# ENERGIS_Main-Board-1_1_0.net
KiCad netlist of a schematic drawn in EAGLE
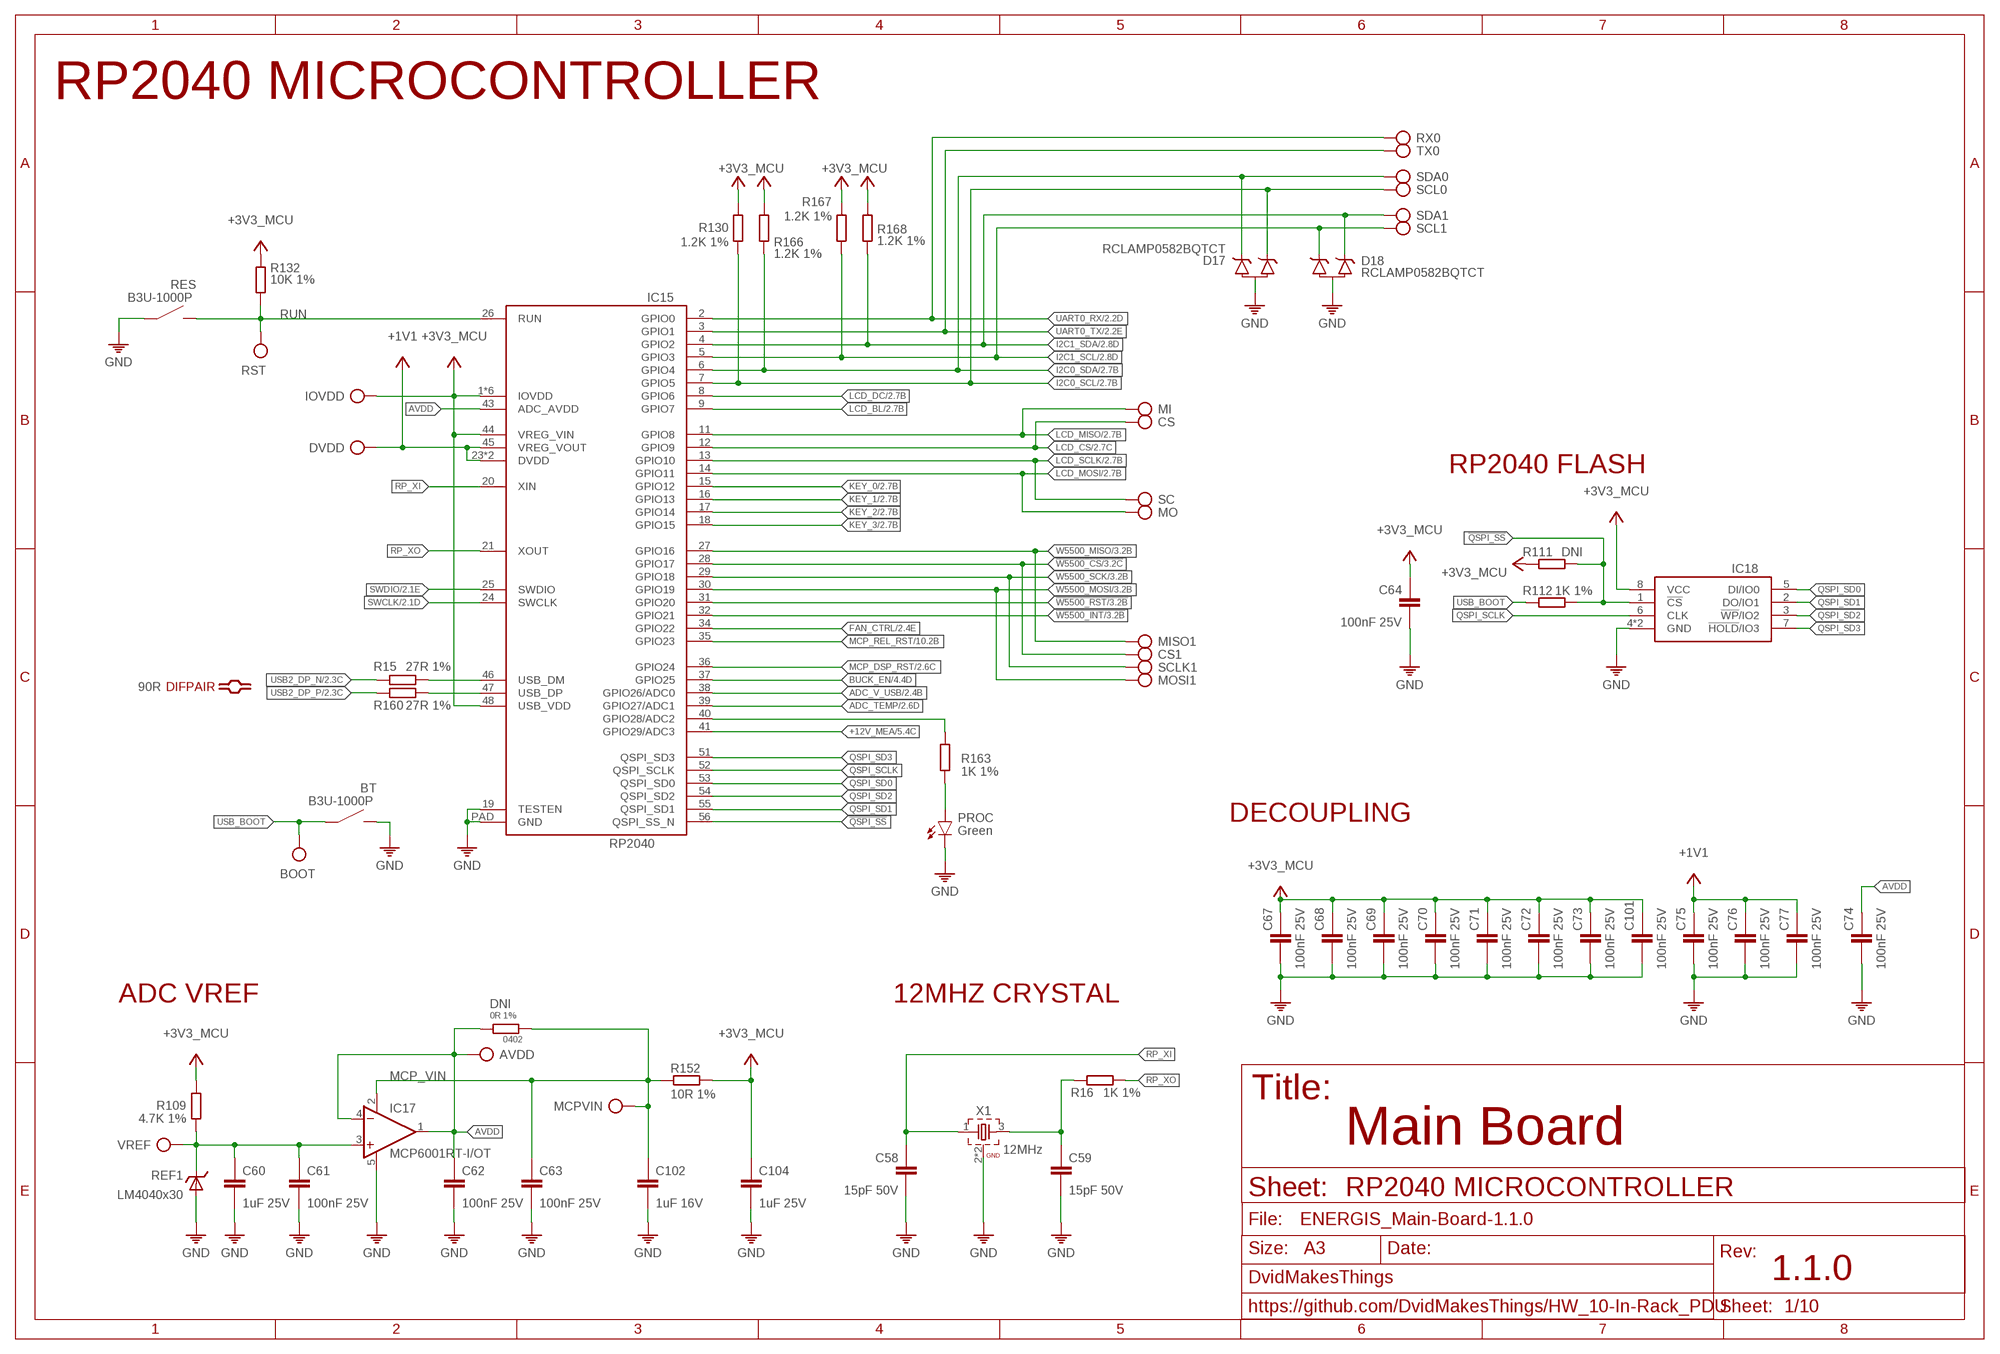
[diagram p0: schematic, sheet 1]
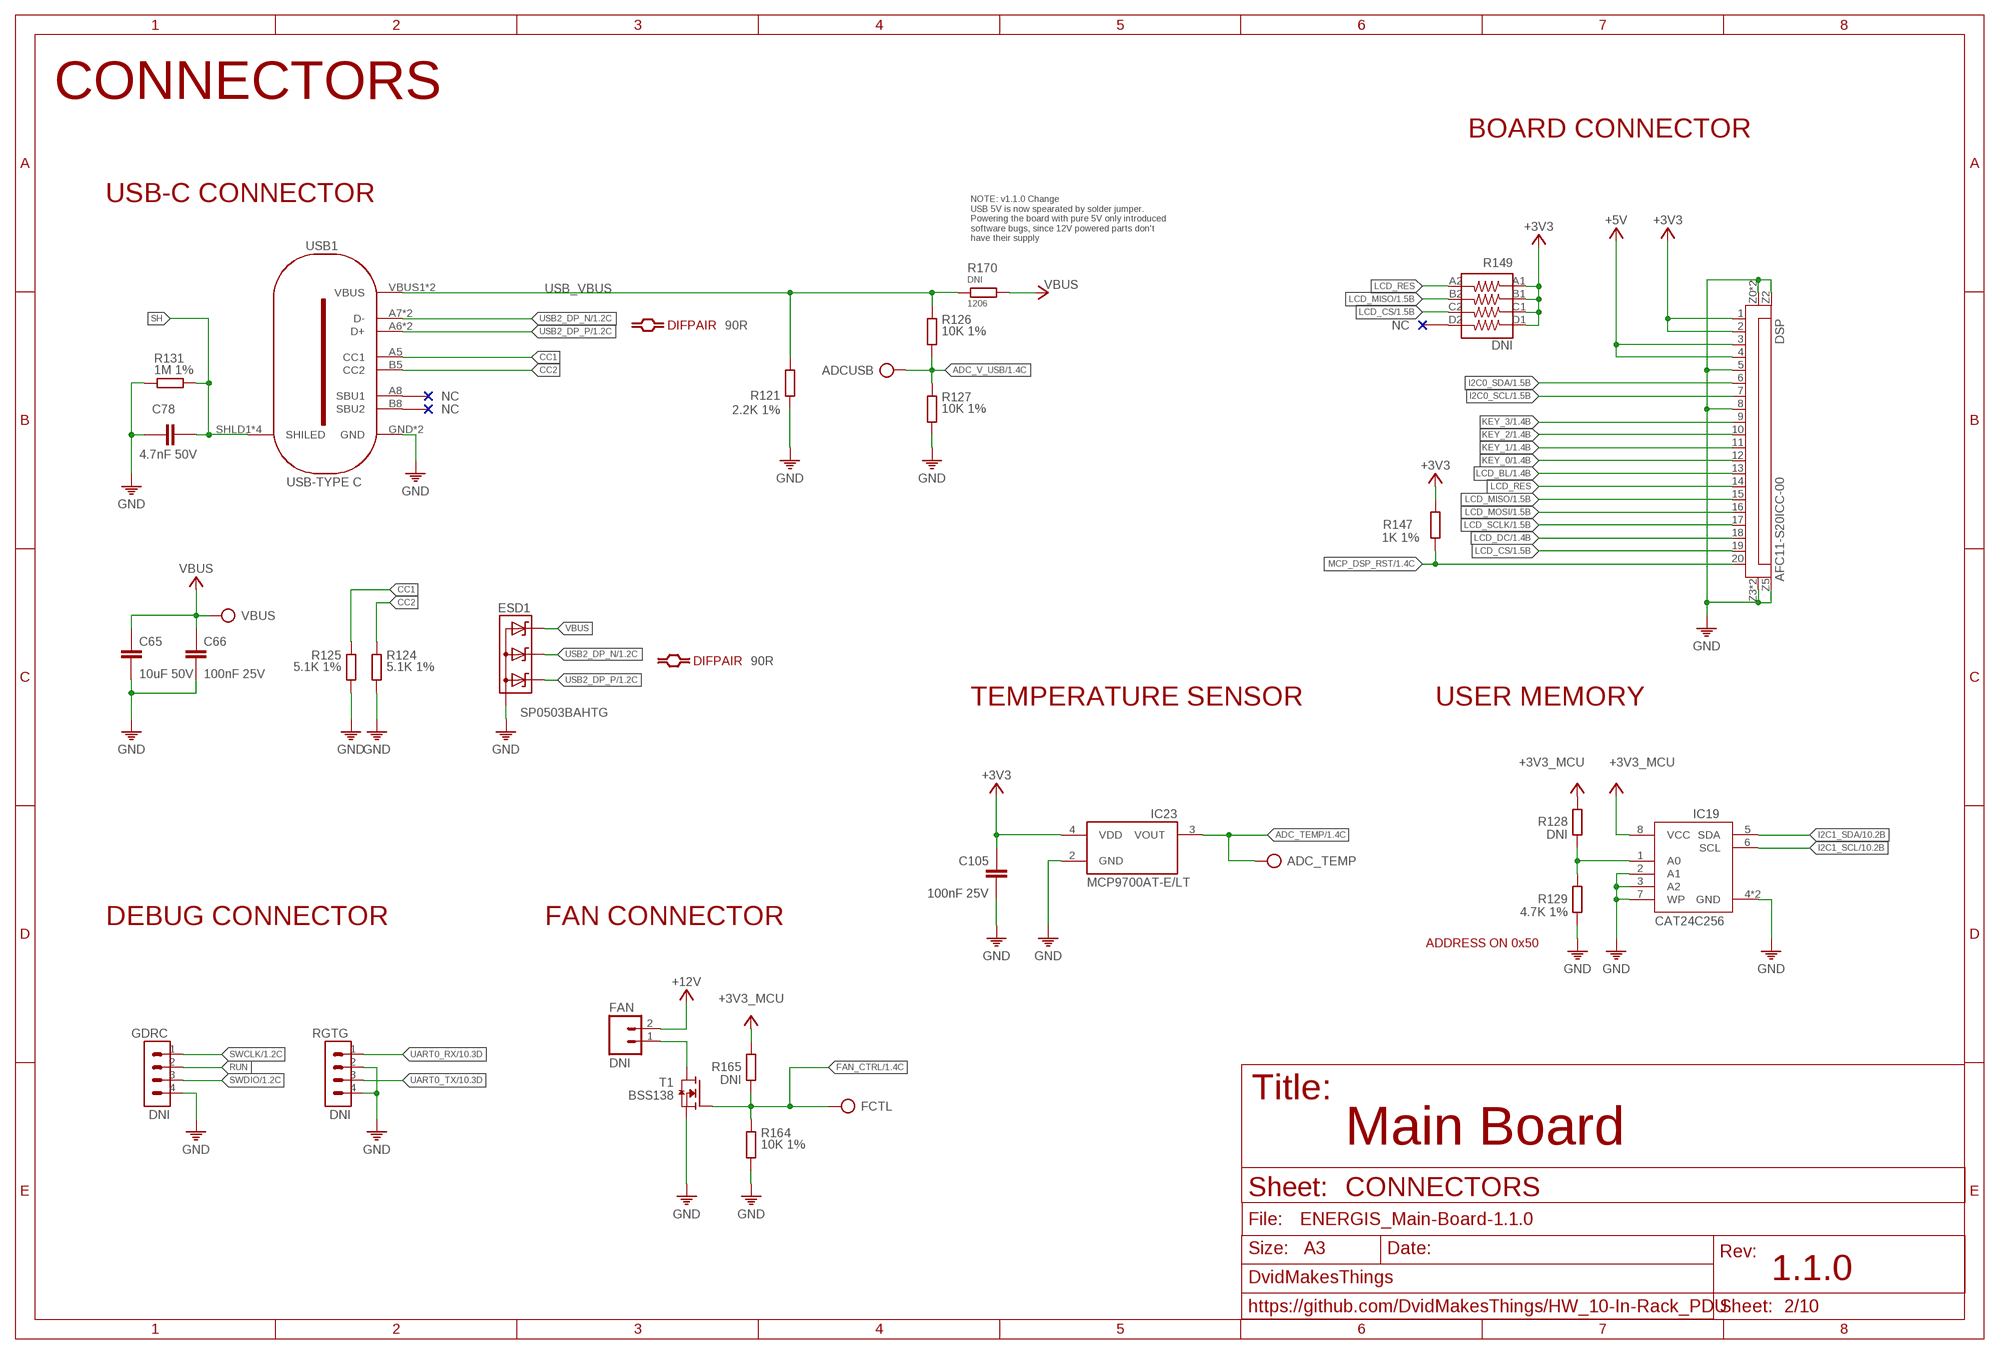
[diagram p1: schematic, sheet 2]
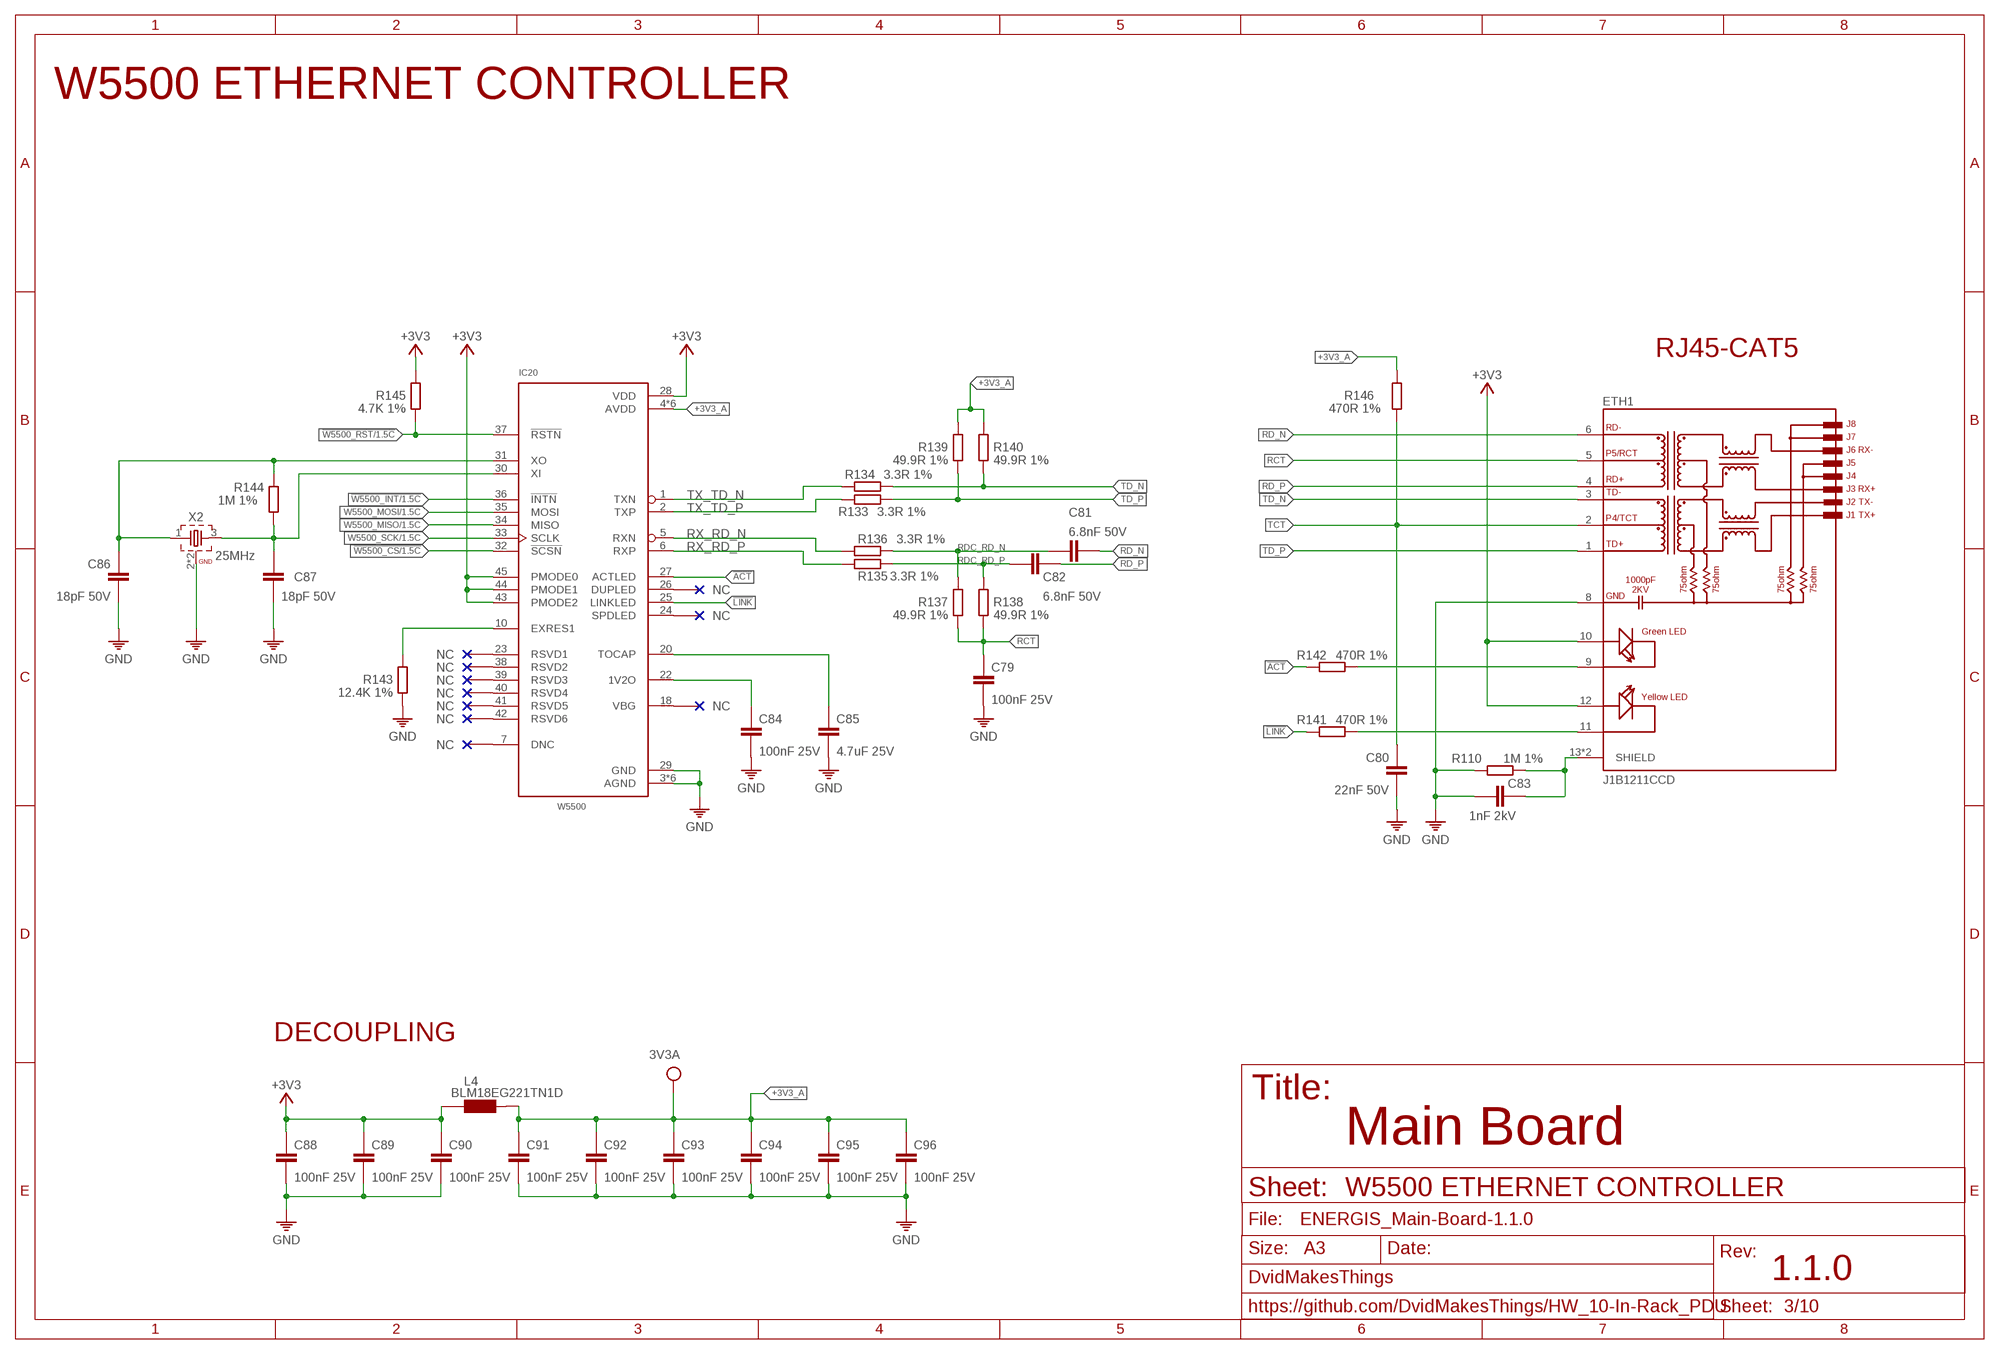
[diagram p2: schematic, sheet 3]
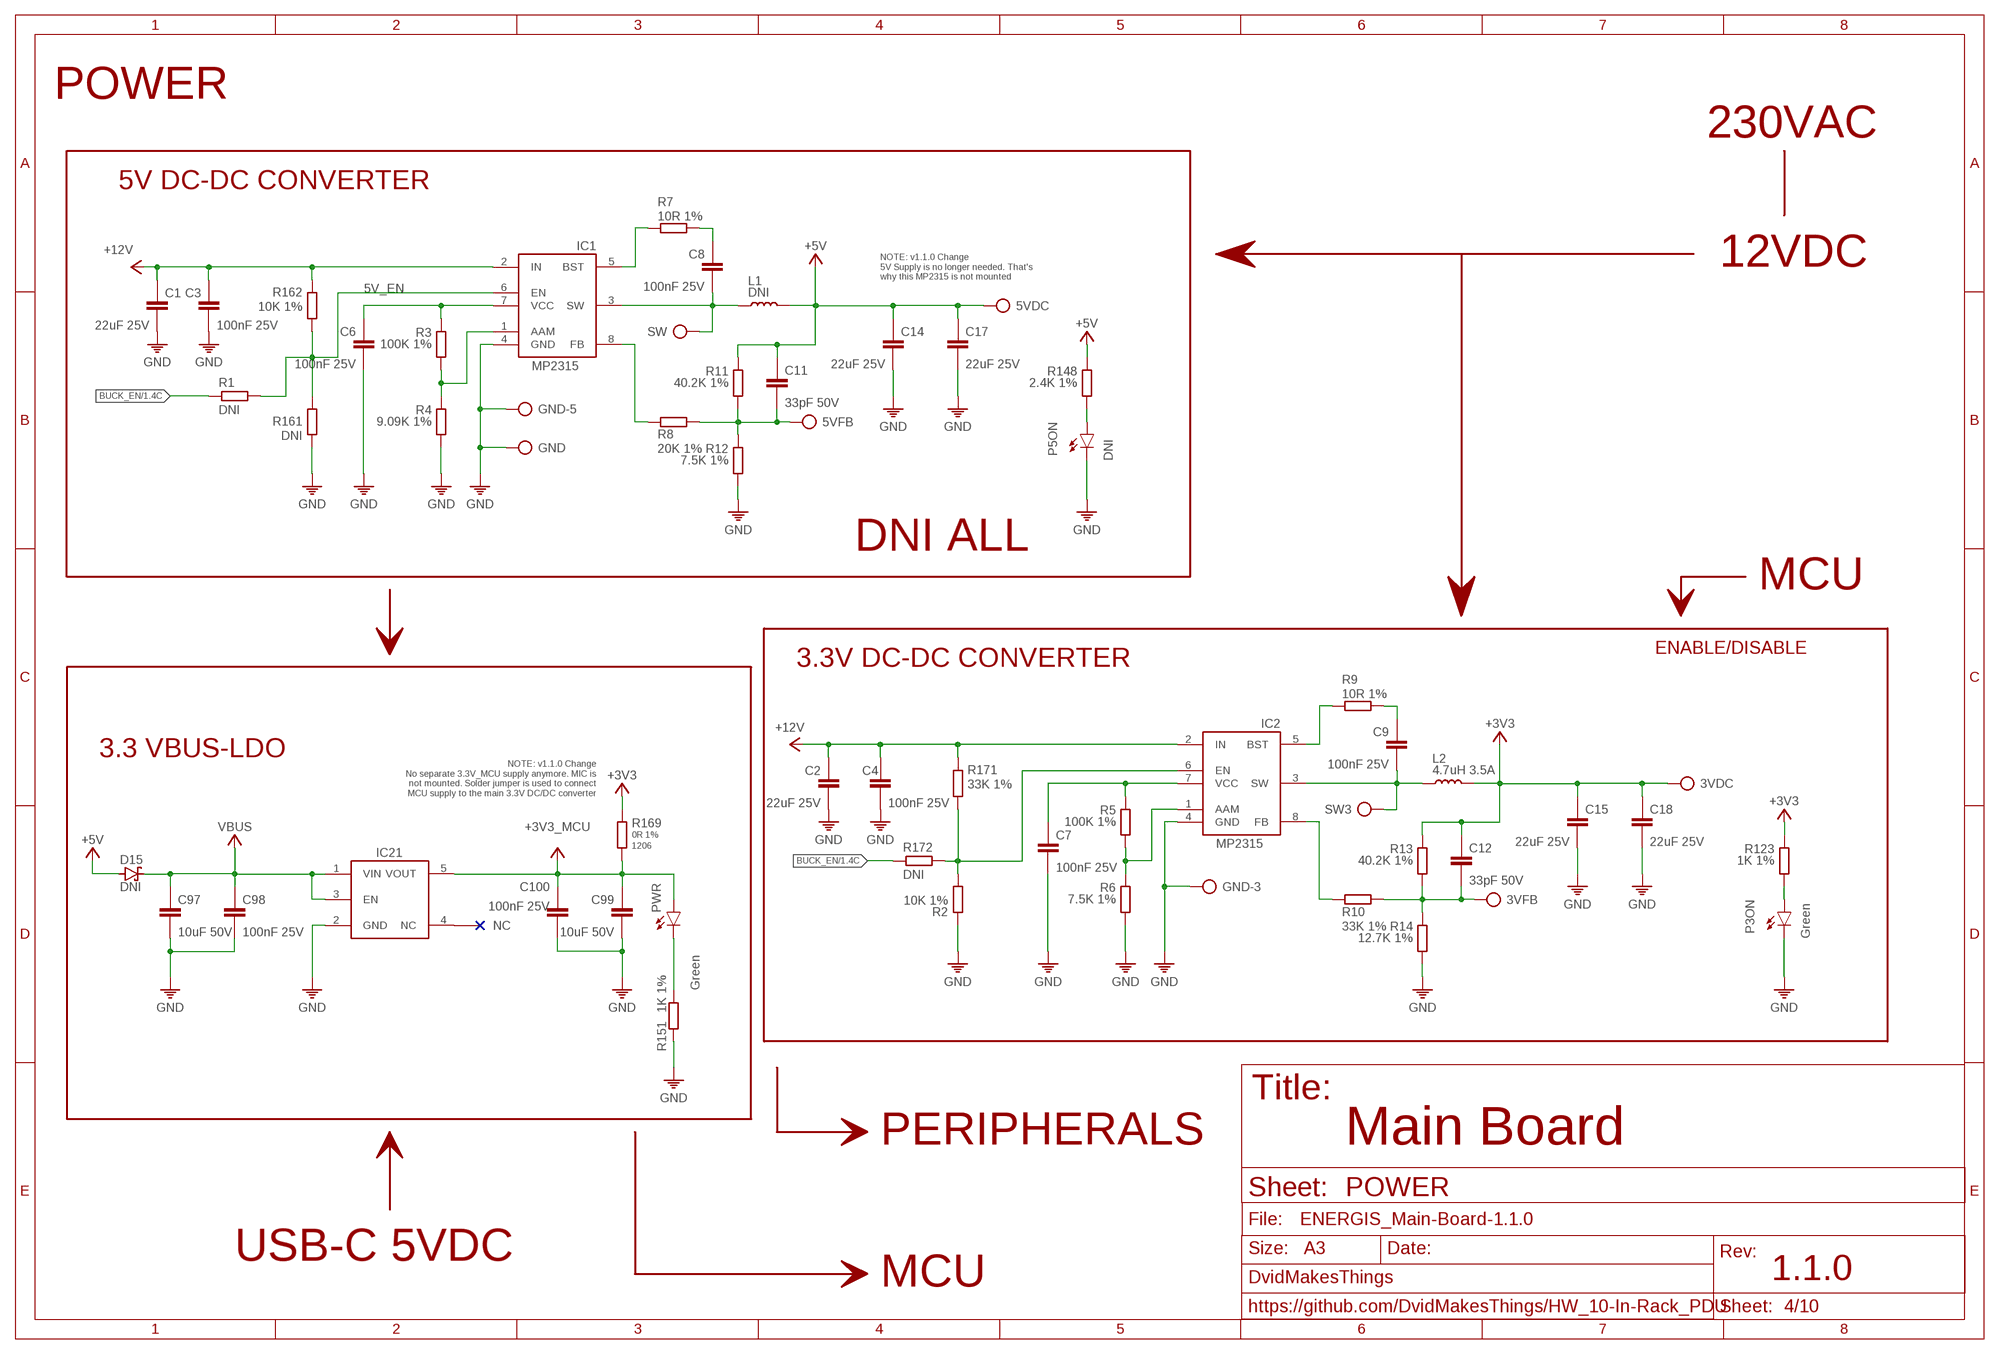
[diagram p3: schematic, sheet 4]
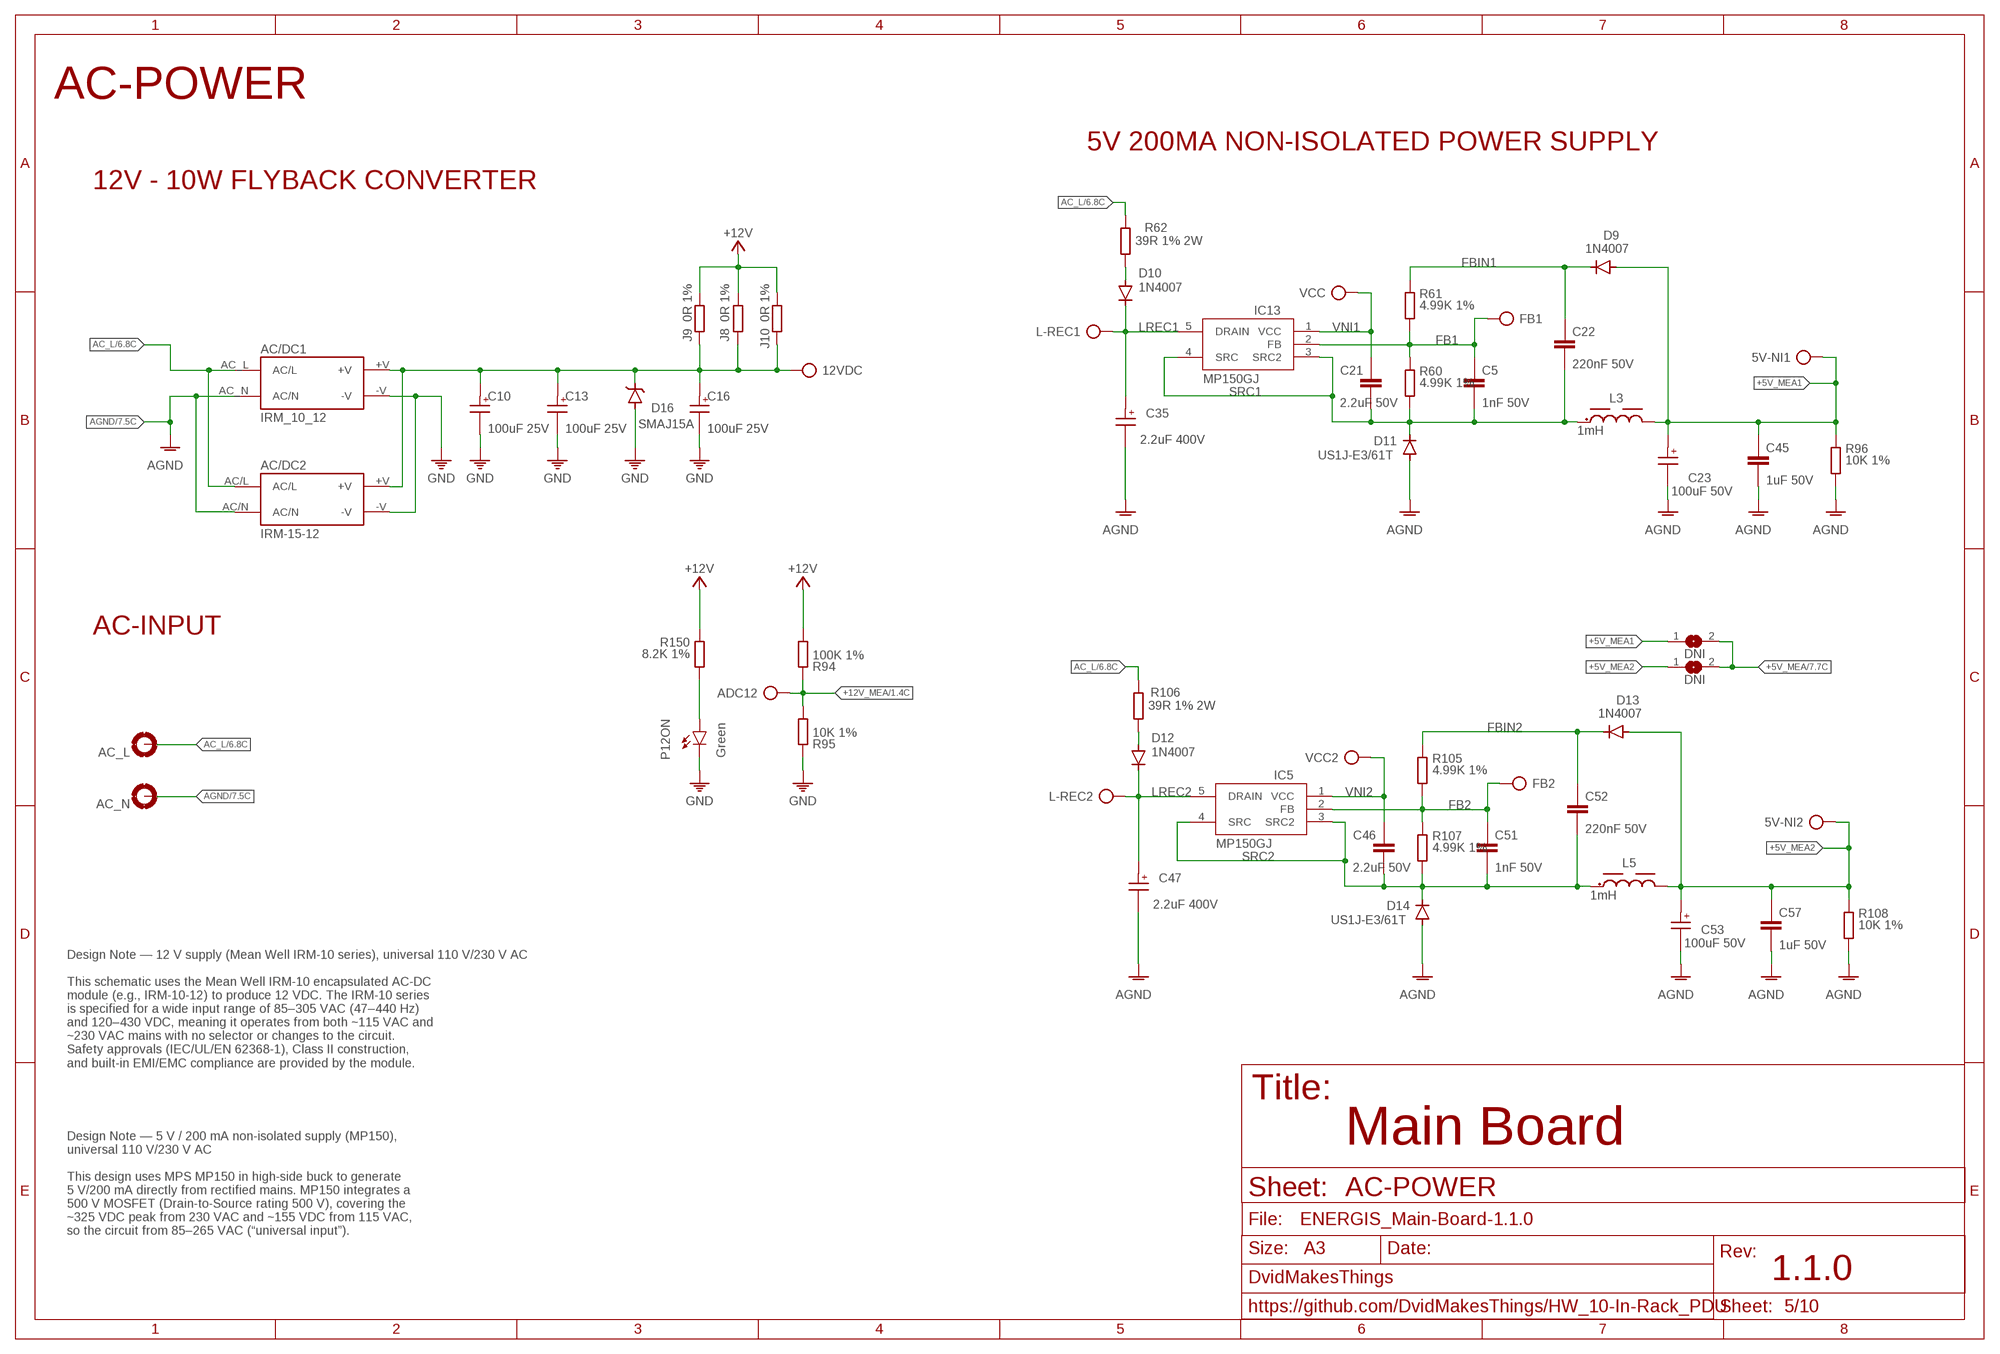
[diagram p4: schematic, sheet 5]
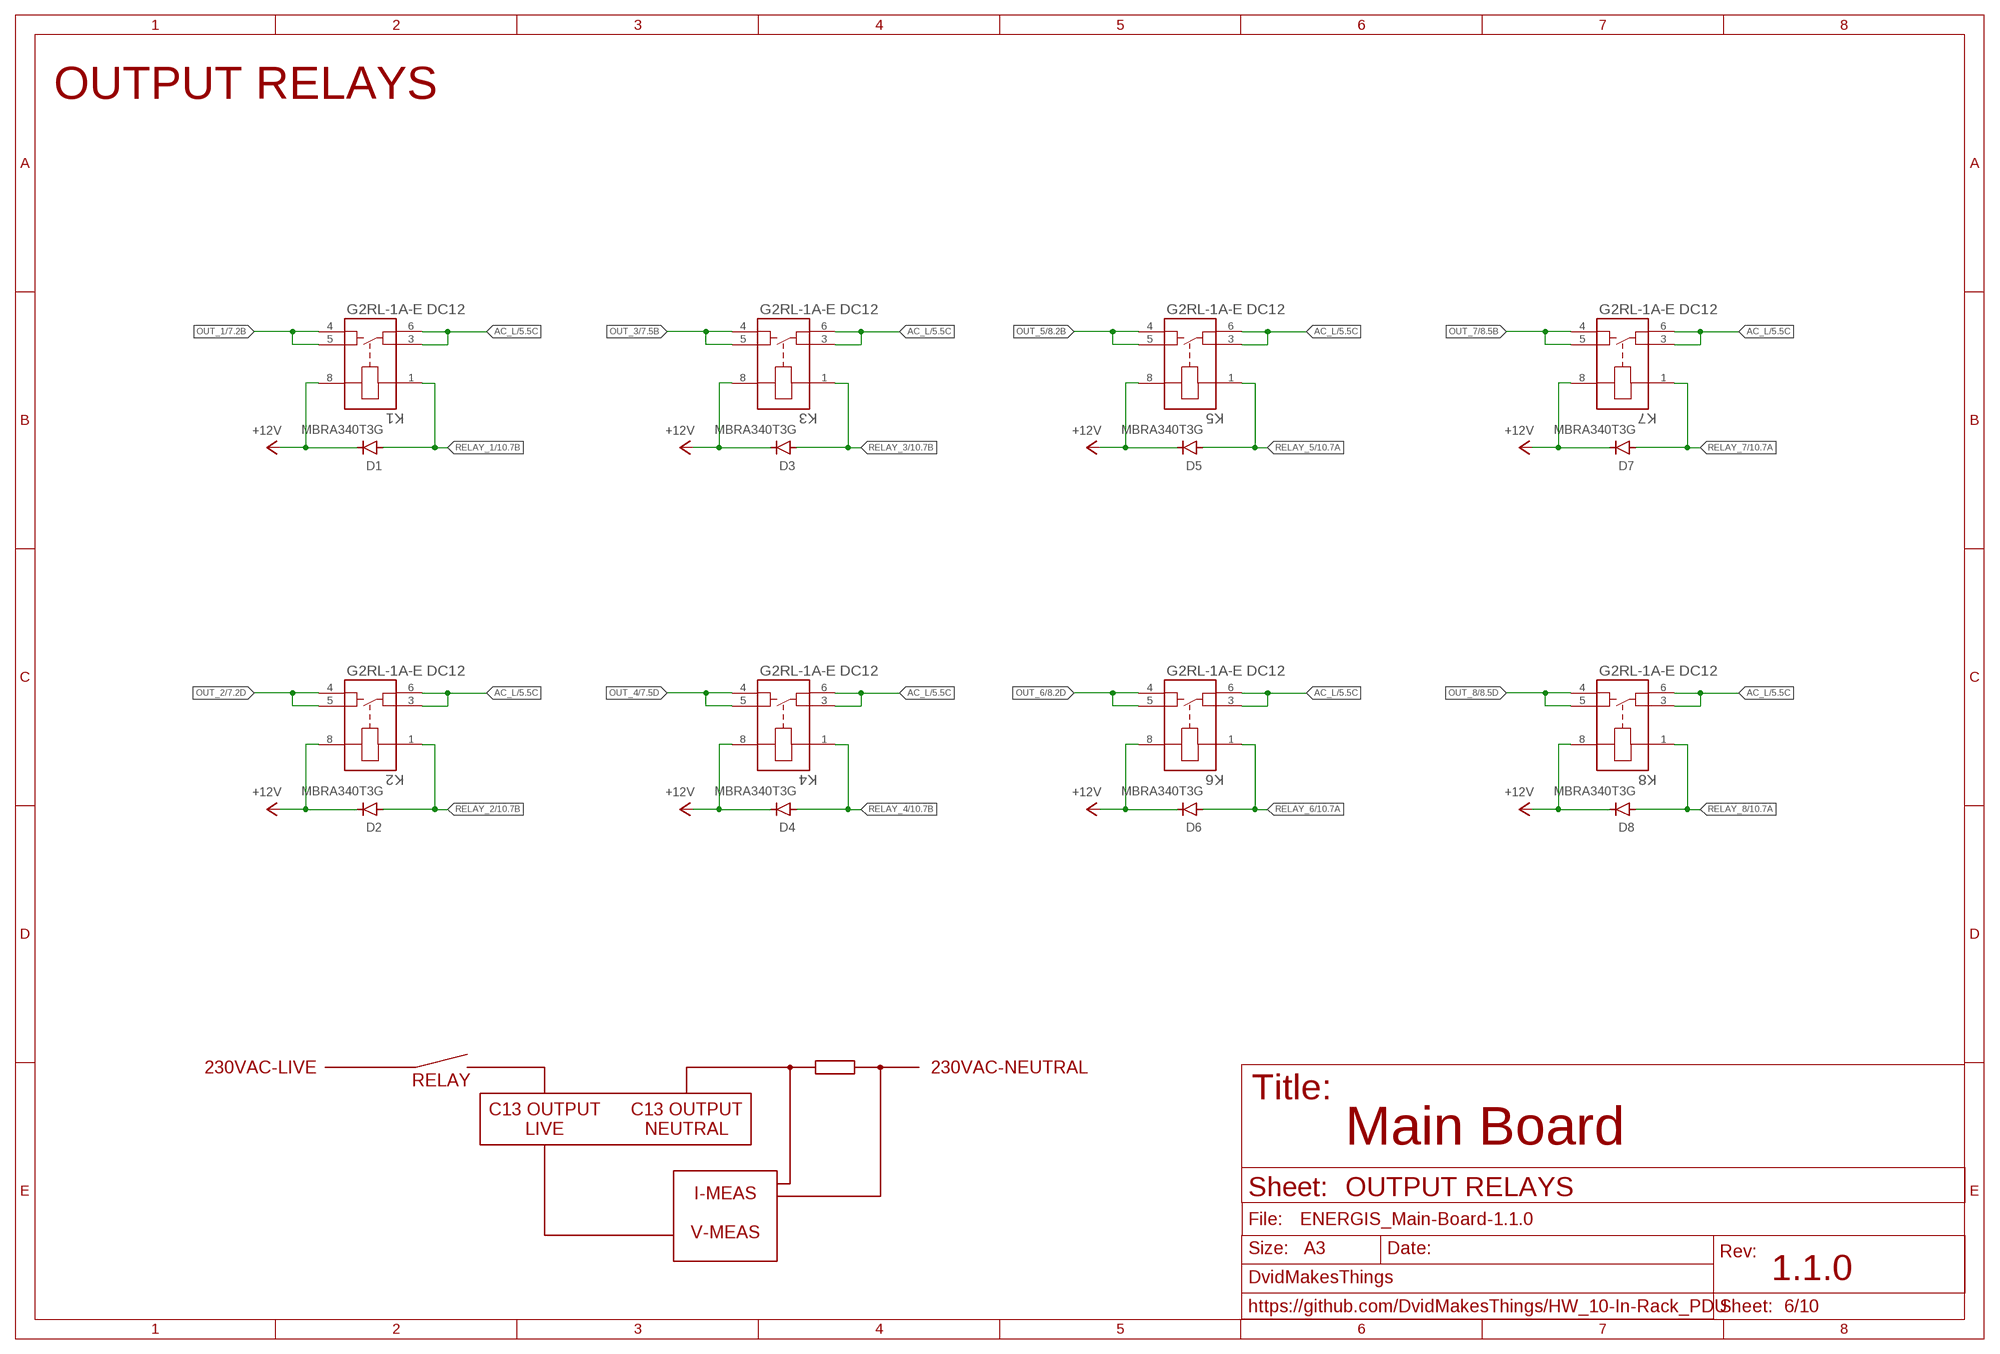
[diagram p5: schematic, sheet 6]
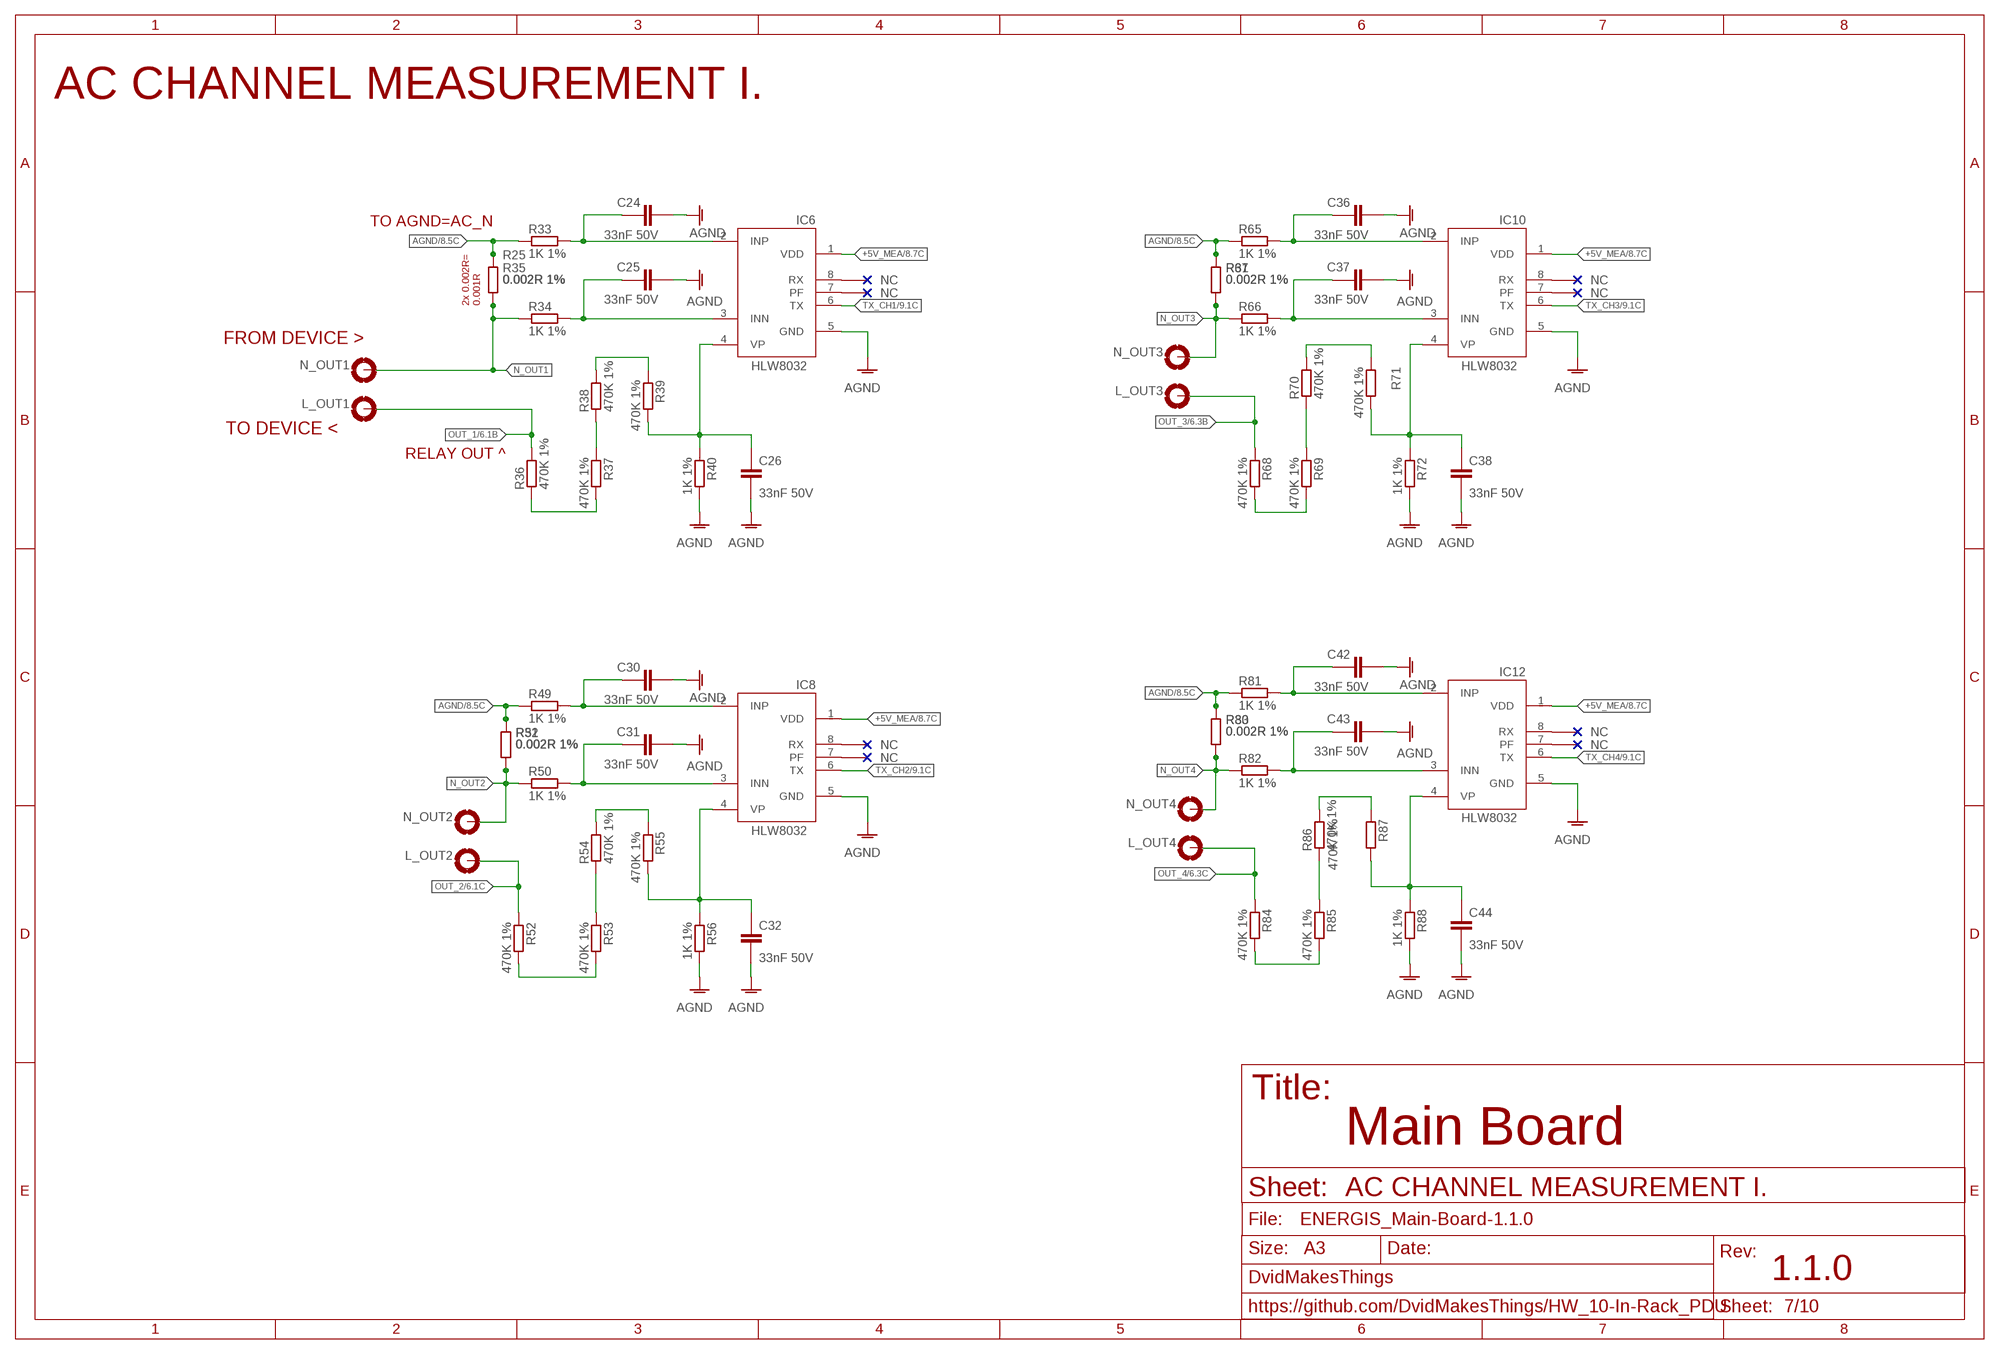
[diagram p6: schematic, sheet 7]
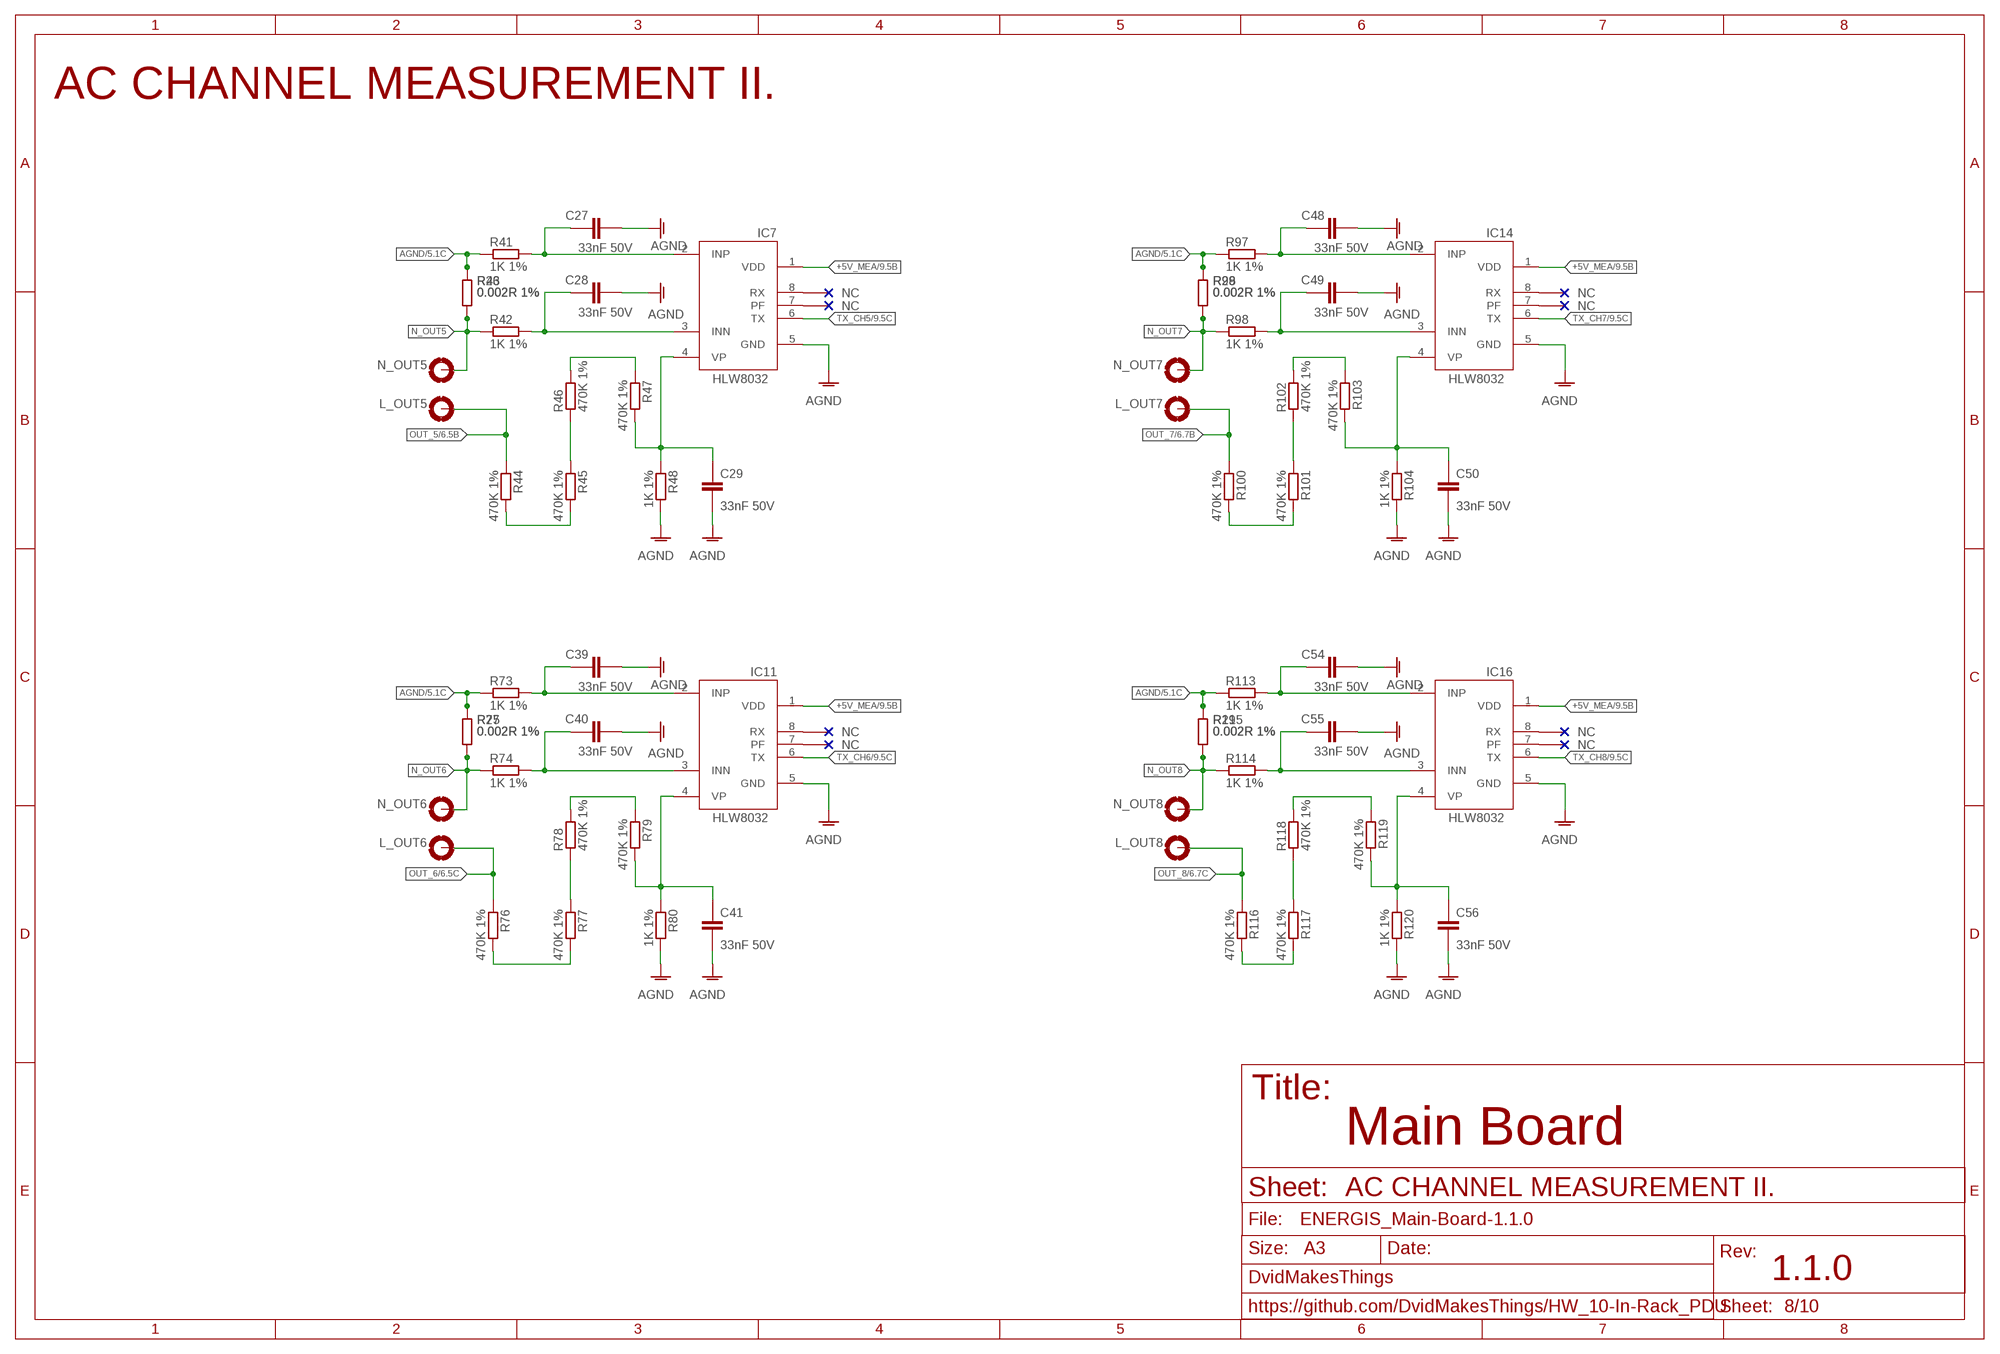
[diagram p7: schematic, sheet 8]
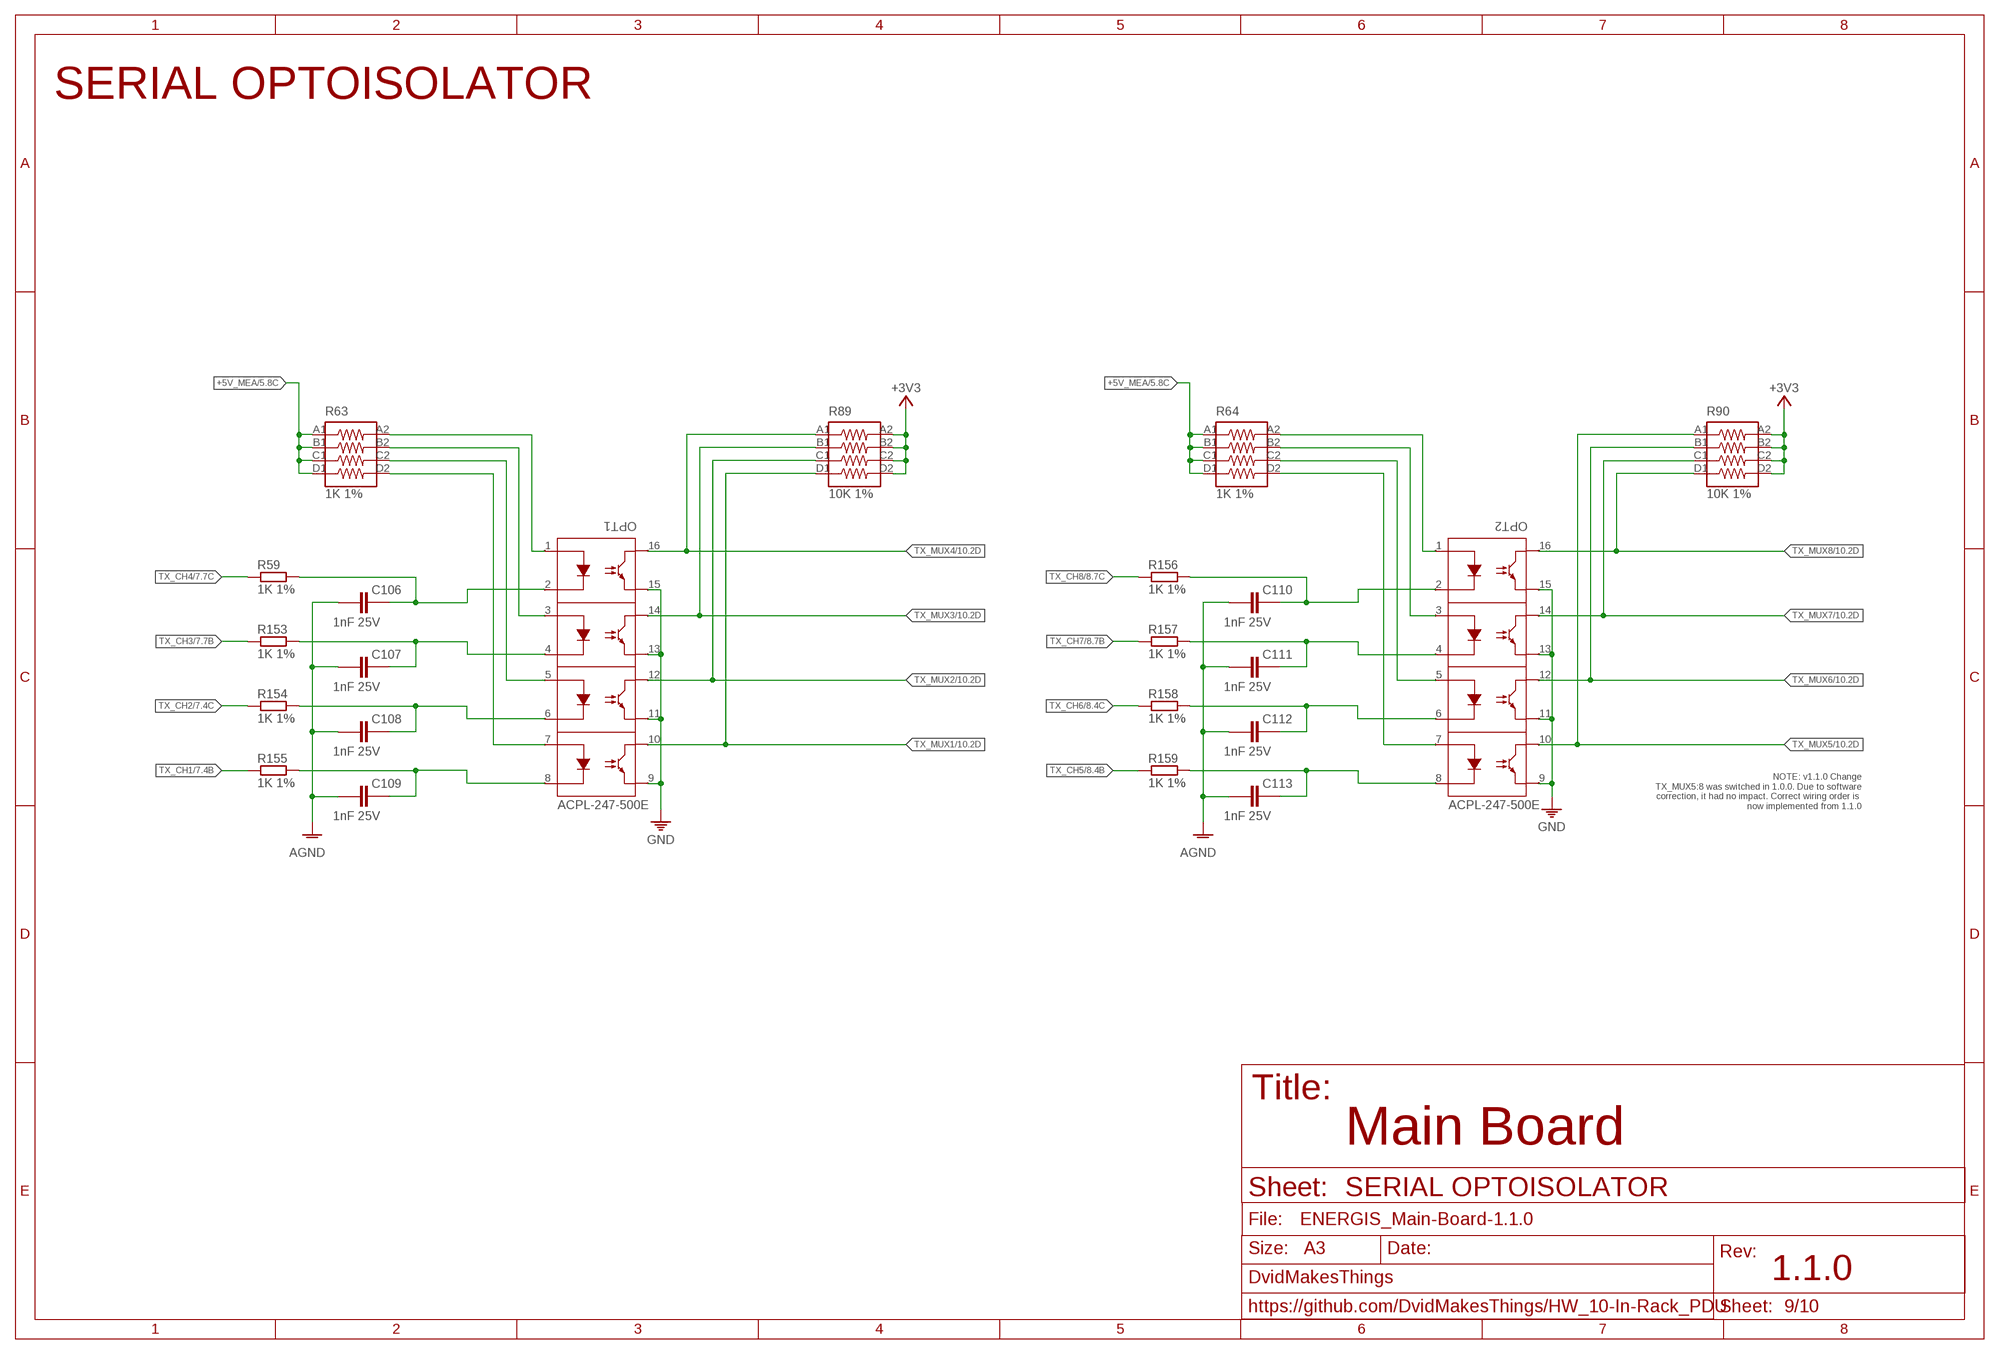
[diagram p8: schematic, sheet 9]
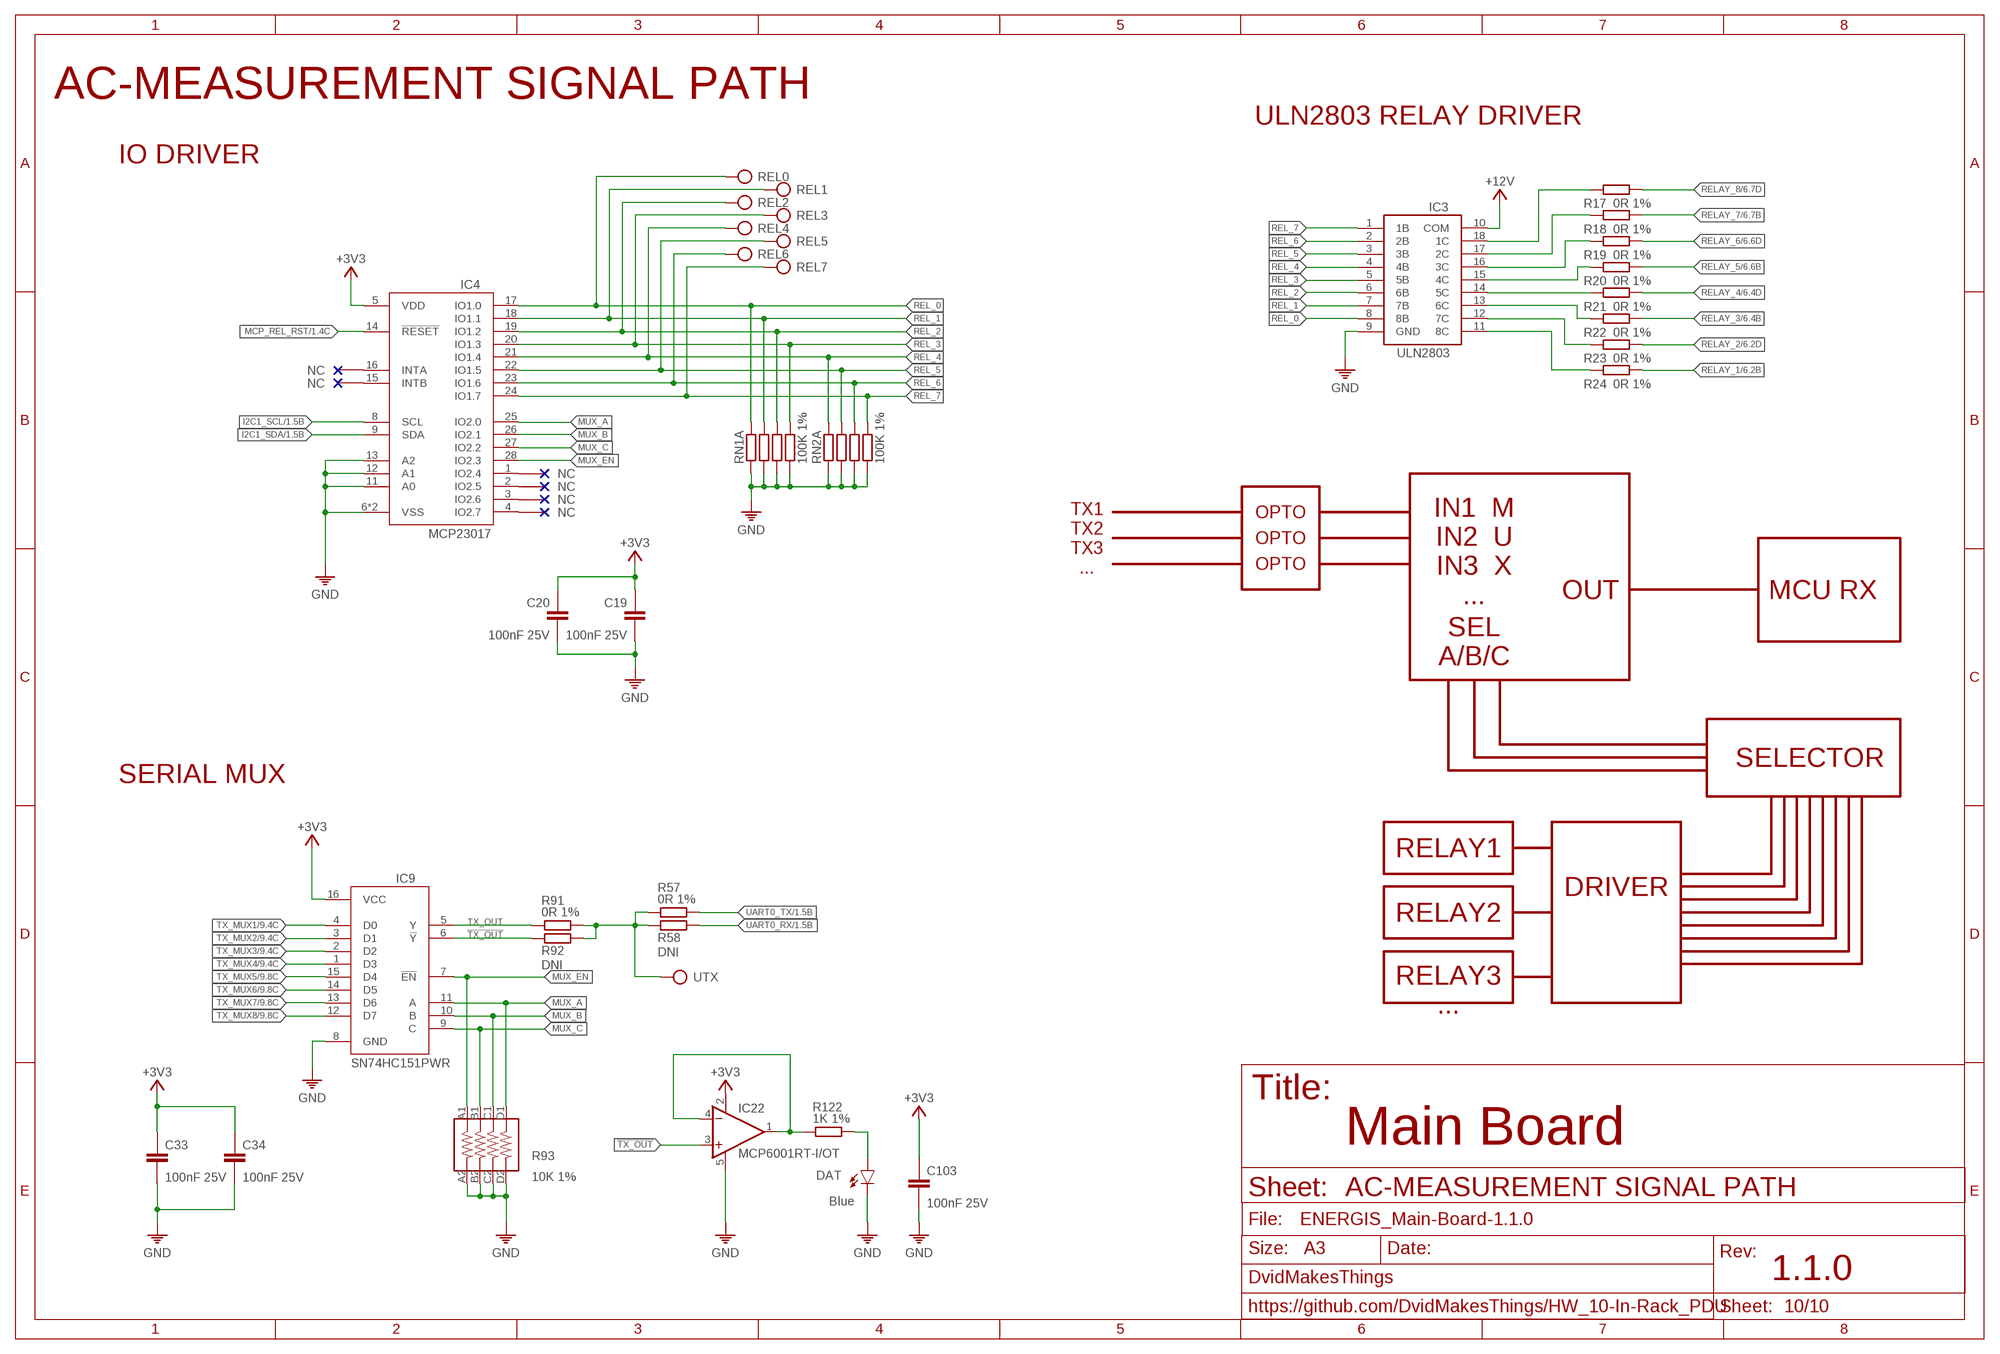
[diagram p9: schematic, sheet 10]

(export (version "E")
  (design (tool "Eeschema 10.0.6"))
  (components
    (comp (ref "C27")
      (value "33nF 50V")
      (footprint "eagle-import:0805")
      (fields
        (field (name "HQ_PART") "UN0000063")
        (field (name "LCSC_PART") "C107150")
        (field (name "MANUFACTURER") "FH")
      )
      (libsource (lib "eagle-import") (part "33NF-50V0805"))
    )
    (comp (ref "C28")
      (value "33nF 50V")
      (footprint "eagle-import:0805")
      (fields
        (field (name "HQ_PART") "UN0000063")
        (field (name "LCSC_PART") "C107150")
        (field (name "MANUFACTURER") "FH")
      )
      (libsource (lib "eagle-import") (part "33NF-50V0805"))
    )
    (comp (ref "C29")
      (value "33nF 50V")
      (footprint "eagle-import:0805")
      (fields
        (field (name "HQ_PART") "UN0000063")
        (field (name "LCSC_PART") "C107150")
        (field (name "MANUFACTURER") "FH")
      )
      (libsource (lib "eagle-import") (part "33NF-50V0805"))
    )
    (comp (ref "C39")
      (value "33nF 50V")
      (footprint "eagle-import:0805")
      (fields
        (field (name "HQ_PART") "UN0000063")
        (field (name "LCSC_PART") "C107150")
        (field (name "MANUFACTURER") "FH")
      )
      (libsource (lib "eagle-import") (part "33NF-50V0805"))
    )
    (comp (ref "C40")
      (value "33nF 50V")
      (footprint "eagle-import:0805")
      (fields
        (field (name "HQ_PART") "UN0000063")
        (field (name "LCSC_PART") "C107150")
        (field (name "MANUFACTURER") "FH")
      )
      (libsource (lib "eagle-import") (part "33NF-50V0805"))
    )
    (comp (ref "C41")
      (value "33nF 50V")
      (footprint "eagle-import:0805")
      (fields
        (field (name "HQ_PART") "UN0000063")
        (field (name "LCSC_PART") "C107150")
        (field (name "MANUFACTURER") "FH")
      )
      (libsource (lib "eagle-import") (part "33NF-50V0805"))
    )
    (comp (ref "C48")
      (value "33nF 50V")
      (footprint "eagle-import:0805")
      (fields
        (field (name "HQ_PART") "UN0000063")
        (field (name "LCSC_PART") "C107150")
        (field (name "MANUFACTURER") "FH")
      )
      (libsource (lib "eagle-import") (part "33NF-50V0805"))
    )
    (comp (ref "C49")
      (value "33nF 50V")
      (footprint "eagle-import:0805")
      (fields
        (field (name "HQ_PART") "UN0000063")
        (field (name "LCSC_PART") "C107150")
        (field (name "MANUFACTURER") "FH")
      )
      (libsource (lib "eagle-import") (part "33NF-50V0805"))
    )
    (comp (ref "C50")
      (value "33nF 50V")
      (footprint "eagle-import:0805")
      (fields
        (field (name "HQ_PART") "UN0000063")
        (field (name "LCSC_PART") "C107150")
        (field (name "MANUFACTURER") "FH")
      )
      (libsource (lib "eagle-import") (part "33NF-50V0805"))
    )
    (comp (ref "C54")
      (value "33nF 50V")
      (footprint "eagle-import:0805")
      (fields
        (field (name "HQ_PART") "UN0000063")
        (field (name "LCSC_PART") "C107150")
        (field (name "MANUFACTURER") "FH")
      )
      (libsource (lib "eagle-import") (part "33NF-50V0805"))
    )
    (comp (ref "C55")
      (value "33nF 50V")
      (footprint "eagle-import:0805")
      (fields
        (field (name "HQ_PART") "UN0000063")
        (field (name "LCSC_PART") "C107150")
        (field (name "MANUFACTURER") "FH")
      )
      (libsource (lib "eagle-import") (part "33NF-50V0805"))
    )
    (comp (ref "C56")
      (value "33nF 50V")
      (footprint "eagle-import:0805")
      (fields
        (field (name "HQ_PART") "UN0000063")
        (field (name "LCSC_PART") "C107150")
        (field (name "MANUFACTURER") "FH")
      )
      (libsource (lib "eagle-import") (part "33NF-50V0805"))
    )
    (comp (ref "IC7")
      (value "HLW8032")
      (footprint "eagle-import:SO8")
      (fields
        (field (name "HQ_PART") "MD0751024")
        (field (name "LCSC_PART") "C128023")
        (field (name "MANUFACTURER") "Hiliwei Tech")
      )
      (libsource (lib "eagle-import") (part "HLW8032"))
    )
    (comp (ref "IC11")
      (value "HLW8032")
      (footprint "eagle-import:SO8")
      (fields
        (field (name "HQ_PART") "MD0751024")
        (field (name "LCSC_PART") "C128023")
        (field (name "MANUFACTURER") "Hiliwei Tech")
      )
      (libsource (lib "eagle-import") (part "HLW8032"))
    )
    (comp (ref "IC14")
      (value "HLW8032")
      (footprint "eagle-import:SO8")
      (fields
        (field (name "HQ_PART") "MD0751024")
        (field (name "LCSC_PART") "C128023")
        (field (name "MANUFACTURER") "Hiliwei Tech")
      )
      (libsource (lib "eagle-import") (part "HLW8032"))
    )
    (comp (ref "IC16")
      (value "HLW8032")
      (footprint "eagle-import:SO8")
      (fields
        (field (name "HQ_PART") "MD0751024")
        (field (name "LCSC_PART") "C128023")
        (field (name "MANUFACTURER") "Hiliwei Tech")
      )
      (libsource (lib "eagle-import") (part "HLW8032"))
    )
    (comp (ref "L_OUT5")
      (value "FASTON-1217861-1")
      (footprint "eagle-import:1217861-1")
      (fields
        (field (name "LCSC_PART") "C428480")
        (field (name "MANUFACTURER") "TE CONNECTIVITY")
        (field (name "MPN") "1217861-1")
      )
      (libsource (lib "eagle-import") (part "FASTON-1217861-1"))
    )
    (comp (ref "L_OUT6")
      (value "FASTON-1217861-1")
      (footprint "eagle-import:1217861-1")
      (fields
        (field (name "LCSC_PART") "C428480")
        (field (name "MANUFACTURER") "TE CONNECTIVITY")
        (field (name "MPN") "1217861-1")
      )
      (libsource (lib "eagle-import") (part "FASTON-1217861-1"))
    )
    (comp (ref "L_OUT7")
      (value "FASTON-1217861-1")
      (footprint "eagle-import:1217861-1")
      (fields
        (field (name "LCSC_PART") "C428480")
        (field (name "MANUFACTURER") "TE CONNECTIVITY")
        (field (name "MPN") "1217861-1")
      )
      (libsource (lib "eagle-import") (part "FASTON-1217861-1"))
    )
    (comp (ref "L_OUT8")
      (value "FASTON-1217861-1")
      (footprint "eagle-import:1217861-1")
      (fields
        (field (name "LCSC_PART") "C428480")
        (field (name "MANUFACTURER") "TE CONNECTIVITY")
        (field (name "MPN") "1217861-1")
      )
      (libsource (lib "eagle-import") (part "FASTON-1217861-1"))
    )
    (comp (ref "N_OUT5")
      (value "FASTON-1217861-1")
      (footprint "eagle-import:1217861-1")
      (fields
        (field (name "LCSC_PART") "C428480")
        (field (name "MANUFACTURER") "TE CONNECTIVITY")
        (field (name "MPN") "1217861-1")
      )
      (libsource (lib "eagle-import") (part "FASTON-1217861-1"))
    )
    (comp (ref "N_OUT6")
      (value "FASTON-1217861-1")
      (footprint "eagle-import:1217861-1")
      (fields
        (field (name "LCSC_PART") "C428480")
        (field (name "MANUFACTURER") "TE CONNECTIVITY")
        (field (name "MPN") "1217861-1")
      )
      (libsource (lib "eagle-import") (part "FASTON-1217861-1"))
    )
    (comp (ref "N_OUT7")
      (value "FASTON-1217861-1")
      (footprint "eagle-import:1217861-1")
      (fields
        (field (name "LCSC_PART") "C428480")
        (field (name "MANUFACTURER") "TE CONNECTIVITY")
        (field (name "MPN") "1217861-1")
      )
      (libsource (lib "eagle-import") (part "FASTON-1217861-1"))
    )
    (comp (ref "N_OUT8")
      (value "FASTON-1217861-1")
      (footprint "eagle-import:1217861-1")
      (fields
        (field (name "LCSC_PART") "C428480")
        (field (name "MANUFACTURER") "TE CONNECTIVITY")
        (field (name "MPN") "1217861-1")
      )
      (libsource (lib "eagle-import") (part "FASTON-1217861-1"))
    )
    (comp (ref "R26")
      (value "0.002R 1%")
      (footprint "eagle-import:2512")
      (fields
        (field (name "HQ_PART") "RE0716514")
        (field (name "LCSC_PART") "C728320")
        (field (name "MANUFACTURER") "Viking")
      )
      (libsource (lib "eagle-import") (part "0.002R-1%2512"))
    )
    (comp (ref "R27")
      (value "0.002R 1%")
      (footprint "eagle-import:2512")
      (fields
        (field (name "HQ_PART") "RE0716514")
        (field (name "LCSC_PART") "C728320")
        (field (name "MANUFACTURER") "Viking")
      )
      (libsource (lib "eagle-import") (part "0.002R-1%2512"))
    )
    (comp (ref "R28")
      (value "0.002R 1%")
      (footprint "eagle-import:2512")
      (fields
        (field (name "HQ_PART") "RE0716514")
        (field (name "LCSC_PART") "C728320")
        (field (name "MANUFACTURER") "Viking")
      )
      (libsource (lib "eagle-import") (part "0.002R-1%2512"))
    )
    (comp (ref "R29")
      (value "0.002R 1%")
      (footprint "eagle-import:2512")
      (fields
        (field (name "HQ_PART") "RE0716514")
        (field (name "LCSC_PART") "C728320")
        (field (name "MANUFACTURER") "Viking")
      )
      (libsource (lib "eagle-import") (part "0.002R-1%2512"))
    )
    (comp (ref "R41")
      (value "1K 1%")
      (footprint "eagle-import:0805")
      (fields
        (field (name "HQ_PART") "RE0203459")
        (field (name "LCSC_PART") "C17513")
        (field (name "MANUFACTURER") "FH")
      )
      (libsource (lib "eagle-import") (part "1K-1%0805"))
    )
    (comp (ref "R42")
      (value "1K 1%")
      (footprint "eagle-import:0805")
      (fields
        (field (name "HQ_PART") "RE0203459")
        (field (name "LCSC_PART") "C17513")
        (field (name "MANUFACTURER") "FH")
      )
      (libsource (lib "eagle-import") (part "1K-1%0805"))
    )
    (comp (ref "R43")
      (value "0.002R 1%")
      (footprint "eagle-import:2512")
      (fields
        (field (name "HQ_PART") "RE0716514")
        (field (name "LCSC_PART") "C728320")
        (field (name "MANUFACTURER") "Viking")
      )
      (libsource (lib "eagle-import") (part "0.002R-1%2512"))
    )
    (comp (ref "R44")
      (value "470K 1%")
      (footprint "eagle-import:0805")
      (fields
        (field (name "HQ_PART") "RE0205756")
        (field (name "LCSC_PART") "C17709")
        (field (name "MANUFACTURER") "Panasonic")
      )
      (libsource (lib "eagle-import") (part "470K-1%0805"))
    )
    (comp (ref "R45")
      (value "470K 1%")
      (footprint "eagle-import:0805")
      (fields
        (field (name "HQ_PART") "RE0205756")
        (field (name "LCSC_PART") "C17709")
        (field (name "MANUFACTURER") "Panasonic")
      )
      (libsource (lib "eagle-import") (part "470K-1%0805"))
    )
    (comp (ref "R46")
      (value "470K 1%")
      (footprint "eagle-import:0805")
      (fields
        (field (name "HQ_PART") "RE0205756")
        (field (name "LCSC_PART") "C17709")
        (field (name "MANUFACTURER") "Panasonic")
      )
      (libsource (lib "eagle-import") (part "470K-1%0805"))
    )
    (comp (ref "R47")
      (value "470K 1%")
      (footprint "eagle-import:0805")
      (fields
        (field (name "HQ_PART") "RE0205756")
        (field (name "LCSC_PART") "C17709")
        (field (name "MANUFACTURER") "Panasonic")
      )
      (libsource (lib "eagle-import") (part "470K-1%0805"))
    )
    (comp (ref "R48")
      (value "1K 1%")
      (footprint "eagle-import:0805")
      (fields
        (field (name "HQ_PART") "RE0203459")
        (field (name "LCSC_PART") "C17513")
        (field (name "MANUFACTURER") "FH")
      )
      (libsource (lib "eagle-import") (part "1K-1%0805"))
    )
    (comp (ref "R73")
      (value "1K 1%")
      (footprint "eagle-import:0805")
      (fields
        (field (name "HQ_PART") "RE0203459")
        (field (name "LCSC_PART") "C17513")
        (field (name "MANUFACTURER") "FH")
      )
      (libsource (lib "eagle-import") (part "1K-1%0805"))
    )
    (comp (ref "R74")
      (value "1K 1%")
      (footprint "eagle-import:0805")
      (fields
        (field (name "HQ_PART") "RE0203459")
        (field (name "LCSC_PART") "C17513")
        (field (name "MANUFACTURER") "FH")
      )
      (libsource (lib "eagle-import") (part "1K-1%0805"))
    )
    (comp (ref "R75")
      (value "0.002R 1%")
      (footprint "eagle-import:2512")
      (fields
        (field (name "HQ_PART") "RE0716514")
        (field (name "LCSC_PART") "C728320")
        (field (name "MANUFACTURER") "Viking")
      )
      (libsource (lib "eagle-import") (part "0.002R-1%2512"))
    )
    (comp (ref "R76")
      (value "470K 1%")
      (footprint "eagle-import:0805")
      (fields
        (field (name "HQ_PART") "RE0205756")
        (field (name "LCSC_PART") "C17709")
        (field (name "MANUFACTURER") "Panasonic")
      )
      (libsource (lib "eagle-import") (part "470K-1%0805"))
    )
    (comp (ref "R77")
      (value "470K 1%")
      (footprint "eagle-import:0805")
      (fields
        (field (name "HQ_PART") "RE0205756")
        (field (name "LCSC_PART") "C17709")
        (field (name "MANUFACTURER") "Panasonic")
      )
      (libsource (lib "eagle-import") (part "470K-1%0805"))
    )
    (comp (ref "R78")
      (value "470K 1%")
      (footprint "eagle-import:0805")
      (fields
        (field (name "HQ_PART") "RE0205756")
        (field (name "LCSC_PART") "C17709")
        (field (name "MANUFACTURER") "Panasonic")
      )
      (libsource (lib "eagle-import") (part "470K-1%0805"))
    )
    (comp (ref "R79")
      (value "470K 1%")
      (footprint "eagle-import:0805")
      (fields
        (field (name "HQ_PART") "RE0205756")
        (field (name "LCSC_PART") "C17709")
        (field (name "MANUFACTURER") "Panasonic")
      )
      (libsource (lib "eagle-import") (part "470K-1%0805"))
    )
    (comp (ref "R80")
      (value "1K 1%")
      (footprint "eagle-import:0805")
      (fields
        (field (name "HQ_PART") "RE0203459")
        (field (name "LCSC_PART") "C17513")
        (field (name "MANUFACTURER") "FH")
      )
      (libsource (lib "eagle-import") (part "1K-1%0805"))
    )
    (comp (ref "R97")
      (value "1K 1%")
      (footprint "eagle-import:0805")
      (fields
        (field (name "HQ_PART") "RE0203459")
        (field (name "LCSC_PART") "C17513")
        (field (name "MANUFACTURER") "FH")
      )
      (libsource (lib "eagle-import") (part "1K-1%0805"))
    )
    (comp (ref "R98")
      (value "1K 1%")
      (footprint "eagle-import:0805")
      (fields
        (field (name "HQ_PART") "RE0203459")
        (field (name "LCSC_PART") "C17513")
        (field (name "MANUFACTURER") "FH")
      )
      (libsource (lib "eagle-import") (part "1K-1%0805"))
    )
    (comp (ref "R99")
      (value "0.002R 1%")
      (footprint "eagle-import:2512")
      (fields
        (field (name "HQ_PART") "RE0716514")
        (field (name "LCSC_PART") "C728320")
        (field (name "MANUFACTURER") "Viking")
      )
      (libsource (lib "eagle-import") (part "0.002R-1%2512"))
    )
    (comp (ref "R100")
      (value "470K 1%")
      (footprint "eagle-import:0805")
      (fields
        (field (name "HQ_PART") "RE0205756")
        (field (name "LCSC_PART") "C17709")
        (field (name "MANUFACTURER") "Panasonic")
      )
      (libsource (lib "eagle-import") (part "470K-1%0805"))
    )
    (comp (ref "R101")
      (value "470K 1%")
      (footprint "eagle-import:0805")
      (fields
        (field (name "HQ_PART") "RE0205756")
        (field (name "LCSC_PART") "C17709")
        (field (name "MANUFACTURER") "Panasonic")
      )
      (libsource (lib "eagle-import") (part "470K-1%0805"))
    )
    (comp (ref "R102")
      (value "470K 1%")
      (footprint "eagle-import:0805")
      (fields
        (field (name "HQ_PART") "RE0205756")
        (field (name "LCSC_PART") "C17709")
        (field (name "MANUFACTURER") "Panasonic")
      )
      (libsource (lib "eagle-import") (part "470K-1%0805"))
    )
    (comp (ref "R103")
      (value "470K 1%")
      (footprint "eagle-import:0805")
      (fields
        (field (name "HQ_PART") "RE0205756")
        (field (name "LCSC_PART") "C17709")
        (field (name "MANUFACTURER") "Panasonic")
      )
      (libsource (lib "eagle-import") (part "470K-1%0805"))
    )
    (comp (ref "R104")
      (value "1K 1%")
      (footprint "eagle-import:0805")
      (fields
        (field (name "HQ_PART") "RE0203459")
        (field (name "LCSC_PART") "C17513")
        (field (name "MANUFACTURER") "FH")
      )
      (libsource (lib "eagle-import") (part "1K-1%0805"))
    )
    (comp (ref "R113")
      (value "1K 1%")
      (footprint "eagle-import:0805")
      (fields
        (field (name "HQ_PART") "RE0203459")
        (field (name "LCSC_PART") "C17513")
        (field (name "MANUFACTURER") "FH")
      )
      (libsource (lib "eagle-import") (part "1K-1%0805"))
    )
    (comp (ref "R114")
      (value "1K 1%")
      (footprint "eagle-import:0805")
      (fields
        (field (name "HQ_PART") "RE0203459")
        (field (name "LCSC_PART") "C17513")
        (field (name "MANUFACTURER") "FH")
      )
      (libsource (lib "eagle-import") (part "1K-1%0805"))
    )
    (comp (ref "R115")
      (value "0.002R 1%")
      (footprint "eagle-import:2512")
      (fields
        (field (name "HQ_PART") "RE0716514")
        (field (name "LCSC_PART") "C728320")
        (field (name "MANUFACTURER") "Viking")
      )
      (libsource (lib "eagle-import") (part "0.002R-1%2512"))
    )
    (comp (ref "R116")
      (value "470K 1%")
      (footprint "eagle-import:0805")
      (fields
        (field (name "HQ_PART") "RE0205756")
        (field (name "LCSC_PART") "C17709")
        (field (name "MANUFACTURER") "Panasonic")
      )
      (libsource (lib "eagle-import") (part "470K-1%0805"))
    )
    (comp (ref "R117")
      (value "470K 1%")
      (footprint "eagle-import:0805")
      (fields
        (field (name "HQ_PART") "RE0205756")
        (field (name "LCSC_PART") "C17709")
        (field (name "MANUFACTURER") "Panasonic")
      )
      (libsource (lib "eagle-import") (part "470K-1%0805"))
    )
    (comp (ref "R118")
      (value "470K 1%")
      (footprint "eagle-import:0805")
      (fields
        (field (name "HQ_PART") "RE0205756")
        (field (name "LCSC_PART") "C17709")
        (field (name "MANUFACTURER") "Panasonic")
      )
      (libsource (lib "eagle-import") (part "470K-1%0805"))
    )
    (comp (ref "R119")
      (value "470K 1%")
      (footprint "eagle-import:0805")
      (fields
        (field (name "HQ_PART") "RE0205756")
        (field (name "LCSC_PART") "C17709")
        (field (name "MANUFACTURER") "Panasonic")
      )
      (libsource (lib "eagle-import") (part "470K-1%0805"))
    )
    (comp (ref "R120")
      (value "1K 1%")
      (footprint "eagle-import:0805")
      (fields
        (field (name "HQ_PART") "RE0203459")
        (field (name "LCSC_PART") "C17513")
        (field (name "MANUFACTURER") "FH")
      )
      (libsource (lib "eagle-import") (part "1K-1%0805"))
    )
    (comp (ref "D1")
      (value "MBRA340T3G")
      (footprint "eagle-import:SMA_DO-214AC")
      (fields
        (field (name "HQ_PART") "DS0002158")
        (field (name "LCSC_PART") "C26178")
        (field (name "MANUFACTURER") "ON")
      )
      (libsource (lib "eagle-import") (part "MBRA340T3G"))
    )
    (comp (ref "D2")
      (value "MBRA340T3G")
      (footprint "eagle-import:SMA_DO-214AC")
      (fields
        (field (name "HQ_PART") "DS0002158")
        (field (name "LCSC_PART") "C26178")
        (field (name "MANUFACTURER") "ON")
      )
      (libsource (lib "eagle-import") (part "MBRA340T3G"))
    )
    (comp (ref "D3")
      (value "MBRA340T3G")
      (footprint "eagle-import:SMA_DO-214AC")
      (fields
        (field (name "HQ_PART") "DS0002158")
        (field (name "LCSC_PART") "C26178")
        (field (name "MANUFACTURER") "ON")
      )
      (libsource (lib "eagle-import") (part "MBRA340T3G"))
    )
    (comp (ref "D4")
      (value "MBRA340T3G")
      (footprint "eagle-import:SMA_DO-214AC")
      (fields
        (field (name "HQ_PART") "DS0002158")
        (field (name "LCSC_PART") "C26178")
        (field (name "MANUFACTURER") "ON")
      )
      (libsource (lib "eagle-import") (part "MBRA340T3G"))
    )
    (comp (ref "D5")
      (value "MBRA340T3G")
      (footprint "eagle-import:SMA_DO-214AC")
      (fields
        (field (name "HQ_PART") "DS0002158")
        (field (name "LCSC_PART") "C26178")
        (field (name "MANUFACTURER") "ON")
      )
      (libsource (lib "eagle-import") (part "MBRA340T3G"))
    )
    (comp (ref "D6")
      (value "MBRA340T3G")
      (footprint "eagle-import:SMA_DO-214AC")
      (fields
        (field (name "HQ_PART") "DS0002158")
        (field (name "LCSC_PART") "C26178")
        (field (name "MANUFACTURER") "ON")
      )
      (libsource (lib "eagle-import") (part "MBRA340T3G"))
    )
    (comp (ref "D7")
      (value "MBRA340T3G")
      (footprint "eagle-import:SMA_DO-214AC")
      (fields
        (field (name "HQ_PART") "DS0002158")
        (field (name "LCSC_PART") "C26178")
        (field (name "MANUFACTURER") "ON")
      )
      (libsource (lib "eagle-import") (part "MBRA340T3G"))
    )
    (comp (ref "D8")
      (value "MBRA340T3G")
      (footprint "eagle-import:SMA_DO-214AC")
      (fields
        (field (name "HQ_PART") "DS0002158")
        (field (name "LCSC_PART") "C26178")
        (field (name "MANUFACTURER") "ON")
      )
      (libsource (lib "eagle-import") (part "MBRA340T3G"))
    )
    (comp (ref "K1")
      (value "G2RL-1A-E DC12")
      (footprint "eagle-import:RELAY_G2RL-1A-E_DC5_OMR")
      (fields (field (name "LCSC_PART") "C1564126") (field (name "MANUFACTURER") "Omron"))
      (libsource (lib "eagle-import") (part "G2RL-1A-E_DC12"))
    )
    (comp (ref "K2")
      (value "G2RL-1A-E DC12")
      (footprint "eagle-import:RELAY_G2RL-1A-E_DC5_OMR")
      (fields (field (name "LCSC_PART") "C1564126") (field (name "MANUFACTURER") "Omron"))
      (libsource (lib "eagle-import") (part "G2RL-1A-E_DC12"))
    )
    (comp (ref "K3")
      (value "G2RL-1A-E DC12")
      (footprint "eagle-import:RELAY_G2RL-1A-E_DC5_OMR")
      (fields (field (name "LCSC_PART") "C1564126") (field (name "MANUFACTURER") "Omron"))
      (libsource (lib "eagle-import") (part "G2RL-1A-E_DC12"))
    )
    (comp (ref "K4")
      (value "G2RL-1A-E DC12")
      (footprint "eagle-import:RELAY_G2RL-1A-E_DC5_OMR")
      (fields (field (name "LCSC_PART") "C1564126") (field (name "MANUFACTURER") "Omron"))
      (libsource (lib "eagle-import") (part "G2RL-1A-E_DC12"))
    )
    (comp (ref "K5")
      (value "G2RL-1A-E DC12")
      (footprint "eagle-import:RELAY_G2RL-1A-E_DC5_OMR")
      (fields (field (name "LCSC_PART") "C1564126") (field (name "MANUFACTURER") "Omron"))
      (libsource (lib "eagle-import") (part "G2RL-1A-E_DC12"))
    )
    (comp (ref "K6")
      (value "G2RL-1A-E DC12")
      (footprint "eagle-import:RELAY_G2RL-1A-E_DC5_OMR")
      (fields (field (name "LCSC_PART") "C1564126") (field (name "MANUFACTURER") "Omron"))
      (libsource (lib "eagle-import") (part "G2RL-1A-E_DC12"))
    )
    (comp (ref "K7")
      (value "G2RL-1A-E DC12")
      (footprint "eagle-import:RELAY_G2RL-1A-E_DC5_OMR")
      (fields (field (name "LCSC_PART") "C1564126") (field (name "MANUFACTURER") "Omron"))
      (libsource (lib "eagle-import") (part "G2RL-1A-E_DC12"))
    )
    (comp (ref "K8")
      (value "G2RL-1A-E DC12")
      (footprint "eagle-import:RELAY_G2RL-1A-E_DC5_OMR")
      (fields (field (name "LCSC_PART") "C1564126") (field (name "MANUFACTURER") "Omron"))
      (libsource (lib "eagle-import") (part "G2RL-1A-E_DC12"))
    )
    (comp (ref "3VDC")
      (value "DNI")
      (footprint "eagle-import:TP-ROUND")
      (libsource (lib "eagle-import") (part "TP-ROUND"))
    )
    (comp (ref "3VFB")
      (value "DNI")
      (footprint "eagle-import:TP-ROUND")
      (libsource (lib "eagle-import") (part "TP-ROUND"))
    )
    (comp (ref "5VDC")
      (value "DNI")
      (footprint "eagle-import:TP-ROUND")
      (libsource (lib "eagle-import") (part "TP-ROUND"))
    )
    (comp (ref "5VFB")
      (value "DNI")
      (footprint "eagle-import:TP-ROUND")
      (libsource (lib "eagle-import") (part "TP-ROUND"))
    )
    (comp (ref "C1")
      (value "22uF 25V")
      (footprint "eagle-import:1206")
      (fields
        (field (name "HQ_PART") "CA0182777")
        (field (name "LCSC_PART") "C12891")
        (field (name "MANUFACTURER") "FH")
      )
      (libsource (lib "eagle-import") (part "22UF-25V-1206"))
    )
    (comp (ref "C2")
      (value "22uF 25V")
      (footprint "eagle-import:1206")
      (fields
        (field (name "HQ_PART") "CA0182777")
        (field (name "LCSC_PART") "C12891")
        (field (name "MANUFACTURER") "FH")
      )
      (libsource (lib "eagle-import") (part "22UF-25V-1206"))
    )
    (comp (ref "C3")
      (value "100nF 25V")
      (footprint "eagle-import:0402")
      (fields
        (field (name "HQ_PART") "CA0176807")
        (field (name "LCSC_PART") "C56392")
        (field (name "MANUFACTURER") "Walsin")
      )
      (libsource (lib "eagle-import") (part "100NF-25V-0402"))
    )
    (comp (ref "C4")
      (value "100nF 25V")
      (footprint "eagle-import:0402")
      (fields
        (field (name "HQ_PART") "CA0176807")
        (field (name "LCSC_PART") "C56392")
        (field (name "MANUFACTURER") "Walsin")
      )
      (libsource (lib "eagle-import") (part "100NF-25V-0402"))
    )
    (comp (ref "C6")
      (value "100nF 25V")
      (footprint "eagle-import:0402")
      (fields
        (field (name "HQ_PART") "CA0176807")
        (field (name "LCSC_PART") "C56392")
        (field (name "MANUFACTURER") "Walsin")
      )
      (libsource (lib "eagle-import") (part "100NF-25V-0402"))
    )
    (comp (ref "C7")
      (value "100nF 25V")
      (footprint "eagle-import:0402")
      (fields
        (field (name "HQ_PART") "CA0176807")
        (field (name "LCSC_PART") "C56392")
        (field (name "MANUFACTURER") "Walsin")
      )
      (libsource (lib "eagle-import") (part "100NF-25V-0402"))
    )
    (comp (ref "C8")
      (value "100nF 25V")
      (footprint "eagle-import:0402")
      (fields
        (field (name "HQ_PART") "CA0176807")
        (field (name "LCSC_PART") "C56392")
        (field (name "MANUFACTURER") "Walsin")
      )
      (libsource (lib "eagle-import") (part "100NF-25V-0402"))
    )
    (comp (ref "C9")
      (value "100nF 25V")
      (footprint "eagle-import:0402")
      (fields
        (field (name "HQ_PART") "CA0176807")
        (field (name "LCSC_PART") "C56392")
        (field (name "MANUFACTURER") "Walsin")
      )
      (libsource (lib "eagle-import") (part "100NF-25V-0402"))
    )
    (comp (ref "C11")
      (value "33pF 50V")
      (footprint "eagle-import:0402")
      (fields
        (field (name "HQ_PART") "CA0484207")
        (field (name "LCSC_PART") "C107005")
        (field (name "MANUFACTURER") "PSA")
      )
      (libsource (lib "eagle-import") (part "33PF-50V0402"))
    )
    (comp (ref "C12")
      (value "33pF 50V")
      (footprint "eagle-import:0402")
      (fields
        (field (name "HQ_PART") "CA0484207")
        (field (name "LCSC_PART") "C107005")
        (field (name "MANUFACTURER") "PSA")
      )
      (libsource (lib "eagle-import") (part "33PF-50V0402"))
    )
    (comp (ref "C14")
      (value "22uF 25V")
      (footprint "eagle-import:1206")
      (fields
        (field (name "HQ_PART") "CA0182777")
        (field (name "LCSC_PART") "C12891")
        (field (name "MANUFACTURER") "FH")
      )
      (libsource (lib "eagle-import") (part "22UF-25V-1206"))
    )
    (comp (ref "C15")
      (value "22uF 25V")
      (footprint "eagle-import:1206")
      (fields
        (field (name "HQ_PART") "CA0182777")
        (field (name "LCSC_PART") "C12891")
        (field (name "MANUFACTURER") "FH")
      )
      (libsource (lib "eagle-import") (part "22UF-25V-1206"))
    )
    (comp (ref "C17")
      (value "22uF 25V")
      (footprint "eagle-import:1206")
      (fields
        (field (name "HQ_PART") "CA0182777")
        (field (name "LCSC_PART") "C12891")
        (field (name "MANUFACTURER") "FH")
      )
      (libsource (lib "eagle-import") (part "22UF-25V-1206"))
    )
    (comp (ref "C18")
      (value "22uF 25V")
      (footprint "eagle-import:1206")
      (fields
        (field (name "HQ_PART") "CA0182777")
        (field (name "LCSC_PART") "C12891")
        (field (name "MANUFACTURER") "FH")
      )
      (libsource (lib "eagle-import") (part "22UF-25V-1206"))
    )
    (comp (ref "C97")
      (value "10uF 50V")
      (footprint "eagle-import:0805")
      (fields (field (name "LCSC_PART") "C440198"))
      (libsource (lib "eagle-import") (part "10UF-50V-0805"))
    )
    (comp (ref "C98")
      (value "100nF 25V")
      (footprint "eagle-import:0201")
      (fields
        (field (name "HQ_PART") "CA0183221")
        (field (name "LCSC_PART") "C76939")
        (field (name "MANUFACTURER") "Samsung")
      )
      (libsource (lib "eagle-import") (part "100NF-25V-0201"))
    )
    (comp (ref "C99")
      (value "10uF 50V")
      (footprint "eagle-import:0805")
      (fields (field (name "LCSC_PART") "C440198"))
      (libsource (lib "eagle-import") (part "10UF-50V-0805"))
    )
    (comp (ref "C100")
      (value "100nF 25V")
      (footprint "eagle-import:0201")
      (fields
        (field (name "HQ_PART") "CA0183221")
        (field (name "LCSC_PART") "C76939")
        (field (name "MANUFACTURER") "Samsung")
      )
      (libsource (lib "eagle-import") (part "100NF-25V-0201"))
    )
    (comp (ref "D15")
      (value "DNI")
      (footprint "eagle-import:SMA_DO-214AC")
      (fields
        (field (name "HQ_PART") "DS0145075")
        (field (name "LCSC_PART") "C727049")
        (field (name "MANUFACTURER") "MDD")
      )
      (libsource (lib "eagle-import") (part "SS12"))
    )
    (comp (ref "GND")
      (value "DNI")
      (footprint "eagle-import:TP-ROUND")
      (libsource (lib "eagle-import") (part "TP-ROUND"))
    )
    (comp (ref "GND-3")
      (value "DNI")
      (footprint "eagle-import:TP-ROUND")
      (libsource (lib "eagle-import") (part "TP-ROUND"))
    )
    (comp (ref "GND-5")
      (value "DNI")
      (footprint "eagle-import:TP-ROUND")
      (libsource (lib "eagle-import") (part "TP-ROUND"))
    )
    (comp (ref "IC1")
      (value "DNI")
      (footprint "eagle-import:SOT65P280X110-8N")
      (fields
        (field (name "HQ_PART") "IC0339027")
        (field (name "LCSC_PART") "C45889")
        (field (name "MANUFACTURER") "MPS")
      )
      (libsource (lib "eagle-import") (part "MP2315TSOT23-8"))
    )
    (comp (ref "IC2")
      (value "MP2315GJ-Z")
      (footprint "eagle-import:SOT65P280X110-8N")
      (fields
        (field (name "HQ_PART") "IC0339027")
        (field (name "LCSC_PART") "C45889")
        (field (name "MANUFACTURER") "MPS")
      )
      (libsource (lib "eagle-import") (part "MP2315TSOT23-8"))
    )
    (comp (ref "IC21")
      (value "MIC5504-3.3YM5")
      (footprint "eagle-import:SOT23-5")
      (fields
        (field (name "HQ_PART") "IC0230296")
        (field (name "LCSC_PART") "C41348078")
        (field (name "MANUFACTURER") "Microchip")
      )
      (libsource (lib "eagle-import") (part "MIC5504-3.3YM5-TR"))
    )
    (comp (ref "L1")
      (value "DNI")
      (footprint "eagle-import:SRR5228A")
      (fields
        (field (name "HQ_PART") "IN0027228")
        (field (name "LCSC_PART") "C325964")
        (field (name "MANUFACTURER") "YJYCOIN")
      )
      (libsource (lib "eagle-import") (part "4.7UH"))
    )
    (comp (ref "L2")
      (value "4.7uH 3.5A")
      (footprint "eagle-import:SRR5228A")
      (fields
        (field (name "LCSC_PART") "C14258")
        (field (name "MANUFACTURER") "SXN")
        (field (name "MPN") "YP0503-4R7M")
      )
      (libsource (lib "eagle-import") (part "4.2UH"))
    )
    (comp (ref "P3ON")
      (value "Green")
      (footprint "eagle-import:LED-0603")
      (fields
        (field (name "HQ_PART") "PH0010430")
        (field (name "LCSC_PART") "C965804")
        (field (name "MANUFACTURER") "Wurth")
      )
      (libsource (lib "eagle-import") (part "LED-GREENLED-0603"))
    )
    (comp (ref "P5ON")
      (value "DNI")
      (footprint "eagle-import:LED-0603")
      (fields
        (field (name "HQ_PART") "PH0010430")
        (field (name "LCSC_PART") "C965804")
        (field (name "MANUFACTURER") "Wurth")
      )
      (libsource (lib "eagle-import") (part "LED-GREENLED-0603"))
    )
    (comp (ref "PWR")
      (value "Green")
      (footprint "eagle-import:LED-0603")
      (fields
        (field (name "HQ_PART") "PH0010430")
        (field (name "LCSC_PART") "C965804")
        (field (name "MANUFACTURER") "Wurth")
      )
      (libsource (lib "eagle-import") (part "LED-GREENLED-0603"))
    )
    (comp (ref "R1")
      (value "DNI")
      (footprint "eagle-import:0402")
      (libsource (lib "eagle-import") (part "R0402"))
    )
    (comp (ref "R2")
      (value "10K 1%")
      (footprint "eagle-import:0402")
      (fields
        (field (name "HQ_PART") "RE0207399")
        (field (name "LCSC_PART") "C25744")
        (field (name "MANUFACTURER") "ROHM")
      )
      (libsource (lib "eagle-import") (part "10K-1%0402"))
    )
    (comp (ref "R3")
      (value "100K 1%")
      (footprint "eagle-import:0402")
      (fields
        (field (name "HQ_PART") "RE0203322")
        (field (name "LCSC_PART") "C25741")
        (field (name "MANUFACTURER") "FH")
      )
      (libsource (lib "eagle-import") (part "100K-1%0402"))
    )
    (comp (ref "R4")
      (value "9.09K 1%")
      (footprint "eagle-import:0402")
      (fields
        (field (name "HQ_PART") "RE0203888")
        (field (name "LCSC_PART") "C11549")
        (field (name "MANUFACTURER") "Yageo")
      )
      (libsource (lib "eagle-import") (part "9.09K-1%0402"))
    )
    (comp (ref "R5")
      (value "100K 1%")
      (footprint "eagle-import:0402")
      (fields
        (field (name "HQ_PART") "RE0203322")
        (field (name "LCSC_PART") "C25741")
        (field (name "MANUFACTURER") "FH")
      )
      (libsource (lib "eagle-import") (part "100K-1%0402"))
    )
    (comp (ref "R6")
      (value "7.5K 1%")
      (footprint "eagle-import:0402")
      (fields
        (field (name "HQ_PART") "RE0188271")
        (field (name "LCSC_PART") "C25918")
        (field (name "MANUFACTURER") "Uniohm")
      )
      (libsource (lib "eagle-import") (part "7.5K-1%0402"))
    )
    (comp (ref "R7")
      (value "10R 1%")
      (footprint "eagle-import:0402")
      (fields
        (field (name "HQ_PART") "RE0191560")
        (field (name "LCSC_PART") "C25077")
        (field (name "MANUFACTURER") "Uniohm")
      )
      (libsource (lib "eagle-import") (part "10R-1%0402"))
    )
    (comp (ref "R8")
      (value "20K 1%")
      (footprint "eagle-import:0402")
      (fields
        (field (name "HQ_PART") "RE0203337")
        (field (name "LCSC_PART") "C25765")
        (field (name "MANUFACTURER") "FH")
      )
      (libsource (lib "eagle-import") (part "20K-1%0402"))
    )
    (comp (ref "R9")
      (value "10R 1%")
      (footprint "eagle-import:0402")
      (fields
        (field (name "HQ_PART") "RE0191560")
        (field (name "LCSC_PART") "C25077")
        (field (name "MANUFACTURER") "Uniohm")
      )
      (libsource (lib "eagle-import") (part "10R-1%0402"))
    )
    (comp (ref "R10")
      (value "33K 1%")
      (footprint "eagle-import:0402")
      (fields
        (field (name "HQ_PART") "RE0321838")
        (field (name "LCSC_PART") "C25779")
        (field (name "MANUFACTURER") "RALEC")
      )
      (libsource (lib "eagle-import") (part "33K-1%0402"))
    )
    (comp (ref "R11")
      (value "40.2K 1%")
      (footprint "eagle-import:0402")
      (fields
        (field (name "HQ_PART") "RE0063264")
        (field (name "LCSC_PART") "C25893")
        (field (name "MANUFACTURER") "Yageo")
      )
      (libsource (lib "eagle-import") (part "40.2K-1%0402"))
    )
    (comp (ref "R12")
      (value "7.5K 1%")
      (footprint "eagle-import:0402")
      (fields
        (field (name "HQ_PART") "RE0188271")
        (field (name "LCSC_PART") "C25918")
        (field (name "MANUFACTURER") "Uniohm")
      )
      (libsource (lib "eagle-import") (part "7.5K-1%0402"))
    )
    (comp (ref "R13")
      (value "40.2K 1%")
      (footprint "eagle-import:0402")
      (fields
        (field (name "HQ_PART") "RE0063264")
        (field (name "LCSC_PART") "C25893")
        (field (name "MANUFACTURER") "Yageo")
      )
      (libsource (lib "eagle-import") (part "40.2K-1%0402"))
    )
    (comp (ref "R14")
      (value "12.7K 1%")
      (footprint "eagle-import:0402")
      (fields
        (field (name "HQ_PART") "RE0202294")
        (field (name "LCSC_PART") "C25853")
        (field (name "MANUFACTURER") "Yageo")
      )
      (libsource (lib "eagle-import") (part "12.7K-1%0402"))
    )
    (comp (ref "R123")
      (value "1K 1%")
      (footprint "eagle-import:0402")
      (fields
        (field (name "HQ_PART") "RE0208724")
        (field (name "LCSC_PART") "C11702")
        (field (name "MANUFACTURER") "FH")
      )
      (libsource (lib "eagle-import") (part "1K-1%0402"))
    )
    (comp (ref "R148")
      (value "2.4K 1%")
      (footprint "eagle-import:0402")
      (fields
        (field (name "HQ_PART") "RE0202491")
        (field (name "LCSC_PART") "C25882")
        (field (name "MANUFACTURER") "LIZ")
      )
      (libsource (lib "eagle-import") (part "2.4K-1%0402"))
    )
    (comp (ref "R151")
      (value "1K 1%")
      (footprint "eagle-import:0402")
      (fields
        (field (name "HQ_PART") "RE0208724")
        (field (name "LCSC_PART") "C11702")
        (field (name "MANUFACTURER") "FH")
      )
      (libsource (lib "eagle-import") (part "1K-1%0402"))
    )
    (comp (ref "R161")
      (value "DNI")
      (footprint "eagle-import:0402")
      (libsource (lib "eagle-import") (part "R0402"))
    )
    (comp (ref "R162")
      (value "10K 1%")
      (footprint "eagle-import:0402")
      (fields
        (field (name "HQ_PART") "RE0207399")
        (field (name "LCSC_PART") "C25744")
        (field (name "MANUFACTURER") "ROHM")
      )
      (libsource (lib "eagle-import") (part "10K-1%0402"))
    )
    (comp (ref "R169")
      (value "0R 1%")
      (footprint "eagle-import:1206")
      (fields
        (field (name "PACKAGE") "1206")
        (field (name "HQ_PART") "RE0209081")
        (field (name "LCSC_PART") "C205296")
        (field (name "MANUFACTURER") "RALEC")
      )
      (libsource (lib "eagle-import") (part "0R1206"))
    )
    (comp (ref "R171")
      (value "33K 1%")
      (footprint "eagle-import:0402")
      (fields
        (field (name "HQ_PART") "RE0321838")
        (field (name "LCSC_PART") "C25779")
        (field (name "MANUFACTURER") "RALEC")
      )
      (libsource (lib "eagle-import") (part "33K-1%0402"))
    )
    (comp (ref "R172")
      (value "DNI")
      (footprint "eagle-import:0402")
      (libsource (lib "eagle-import") (part "R0402"))
    )
    (comp (ref "SW")
      (value "DNI")
      (footprint "eagle-import:TP-ROUND")
      (libsource (lib "eagle-import") (part "TP-ROUND"))
    )
    (comp (ref "SW3")
      (value "DNI")
      (footprint "eagle-import:TP-ROUND")
      (libsource (lib "eagle-import") (part "TP-ROUND"))
    )
    (comp (ref "ADCUSB")
      (value "DNI")
      (footprint "eagle-import:TP-ROUND")
      (libsource (lib "eagle-import") (part "TP-ROUND"))
    )
    (comp (ref "ADC_TEMP")
      (value "DNI")
      (footprint "eagle-import:TP-ROUND")
      (libsource (lib "eagle-import") (part "TP-ROUND"))
    )
    (comp (ref "C65")
      (value "10uF 50V")
      (footprint "eagle-import:0805")
      (fields (field (name "LCSC_PART") "C440198"))
      (libsource (lib "eagle-import") (part "10UF-50V-0805"))
    )
    (comp (ref "C66")
      (value "100nF 25V")
      (footprint "eagle-import:0402")
      (fields
        (field (name "HQ_PART") "CA0176807")
        (field (name "LCSC_PART") "C56392")
        (field (name "MANUFACTURER") "Walsin")
      )
      (libsource (lib "eagle-import") (part "100NF-25V-0402"))
    )
    (comp (ref "C78")
      (value "4.7nF 50V")
      (footprint "eagle-import:0402")
      (fields
        (field (name "HQ_PART") "CA0176643")
        (field (name "LCSC_PART") "C1538")
        (field (name "MANUFACTURER") "Walsin")
      )
      (libsource (lib "eagle-import") (part "4.7NF-50V0402"))
    )
    (comp (ref "C105")
      (value "100nF 25V")
      (footprint "eagle-import:0201")
      (fields
        (field (name "HQ_PART") "CA0183221")
        (field (name "LCSC_PART") "C76939")
        (field (name "MANUFACTURER") "Samsung")
      )
      (libsource (lib "eagle-import") (part "100NF-25V-0201"))
    )
    (comp (ref "DSP")
      (value "AFC11-S20ICC-00")
      (footprint "eagle-import:FPC20")
      (fields
        (field (name "HQ_PART") "CO0889517")
        (field (name "LCSC_PART") "C466537")
        (field (name "MANUFACTURER") "JS")
      )
      (libsource (lib "eagle-import") (part "AFC11-S20ICC-00"))
    )
    (comp (ref "ESD1")
      (value "SP0503BAHTG")
      (footprint "eagle-import:SOT143")
      (fields
        (field (name "HQ_PART") "CP0003989")
        (field (name "LCSC_PART") "C3040626")
        (field (name "MANUFACTURER") "Littelfuse")
      )
      (libsource (lib "eagle-import") (part "SP0503BAHT"))
    )
    (comp (ref "FAN")
      (value "DNI")
      (footprint "eagle-import:02P")
      (libsource (lib "eagle-import") (part "M02"))
    )
    (comp (ref "FCTL")
      (value "DNI")
      (footprint "eagle-import:TP-ROUND")
      (libsource (lib "eagle-import") (part "TP-ROUND"))
    )
    (comp (ref "GDRC")
      (value "DNI")
      (footprint "eagle-import:1X4")
      (libsource (lib "eagle-import") (part "CON-1X4"))
    )
    (comp (ref "IC19")
      (value "CAT24C256HU4IGT3")
      (footprint "eagle-import:SON50P300X200X50-9T130X140N")
      (fields
        (field (name "HQ_PART") "IC0066897")
        (field (name "LCSC_PART") "C233771")
        (field (name "MANUFACTURER") "ON")
      )
      (libsource (lib "eagle-import") (part "CAT24C256-HU4"))
    )
    (comp (ref "IC23")
      (value "MCP9700AT-E/LT")
      (footprint "eagle-import:SC70-5")
      (fields (field (name "LCSC_PART") "C97546") (field (name "MANUFACTURER") "Microchip "))
      (libsource (lib "eagle-import") (part "MCP9700AT-E/LT"))
    )
    (comp (ref "R121")
      (value "2.2K 1%")
      (footprint "eagle-import:0201")
      (fields
        (field (name "HQ_PART") "RE0209901")
        (field (name "LCSC_PART") "C473508")
        (field (name "MANUFACTURER") "FH")
      )
      (libsource (lib "eagle-import") (part "2.2K-1%0201"))
    )
    (comp (ref "R124")
      (value "5.1K 1%")
      (footprint "eagle-import:0201")
      (fields
        (field (name "HQ_PART") "RE0185972")
        (field (name "LCSC_PART") "C274341")
        (field (name "MANUFACTURER") "Yageo")
      )
      (libsource (lib "eagle-import") (part "5.1K-1%0201"))
    )
    (comp (ref "R125")
      (value "5.1K 1%")
      (footprint "eagle-import:0201")
      (fields
        (field (name "HQ_PART") "RE0185972")
        (field (name "LCSC_PART") "C274341")
        (field (name "MANUFACTURER") "Yageo")
      )
      (libsource (lib "eagle-import") (part "5.1K-1%0201"))
    )
    (comp (ref "R126")
      (value "10K 1%")
      (footprint "eagle-import:0201")
      (fields
        (field (name "HQ_PART") "RE0208620")
        (field (name "LCSC_PART") "C473048")
        (field (name "MANUFACTURER") "FH")
      )
      (libsource (lib "eagle-import") (part "10K-1%0201"))
    )
    (comp (ref "R127")
      (value "10K 1%")
      (footprint "eagle-import:0201")
      (fields
        (field (name "HQ_PART") "RE0208620")
        (field (name "LCSC_PART") "C473048")
        (field (name "MANUFACTURER") "FH")
      )
      (libsource (lib "eagle-import") (part "10K-1%0201"))
    )
    (comp (ref "R128")
      (value "DNI")
      (footprint "eagle-import:R0201")
      (libsource (lib "eagle-import") (part "R0201"))
    )
    (comp (ref "R129")
      (value "4.7K 1%")
      (footprint "eagle-import:0201")
      (fields
        (field (name "HQ_PART") "RE0208670")
        (field (name "LCSC_PART") "C270346")
        (field (name "MANUFACTURER") "RALEC")
      )
      (libsource (lib "eagle-import") (part "4.7K-1%0201"))
    )
    (comp (ref "R131")
      (value "1M 1%")
      (footprint "eagle-import:0402")
      (fields
        (field (name "HQ_PART") "RE0055809")
        (field (name "LCSC_PART") "C26083")
        (field (name "MANUFACTURER") "Vishay")
      )
      (libsource (lib "eagle-import") (part "1M-1%0402"))
    )
    (comp (ref "R147")
      (value "1K 1%")
      (footprint "eagle-import:0402")
      (fields
        (field (name "HQ_PART") "RE0207399")
        (field (name "LCSC_PART") "C25744")
        (field (name "MANUFACTURER") "ROHM")
      )
      (libsource (lib "eagle-import") (part "10K-1%0402"))
    )
    (comp (ref "R149")
      (value "DNI")
      (footprint "eagle-import:_0603X4-1206")
      (fields
        (field (name "HQ_PART") "RE0093863")
        (field (name "LCSC_PART") "C1734380")
        (field (name "MANUFACTURER") "Yageo")
      )
      (libsource (lib "eagle-import") (part "3.3K-1%_ARRAY0603X4-1206"))
    )
    (comp (ref "R164")
      (value "10K 1%")
      (footprint "eagle-import:0402")
      (fields
        (field (name "HQ_PART") "RE0207399")
        (field (name "LCSC_PART") "C25744")
        (field (name "MANUFACTURER") "ROHM")
      )
      (libsource (lib "eagle-import") (part "10K-1%0402"))
    )
    (comp (ref "R165")
      (value "DNI")
      (footprint "eagle-import:R0201")
      (libsource (lib "eagle-import") (part "R0201"))
    )
    (comp (ref "R170")
      (value "DNI")
      (footprint "eagle-import:1206")
      (fields
        (field (name "PACKAGE") "1206")
        (field (name "HQ_PART") "RE0209081")
        (field (name "LCSC_PART") "C205296")
        (field (name "MANUFACTURER") "RALEC")
      )
      (libsource (lib "eagle-import") (part "0R1206"))
    )
    (comp (ref "RGTG")
      (value "DNI")
      (footprint "eagle-import:1X4")
      (libsource (lib "eagle-import") (part "CON-1X4"))
    )
    (comp (ref "T1")
      (value "BSS138")
      (footprint "eagle-import:SOT23")
      (fields (field (name "HQ_PART") "DS0190318") (field (name "MANUFACTURER") "HUASHUO"))
      (libsource (lib "eagle-import") (part "BSS138"))
    )
    (comp (ref "USB1")
      (value "USB-TYPE-C-018")
      (footprint "eagle-import:USB-C")
      (fields
        (field (name "HQ_PART") "ZHLM0322915")
        (field (name "LCSC_PART") "C2927038")
        (field (name "MANUFACTURER") "DEALON")
      )
      (libsource (lib "eagle-import") (part "USB_C-THT"))
    )
    (comp (ref "VBUS")
      (value "DNI")
      (footprint "eagle-import:TP-ROUND")
      (libsource (lib "eagle-import") (part "TP-ROUND"))
    )
    (comp (ref "C106")
      (value "1nF 25V")
      (footprint "eagle-import:0201")
      (fields
        (field (name "HQ_PART") "CA0136821")
        (field (name "LCSC_PART") "C7694325V")
        (field (name "MANUFACTURER") "Samsung")
      )
      (libsource (lib "eagle-import") (part "1NF-25V-0201"))
    )
    (comp (ref "C107")
      (value "1nF 25V")
      (footprint "eagle-import:0201")
      (fields
        (field (name "HQ_PART") "CA0136821")
        (field (name "LCSC_PART") "C7694325V")
        (field (name "MANUFACTURER") "Samsung")
      )
      (libsource (lib "eagle-import") (part "1NF-25V-0201"))
    )
    (comp (ref "C108")
      (value "1nF 25V")
      (footprint "eagle-import:0201")
      (fields
        (field (name "HQ_PART") "CA0136821")
        (field (name "LCSC_PART") "C7694325V")
        (field (name "MANUFACTURER") "Samsung")
      )
      (libsource (lib "eagle-import") (part "1NF-25V-0201"))
    )
    (comp (ref "C109")
      (value "1nF 25V")
      (footprint "eagle-import:0201")
      (fields
        (field (name "HQ_PART") "CA0136821")
        (field (name "LCSC_PART") "C7694325V")
        (field (name "MANUFACTURER") "Samsung")
      )
      (libsource (lib "eagle-import") (part "1NF-25V-0201"))
    )
    (comp (ref "C110")
      (value "1nF 25V")
      (footprint "eagle-import:0201")
      (fields
        (field (name "HQ_PART") "CA0136821")
        (field (name "LCSC_PART") "C7694325V")
        (field (name "MANUFACTURER") "Samsung")
      )
      (libsource (lib "eagle-import") (part "1NF-25V-0201"))
    )
    (comp (ref "C111")
      (value "1nF 25V")
      (footprint "eagle-import:0201")
      (fields
        (field (name "HQ_PART") "CA0136821")
        (field (name "LCSC_PART") "C7694325V")
        (field (name "MANUFACTURER") "Samsung")
      )
      (libsource (lib "eagle-import") (part "1NF-25V-0201"))
    )
    (comp (ref "C112")
      (value "1nF 25V")
      (footprint "eagle-import:0201")
      (fields
        (field (name "HQ_PART") "CA0136821")
        (field (name "LCSC_PART") "C7694325V")
        (field (name "MANUFACTURER") "Samsung")
      )
      (libsource (lib "eagle-import") (part "1NF-25V-0201"))
    )
    (comp (ref "C113")
      (value "1nF 25V")
      (footprint "eagle-import:0201")
      (fields
        (field (name "HQ_PART") "CA0136821")
        (field (name "LCSC_PART") "C7694325V")
        (field (name "MANUFACTURER") "Samsung")
      )
      (libsource (lib "eagle-import") (part "1NF-25V-0201"))
    )
    (comp (ref "OPT1")
      (value "ACPL-247-500E")
      (footprint "eagle-import:SO16")
      (fields
        (field (name "HQ_PART") "IS0001505")
        (field (name "LCSC_PART") "C188681")
        (field (name "MANUFACTURER") "Broadcom")
      )
      (libsource (lib "eagle-import") (part "ACPL-2471"))
    )
    (comp (ref "OPT2")
      (value "ACPL-247-500E")
      (footprint "eagle-import:SO16")
      (fields
        (field (name "HQ_PART") "IS0001505")
        (field (name "LCSC_PART") "C188681")
        (field (name "MANUFACTURER") "Broadcom")
      )
      (libsource (lib "eagle-import") (part "ACPL-2471"))
    )
    (comp (ref "R59")
      (value "1K 1%")
      (footprint "eagle-import:0201")
      (fields
        (field (name "HQ_PART") "RE0015967")
        (field (name "LCSC_PART") "C270365")
        (field (name "MANUFACTURER") "Yageo")
      )
      (libsource (lib "eagle-import") (part "1K-1%0201"))
    )
    (comp (ref "R63")
      (value "1K 1%")
      (footprint "eagle-import:_0603X4-1206")
      (fields
        (field (name "HQ_PART") "RE0022532")
        (field (name "LCSC_PART") "C110021")
        (field (name "MANUFACTURER") "Yageo")
      )
      (libsource (lib "eagle-import") (part "1K-1%_ARRAY0603X4-1206"))
    )
    (comp (ref "R64")
      (value "1K 1%")
      (footprint "eagle-import:_0603X4-1206")
      (fields
        (field (name "HQ_PART") "RE0022532")
        (field (name "LCSC_PART") "C110021")
        (field (name "MANUFACTURER") "Yageo")
      )
      (libsource (lib "eagle-import") (part "1K-1%_ARRAY0603X4-1206"))
    )
    (comp (ref "R89")
      (value "10K 1%")
      (footprint "eagle-import:_0603X4-1206")
      (fields
        (field (name "HQ_PART") "RE0094682")
        (field (name "LCSC_PART") "C110924")
        (field (name "MANUFACTURER") "Yageo")
      )
      (libsource (lib "eagle-import") (part "10K-1%_ARRAY0603X4-1206"))
    )
    (comp (ref "R90")
      (value "10K 1%")
      (footprint "eagle-import:_0603X4-1206")
      (fields
        (field (name "HQ_PART") "RE0094682")
        (field (name "LCSC_PART") "C110924")
        (field (name "MANUFACTURER") "Yageo")
      )
      (libsource (lib "eagle-import") (part "10K-1%_ARRAY0603X4-1206"))
    )
    (comp (ref "R153")
      (value "1K 1%")
      (footprint "eagle-import:0201")
      (fields
        (field (name "HQ_PART") "RE0015967")
        (field (name "LCSC_PART") "C270365")
        (field (name "MANUFACTURER") "Yageo")
      )
      (libsource (lib "eagle-import") (part "1K-1%0201"))
    )
    (comp (ref "R154")
      (value "1K 1%")
      (footprint "eagle-import:0201")
      (fields
        (field (name "HQ_PART") "RE0015967")
        (field (name "LCSC_PART") "C270365")
        (field (name "MANUFACTURER") "Yageo")
      )
      (libsource (lib "eagle-import") (part "1K-1%0201"))
    )
    (comp (ref "R155")
      (value "1K 1%")
      (footprint "eagle-import:0201")
      (fields
        (field (name "HQ_PART") "RE0015967")
        (field (name "LCSC_PART") "C270365")
        (field (name "MANUFACTURER") "Yageo")
      )
      (libsource (lib "eagle-import") (part "1K-1%0201"))
    )
    (comp (ref "R156")
      (value "1K 1%")
      (footprint "eagle-import:0201")
      (fields
        (field (name "HQ_PART") "RE0015967")
        (field (name "LCSC_PART") "C270365")
        (field (name "MANUFACTURER") "Yageo")
      )
      (libsource (lib "eagle-import") (part "1K-1%0201"))
    )
    (comp (ref "R157")
      (value "1K 1%")
      (footprint "eagle-import:0201")
      (fields
        (field (name "HQ_PART") "RE0015967")
        (field (name "LCSC_PART") "C270365")
        (field (name "MANUFACTURER") "Yageo")
      )
      (libsource (lib "eagle-import") (part "1K-1%0201"))
    )
    (comp (ref "R158")
      (value "1K 1%")
      (footprint "eagle-import:0201")
      (fields
        (field (name "HQ_PART") "RE0015967")
        (field (name "LCSC_PART") "C270365")
        (field (name "MANUFACTURER") "Yageo")
      )
      (libsource (lib "eagle-import") (part "1K-1%0201"))
    )
    (comp (ref "R159")
      (value "1K 1%")
      (footprint "eagle-import:0201")
      (fields
        (field (name "HQ_PART") "RE0015967")
        (field (name "LCSC_PART") "C270365")
        (field (name "MANUFACTURER") "Yageo")
      )
      (libsource (lib "eagle-import") (part "1K-1%0201"))
    )
    (comp (ref "5V-NI1")
      (value "DNI")
      (footprint "eagle-import:TP-ROUND")
      (libsource (lib "eagle-import") (part "TP-ROUND"))
    )
    (comp (ref "5V-NI2")
      (value "DNI")
      (footprint "eagle-import:TP-ROUND")
      (libsource (lib "eagle-import") (part "TP-ROUND"))
    )
    (comp (ref "12VDC")
      (value "DNI")
      (footprint "eagle-import:TP-ROUND")
      (libsource (lib "eagle-import") (part "TP-ROUND"))
    )
    (comp (ref "AC/DC1")
      (value "IRM_10_12")
      (footprint "eagle-import:IRM_10_12")
      (fields
        (field (name "HQ_PART") "ZHLM0215926")
        (field (name "LCSC_PART") "C42418573")
        (field (name "MANUFACTURER") "MW")
      )
      (libsource (lib "eagle-import") (part "IRM_10_12"))
    )
    (comp (ref "AC/DC2")
      (value "IRM-15-12")
      (footprint "eagle-import:IRM_15_12")
      (fields (field (name "LCSC_PART") "C5439799"))
      (libsource (lib "eagle-import") (part "IRM_10_12-2"))
    )
    (comp (ref "AC_L")
      (value "FASTON-1217861-1")
      (footprint "eagle-import:1217861-1")
      (fields
        (field (name "LCSC_PART") "C428480")
        (field (name "MANUFACTURER") "TE CONNECTIVITY")
        (field (name "MPN") "1217861-1")
      )
      (libsource (lib "eagle-import") (part "FASTON-1217861-1"))
    )
    (comp (ref "AC_N")
      (value "FASTON-1217861-1")
      (footprint "eagle-import:1217861-1")
      (fields
        (field (name "LCSC_PART") "C428480")
        (field (name "MANUFACTURER") "TE CONNECTIVITY")
        (field (name "MPN") "1217861-1")
      )
      (libsource (lib "eagle-import") (part "FASTON-1217861-1"))
    )
    (comp (ref "ADC12")
      (value "DNI")
      (footprint "eagle-import:TP-ROUND")
      (libsource (lib "eagle-import") (part "TP-ROUND"))
    )
    (comp (ref "C5")
      (value "1nF 50V")
      (footprint "eagle-import:0603")
      (fields
        (field (name "HQ_PART") "CA0481650")
        (field (name "LCSC_PART") "C1588")
        (field (name "MANUFACTURER") "TDK")
      )
      (libsource (lib "eagle-import") (part "1NF-50V-0603"))
    )
    (comp (ref "C10")
      (value "100uF 25V")
      (footprint "eagle-import:6.3X7.7(DXL)")
      (fields
        (field (name "HQ_PART") "CA0362255")
        (field (name "LCSC_PART") "C267469")
        (field (name "MANUFACTURER") "HONOR")
      )
      (libsource (lib "eagle-import") (part "100UF-25V6.3X7.7(DXL)"))
    )
    (comp (ref "C13")
      (value "100uF 25V")
      (footprint "eagle-import:6.3X7.7(DXL)")
      (fields
        (field (name "HQ_PART") "CA0362255")
        (field (name "LCSC_PART") "C267469")
        (field (name "MANUFACTURER") "HONOR")
      )
      (libsource (lib "eagle-import") (part "100UF-25V6.3X7.7(DXL)"))
    )
    (comp (ref "C16")
      (value "100uF 25V")
      (footprint "eagle-import:6.3X7.7(DXL)")
      (fields
        (field (name "HQ_PART") "CA0362255")
        (field (name "LCSC_PART") "C267469")
        (field (name "MANUFACTURER") "HONOR")
      )
      (libsource (lib "eagle-import") (part "100UF-25V6.3X7.7(DXL)"))
    )
    (comp (ref "C21")
      (value "2.2uF 50V")
      (footprint "eagle-import:0603")
      (fields
        (field (name "HQ_PART") "CA0174463")
        (field (name "LCSC_PART") "C913904")
        (field (name "MANUFACTURER") "FH")
      )
      (libsource (lib "eagle-import") (part "2.2UF-50V0603"))
    )
    (comp (ref "C22")
      (value "220nF 50V")
      (footprint "eagle-import:0805")
      (fields
        (field (name "HQ_PART") "CA0174157")
        (field (name "LCSC_PART") "C5378")
        (field (name "MANUFACTURER") "FH")
      )
      (libsource (lib "eagle-import") (part "220NF-50V0805"))
    )
    (comp (ref "C23")
      (value "100uF 50V")
      (footprint "eagle-import:6.3X7.7(DXL)")
      (fields
        (field (name "HQ_PART") "ZHLM0353527")
        (field (name "LCSC_PART") "C3151829")
        (field (name "MANUFACTURER") "ROQANG")
      )
      (libsource (lib "eagle-import") (part "100UF-50V6.3X7.7(DXL)"))
    )
    (comp (ref "C35")
      (value "2.2uF 400V")
      (footprint "eagle-import:6.3X7.7(DXL)")
      (fields (field (name "LCSC_PART") "C3345109"))
      (libsource (lib "eagle-import") (part "2.2UF-400V6.3X7.7(DXL)"))
    )
    (comp (ref "C45")
      (value "1uF 50V")
      (footprint "eagle-import:0805")
      (fields
        (field (name "HQ_PART") "CA0182352")
        (field (name "LCSC_PART") "C28323")
        (field (name "MANUFACTURER") "TDK")
      )
      (libsource (lib "eagle-import") (part "1UF-50V0805"))
    )
    (comp (ref "C46")
      (value "2.2uF 50V")
      (footprint "eagle-import:0603")
      (fields
        (field (name "HQ_PART") "CA0174463")
        (field (name "LCSC_PART") "C913904")
        (field (name "MANUFACTURER") "FH")
      )
      (libsource (lib "eagle-import") (part "2.2UF-50V0603"))
    )
    (comp (ref "C47")
      (value "2.2uF 400V")
      (footprint "eagle-import:6.3X7.7(DXL)")
      (fields (field (name "LCSC_PART") "C3345109"))
      (libsource (lib "eagle-import") (part "2.2UF-400V6.3X7.7(DXL)"))
    )
    (comp (ref "C51")
      (value "1nF 50V")
      (footprint "eagle-import:0603")
      (fields
        (field (name "HQ_PART") "CA0481650")
        (field (name "LCSC_PART") "C1588")
        (field (name "MANUFACTURER") "TDK")
      )
      (libsource (lib "eagle-import") (part "1NF-50V-0603"))
    )
    (comp (ref "C52")
      (value "220nF 50V")
      (footprint "eagle-import:0805")
      (fields
        (field (name "HQ_PART") "CA0174157")
        (field (name "LCSC_PART") "C5378")
        (field (name "MANUFACTURER") "FH")
      )
      (libsource (lib "eagle-import") (part "220NF-50V0805"))
    )
    (comp (ref "C53")
      (value "100uF 50V")
      (footprint "eagle-import:6.3X7.7(DXL)")
      (fields
        (field (name "HQ_PART") "ZHLM0353527")
        (field (name "LCSC_PART") "C3151829")
        (field (name "MANUFACTURER") "ROQANG")
      )
      (libsource (lib "eagle-import") (part "100UF-50V6.3X7.7(DXL)"))
    )
    (comp (ref "C57")
      (value "1uF 50V")
      (footprint "eagle-import:0805")
      (fields
        (field (name "HQ_PART") "CA0182352")
        (field (name "LCSC_PART") "C28323")
        (field (name "MANUFACTURER") "TDK")
      )
      (libsource (lib "eagle-import") (part "1UF-50V0805"))
    )
    (comp (ref "D9")
      (value "1N4007")
      (footprint "eagle-import:SMA_DO-214AC")
      (fields
        (field (name "HQ_PART") "UN0002522")
        (field (name "LCSC_PART") "C727081")
        (field (name "MANUFACTURER") "SK")
      )
      (libsource (lib "eagle-import") (part "1N4007"))
    )
    (comp (ref "D10")
      (value "1N4007")
      (footprint "eagle-import:SMA_DO-214AC")
      (fields
        (field (name "HQ_PART") "UN0002522")
        (field (name "LCSC_PART") "C727081")
        (field (name "MANUFACTURER") "SK")
      )
      (libsource (lib "eagle-import") (part "1N4007"))
    )
    (comp (ref "D11")
      (value "US1J-E3/61T")
      (footprint "eagle-import:SMA_DO-214AC")
      (fields
        (field (name "HQ_PART") "DS0007395")
        (field (name "LCSC_PART") "C44763")
        (field (name "MANUFACTURER") "Vishay")
      )
      (libsource (lib "eagle-import") (part "US1J-E3/61T"))
    )
    (comp (ref "D12")
      (value "1N4007")
      (footprint "eagle-import:SMA_DO-214AC")
      (fields
        (field (name "HQ_PART") "UN0002522")
        (field (name "LCSC_PART") "C727081")
        (field (name "MANUFACTURER") "SK")
      )
      (libsource (lib "eagle-import") (part "1N4007"))
    )
    (comp (ref "D13")
      (value "1N4007")
      (footprint "eagle-import:SMA_DO-214AC")
      (fields
        (field (name "HQ_PART") "UN0002522")
        (field (name "LCSC_PART") "C727081")
        (field (name "MANUFACTURER") "SK")
      )
      (libsource (lib "eagle-import") (part "1N4007"))
    )
    (comp (ref "D14")
      (value "US1J-E3/61T")
      (footprint "eagle-import:SMA_DO-214AC")
      (fields
        (field (name "HQ_PART") "DS0007395")
        (field (name "LCSC_PART") "C44763")
        (field (name "MANUFACTURER") "Vishay")
      )
      (libsource (lib "eagle-import") (part "US1J-E3/61T"))
    )
    (comp (ref "D16")
      (value "SMAJ15A")
      (footprint "eagle-import:SMA_DO-214AC")
      (fields
        (field (name "HQ_PART") "PD0003270")
        (field (name "LCSC_PART") "C23424")
        (field (name "MANUFACTURER") "TWGMC")
      )
      (libsource (lib "eagle-import") (part "SMAJ15A"))
    )
    (comp (ref "FB1")
      (value "DNI")
      (footprint "eagle-import:TP-ROUND")
      (libsource (lib "eagle-import") (part "TP-ROUND"))
    )
    (comp (ref "FB2")
      (value "DNI")
      (footprint "eagle-import:TP-ROUND")
      (libsource (lib "eagle-import") (part "TP-ROUND"))
    )
    (comp (ref "IC5")
      (value "MP150GJ")
      (footprint "eagle-import:SOT23-5")
      (fields
        (field (name "HQ_PART") "IC0001313")
        (field (name "MANUFACTURER") "MONOLITHIC POWER SYSTEMS ")
        (field (name "MPN") "MP150GJ-Z")
      )
      (libsource (lib "eagle-import") (part "MP150GJ"))
    )
    (comp (ref "IC13")
      (value "MP150GJ")
      (footprint "eagle-import:SOT23-5")
      (fields
        (field (name "HQ_PART") "IC0001313")
        (field (name "MANUFACTURER") "MONOLITHIC POWER SYSTEMS ")
        (field (name "MPN") "MP150GJ-Z")
      )
      (libsource (lib "eagle-import") (part "MP150GJ"))
    )
    (comp (ref "J2") (value "DNI") (footprint "eagle-import:SJ") (libsource (lib "eagle-import") (part "SJ")))
    (comp (ref "J7") (value "DNI") (footprint "eagle-import:SJ") (libsource (lib "eagle-import") (part "SJ")))
    (comp (ref "J8")
      (value "0R 1%")
      (footprint "eagle-import:0805")
      (fields
        (field (name "HQ_PART") "RE0013023")
        (field (name "LCSC_PART") "C17477")
        (field (name "MANUFACTURER") "Vishay")
      )
      (libsource (lib "eagle-import") (part "0R0805"))
    )
    (comp (ref "J9")
      (value "0R 1%")
      (footprint "eagle-import:0805")
      (fields
        (field (name "HQ_PART") "RE0013023")
        (field (name "LCSC_PART") "C17477")
        (field (name "MANUFACTURER") "Vishay")
      )
      (libsource (lib "eagle-import") (part "0R0805"))
    )
    (comp (ref "J10")
      (value "0R 1%")
      (footprint "eagle-import:0805")
      (fields
        (field (name "HQ_PART") "RE0013023")
        (field (name "LCSC_PART") "C17477")
        (field (name "MANUFACTURER") "Vishay")
      )
      (libsource (lib "eagle-import") (part "0R0805"))
    )
    (comp (ref "L-REC1")
      (value "DNI")
      (footprint "eagle-import:TP-ROUND")
      (libsource (lib "eagle-import") (part "TP-ROUND"))
    )
    (comp (ref "L-REC2")
      (value "DNI")
      (footprint "eagle-import:TP-ROUND")
      (libsource (lib "eagle-import") (part "TP-ROUND"))
    )
    (comp (ref "L3")
      (value "1mH")
      (footprint "eagle-import:L-6.6X6.6")
      (fields
        (field (name "HQ_PART") "IN0035691")
        (field (name "LCSC_PART") "C168049")
        (field (name "MANUFACTURER") "SXN")
      )
      (libsource (lib "eagle-import") (part "1MHL-6.6X6.6"))
    )
    (comp (ref "L5")
      (value "1mH")
      (footprint "eagle-import:L-6.6X6.6")
      (fields
        (field (name "HQ_PART") "IN0035691")
        (field (name "LCSC_PART") "C168049")
        (field (name "MANUFACTURER") "SXN")
      )
      (libsource (lib "eagle-import") (part "1MHL-6.6X6.6"))
    )
    (comp (ref "P12ON")
      (value "Green")
      (footprint "eagle-import:LED-0603")
      (fields
        (field (name "HQ_PART") "PH0010430")
        (field (name "LCSC_PART") "C965804")
        (field (name "MANUFACTURER") "Wurth")
      )
      (libsource (lib "eagle-import") (part "LED-GREENLED-0603"))
    )
    (comp (ref "R60")
      (value "4.99K 1%")
      (footprint "eagle-import:0603")
      (fields
        (field (name "HQ_PART") "RE0204816")
        (field (name "LCSC_PART") "C23046")
        (field (name "MANUFACTURER") "Yageo")
      )
      (libsource (lib "eagle-import") (part "4.99K-1%0603"))
    )
    (comp (ref "R61")
      (value "4.99K 1%")
      (footprint "eagle-import:0603")
      (fields
        (field (name "HQ_PART") "RE0204816")
        (field (name "LCSC_PART") "C23046")
        (field (name "MANUFACTURER") "Yageo")
      )
      (libsource (lib "eagle-import") (part "4.99K-1%0603"))
    )
    (comp (ref "R62")
      (value "39R 1% 2W")
      (footprint "eagle-import:2512")
      (fields
        (field (name "HQ_PART") "RE0461666")
        (field (name "LCSC_PART") "C175263")
        (field (name "MANUFACTURER") "Yageo")
      )
      (libsource (lib "eagle-import") (part "39R-1%2512"))
    )
    (comp (ref "R94")
      (value "100K 1%")
      (footprint "eagle-import:0402")
      (fields
        (field (name "HQ_PART") "RE0203322")
        (field (name "LCSC_PART") "C25741")
        (field (name "MANUFACTURER") "FH")
      )
      (libsource (lib "eagle-import") (part "100K-1%0402"))
    )
    (comp (ref "R95")
      (value "10K 1%")
      (footprint "eagle-import:0402")
      (fields
        (field (name "HQ_PART") "RE0207399")
        (field (name "LCSC_PART") "C25744")
        (field (name "MANUFACTURER") "ROHM")
      )
      (libsource (lib "eagle-import") (part "10K-1%0402"))
    )
    (comp (ref "R96")
      (value "10K 1%")
      (footprint "eagle-import:0805")
      (fields
        (field (name "HQ_PART") "RE0207376")
        (field (name "LCSC_PART") "C17414")
        (field (name "MANUFACTURER") "RALEC")
      )
      (libsource (lib "eagle-import") (part "10K-1%0805"))
    )
    (comp (ref "R105")
      (value "4.99K 1%")
      (footprint "eagle-import:0603")
      (fields
        (field (name "HQ_PART") "RE0204816")
        (field (name "LCSC_PART") "C23046")
        (field (name "MANUFACTURER") "Yageo")
      )
      (libsource (lib "eagle-import") (part "4.99K-1%0603"))
    )
    (comp (ref "R106")
      (value "39R 1% 2W")
      (footprint "eagle-import:2512")
      (fields
        (field (name "HQ_PART") "RE0461666")
        (field (name "LCSC_PART") "C175263")
        (field (name "MANUFACTURER") "Yageo")
      )
      (libsource (lib "eagle-import") (part "39R-1%2512"))
    )
    (comp (ref "R107")
      (value "4.99K 1%")
      (footprint "eagle-import:0603")
      (fields
        (field (name "HQ_PART") "RE0204816")
        (field (name "LCSC_PART") "C23046")
        (field (name "MANUFACTURER") "Yageo")
      )
      (libsource (lib "eagle-import") (part "4.99K-1%0603"))
    )
    (comp (ref "R108")
      (value "10K 1%")
      (footprint "eagle-import:0805")
      (fields
        (field (name "HQ_PART") "RE0207376")
        (field (name "LCSC_PART") "C17414")
        (field (name "MANUFACTURER") "RALEC")
      )
      (libsource (lib "eagle-import") (part "10K-1%0805"))
    )
    (comp (ref "R150")
      (value "8.2K 1%")
      (footprint "eagle-import:0402")
      (fields
        (field (name "HQ_PART") "RE0209227")
        (field (name "LCSC_PART") "C25924")
        (field (name "MANUFACTURER") "FH")
      )
      (libsource (lib "eagle-import") (part "8.2K-1%0402"))
    )
    (comp (ref "VCC")
      (value "DNI")
      (footprint "eagle-import:TP-ROUND")
      (libsource (lib "eagle-import") (part "TP-ROUND"))
    )
    (comp (ref "VCC2")
      (value "DNI")
      (footprint "eagle-import:TP-ROUND")
      (libsource (lib "eagle-import") (part "TP-ROUND"))
    )
    (comp (ref "C24")
      (value "33nF 50V")
      (footprint "eagle-import:0805")
      (fields
        (field (name "HQ_PART") "UN0000063")
        (field (name "LCSC_PART") "C107150")
        (field (name "MANUFACTURER") "FH")
      )
      (libsource (lib "eagle-import") (part "33NF-50V0805"))
    )
    (comp (ref "C25")
      (value "33nF 50V")
      (footprint "eagle-import:0805")
      (fields
        (field (name "HQ_PART") "UN0000063")
        (field (name "LCSC_PART") "C107150")
        (field (name "MANUFACTURER") "FH")
      )
      (libsource (lib "eagle-import") (part "33NF-50V0805"))
    )
    (comp (ref "C26")
      (value "33nF 50V")
      (footprint "eagle-import:0805")
      (fields
        (field (name "HQ_PART") "UN0000063")
        (field (name "LCSC_PART") "C107150")
        (field (name "MANUFACTURER") "FH")
      )
      (libsource (lib "eagle-import") (part "33NF-50V0805"))
    )
    (comp (ref "C30")
      (value "33nF 50V")
      (footprint "eagle-import:0805")
      (fields
        (field (name "HQ_PART") "UN0000063")
        (field (name "LCSC_PART") "C107150")
        (field (name "MANUFACTURER") "FH")
      )
      (libsource (lib "eagle-import") (part "33NF-50V0805"))
    )
    (comp (ref "C31")
      (value "33nF 50V")
      (footprint "eagle-import:0805")
      (fields
        (field (name "HQ_PART") "UN0000063")
        (field (name "LCSC_PART") "C107150")
        (field (name "MANUFACTURER") "FH")
      )
      (libsource (lib "eagle-import") (part "33NF-50V0805"))
    )
    (comp (ref "C32")
      (value "33nF 50V")
      (footprint "eagle-import:0805")
      (fields
        (field (name "HQ_PART") "UN0000063")
        (field (name "LCSC_PART") "C107150")
        (field (name "MANUFACTURER") "FH")
      )
      (libsource (lib "eagle-import") (part "33NF-50V0805"))
    )
    (comp (ref "C36")
      (value "33nF 50V")
      (footprint "eagle-import:0805")
      (fields
        (field (name "HQ_PART") "UN0000063")
        (field (name "LCSC_PART") "C107150")
        (field (name "MANUFACTURER") "FH")
      )
      (libsource (lib "eagle-import") (part "33NF-50V0805"))
    )
    (comp (ref "C37")
      (value "33nF 50V")
      (footprint "eagle-import:0805")
      (fields
        (field (name "HQ_PART") "UN0000063")
        (field (name "LCSC_PART") "C107150")
        (field (name "MANUFACTURER") "FH")
      )
      (libsource (lib "eagle-import") (part "33NF-50V0805"))
    )
    (comp (ref "C38")
      (value "33nF 50V")
      (footprint "eagle-import:0805")
      (fields
        (field (name "HQ_PART") "UN0000063")
        (field (name "LCSC_PART") "C107150")
        (field (name "MANUFACTURER") "FH")
      )
      (libsource (lib "eagle-import") (part "33NF-50V0805"))
    )
    (comp (ref "C42")
      (value "33nF 50V")
      (footprint "eagle-import:0805")
      (fields
        (field (name "HQ_PART") "UN0000063")
        (field (name "LCSC_PART") "C107150")
        (field (name "MANUFACTURER") "FH")
      )
      (libsource (lib "eagle-import") (part "33NF-50V0805"))
    )
    (comp (ref "C43")
      (value "33nF 50V")
      (footprint "eagle-import:0805")
      (fields
        (field (name "HQ_PART") "UN0000063")
        (field (name "LCSC_PART") "C107150")
        (field (name "MANUFACTURER") "FH")
      )
      (libsource (lib "eagle-import") (part "33NF-50V0805"))
    )
    (comp (ref "C44")
      (value "33nF 50V")
      (footprint "eagle-import:0805")
      (fields
        (field (name "HQ_PART") "UN0000063")
        (field (name "LCSC_PART") "C107150")
        (field (name "MANUFACTURER") "FH")
      )
      (libsource (lib "eagle-import") (part "33NF-50V0805"))
    )
    (comp (ref "IC6")
      (value "HLW8032")
      (footprint "eagle-import:SO8")
      (fields
        (field (name "HQ_PART") "MD0751024")
        (field (name "LCSC_PART") "C128023")
        (field (name "MANUFACTURER") "Hiliwei Tech")
      )
      (libsource (lib "eagle-import") (part "HLW8032"))
    )
    (comp (ref "IC8")
      (value "HLW8032")
      (footprint "eagle-import:SO8")
      (fields
        (field (name "HQ_PART") "MD0751024")
        (field (name "LCSC_PART") "C128023")
        (field (name "MANUFACTURER") "Hiliwei Tech")
      )
      (libsource (lib "eagle-import") (part "HLW8032"))
    )
    (comp (ref "IC10")
      (value "HLW8032")
      (footprint "eagle-import:SO8")
      (fields
        (field (name "HQ_PART") "MD0751024")
        (field (name "LCSC_PART") "C128023")
        (field (name "MANUFACTURER") "Hiliwei Tech")
      )
      (libsource (lib "eagle-import") (part "HLW8032"))
    )
    (comp (ref "IC12")
      (value "HLW8032")
      (footprint "eagle-import:SO8")
      (fields
        (field (name "HQ_PART") "MD0751024")
        (field (name "LCSC_PART") "C128023")
        (field (name "MANUFACTURER") "Hiliwei Tech")
      )
      (libsource (lib "eagle-import") (part "HLW8032"))
    )
    (comp (ref "L_OUT1")
      (value "FASTON-1217861-1")
      (footprint "eagle-import:1217861-1")
      (fields
        (field (name "LCSC_PART") "C428480")
        (field (name "MANUFACTURER") "TE CONNECTIVITY")
        (field (name "MPN") "1217861-1")
      )
      (libsource (lib "eagle-import") (part "FASTON-1217861-1"))
    )
    (comp (ref "L_OUT2")
      (value "FASTON-1217861-1")
      (footprint "eagle-import:1217861-1")
      (fields
        (field (name "LCSC_PART") "C428480")
        (field (name "MANUFACTURER") "TE CONNECTIVITY")
        (field (name "MPN") "1217861-1")
      )
      (libsource (lib "eagle-import") (part "FASTON-1217861-1"))
    )
    (comp (ref "L_OUT3")
      (value "FASTON-1217861-1")
      (footprint "eagle-import:1217861-1")
      (fields
        (field (name "LCSC_PART") "C428480")
        (field (name "MANUFACTURER") "TE CONNECTIVITY")
        (field (name "MPN") "1217861-1")
      )
      (libsource (lib "eagle-import") (part "FASTON-1217861-1"))
    )
    (comp (ref "L_OUT4")
      (value "FASTON-1217861-1")
      (footprint "eagle-import:1217861-1")
      (fields
        (field (name "LCSC_PART") "C428480")
        (field (name "MANUFACTURER") "TE CONNECTIVITY")
        (field (name "MPN") "1217861-1")
      )
      (libsource (lib "eagle-import") (part "FASTON-1217861-1"))
    )
    (comp (ref "N_OUT1")
      (value "FASTON-1217861-1")
      (footprint "eagle-import:1217861-1")
      (fields
        (field (name "LCSC_PART") "C428480")
        (field (name "MANUFACTURER") "TE CONNECTIVITY")
        (field (name "MPN") "1217861-1")
      )
      (libsource (lib "eagle-import") (part "FASTON-1217861-1"))
    )
    (comp (ref "N_OUT2")
      (value "FASTON-1217861-1")
      (footprint "eagle-import:1217861-1")
      (fields
        (field (name "LCSC_PART") "C428480")
        (field (name "MANUFACTURER") "TE CONNECTIVITY")
        (field (name "MPN") "1217861-1")
      )
      (libsource (lib "eagle-import") (part "FASTON-1217861-1"))
    )
    (comp (ref "N_OUT3")
      (value "FASTON-1217861-1")
      (footprint "eagle-import:1217861-1")
      (fields
        (field (name "LCSC_PART") "C428480")
        (field (name "MANUFACTURER") "TE CONNECTIVITY")
        (field (name "MPN") "1217861-1")
      )
      (libsource (lib "eagle-import") (part "FASTON-1217861-1"))
    )
    (comp (ref "N_OUT4")
      (value "FASTON-1217861-1")
      (footprint "eagle-import:1217861-1")
      (fields
        (field (name "LCSC_PART") "C428480")
        (field (name "MANUFACTURER") "TE CONNECTIVITY")
        (field (name "MPN") "1217861-1")
      )
      (libsource (lib "eagle-import") (part "FASTON-1217861-1"))
    )
    (comp (ref "R25")
      (value "0.002R 1%")
      (footprint "eagle-import:2512")
      (fields
        (field (name "HQ_PART") "RE0716514")
        (field (name "LCSC_PART") "C728320")
        (field (name "MANUFACTURER") "Viking")
      )
      (libsource (lib "eagle-import") (part "0.002R-1%2512"))
    )
    (comp (ref "R30")
      (value "0.002R 1%")
      (footprint "eagle-import:2512")
      (fields
        (field (name "HQ_PART") "RE0716514")
        (field (name "LCSC_PART") "C728320")
        (field (name "MANUFACTURER") "Viking")
      )
      (libsource (lib "eagle-import") (part "0.002R-1%2512"))
    )
    (comp (ref "R31")
      (value "0.002R 1%")
      (footprint "eagle-import:2512")
      (fields
        (field (name "HQ_PART") "RE0716514")
        (field (name "LCSC_PART") "C728320")
        (field (name "MANUFACTURER") "Viking")
      )
      (libsource (lib "eagle-import") (part "0.002R-1%2512"))
    )
    (comp (ref "R32")
      (value "0.002R 1%")
      (footprint "eagle-import:2512")
      (fields
        (field (name "HQ_PART") "RE0716514")
        (field (name "LCSC_PART") "C728320")
        (field (name "MANUFACTURER") "Viking")
      )
      (libsource (lib "eagle-import") (part "0.002R-1%2512"))
    )
    (comp (ref "R33")
      (value "1K 1%")
      (footprint "eagle-import:0805")
      (fields
        (field (name "HQ_PART") "RE0203459")
        (field (name "LCSC_PART") "C17513")
        (field (name "MANUFACTURER") "FH")
      )
      (libsource (lib "eagle-import") (part "1K-1%0805"))
    )
    (comp (ref "R34")
      (value "1K 1%")
      (footprint "eagle-import:0805")
      (fields
        (field (name "HQ_PART") "RE0203459")
        (field (name "LCSC_PART") "C17513")
        (field (name "MANUFACTURER") "FH")
      )
      (libsource (lib "eagle-import") (part "1K-1%0805"))
    )
    (comp (ref "R35")
      (value "0.002R 1%")
      (footprint "eagle-import:2512")
      (fields
        (field (name "HQ_PART") "RE0716514")
        (field (name "LCSC_PART") "C728320")
        (field (name "MANUFACTURER") "Viking")
      )
      (libsource (lib "eagle-import") (part "0.002R-1%2512"))
    )
    (comp (ref "R36")
      (value "470K 1%")
      (footprint "eagle-import:0805")
      (fields
        (field (name "HQ_PART") "RE0205756")
        (field (name "LCSC_PART") "C17709")
        (field (name "MANUFACTURER") "Panasonic")
      )
      (libsource (lib "eagle-import") (part "470K-1%0805"))
    )
    (comp (ref "R37")
      (value "470K 1%")
      (footprint "eagle-import:0805")
      (fields
        (field (name "HQ_PART") "RE0205756")
        (field (name "LCSC_PART") "C17709")
        (field (name "MANUFACTURER") "Panasonic")
      )
      (libsource (lib "eagle-import") (part "470K-1%0805"))
    )
    (comp (ref "R38")
      (value "470K 1%")
      (footprint "eagle-import:0805")
      (fields
        (field (name "HQ_PART") "RE0205756")
        (field (name "LCSC_PART") "C17709")
        (field (name "MANUFACTURER") "Panasonic")
      )
      (libsource (lib "eagle-import") (part "470K-1%0805"))
    )
    (comp (ref "R39")
      (value "470K 1%")
      (footprint "eagle-import:0805")
      (fields
        (field (name "HQ_PART") "RE0205756")
        (field (name "LCSC_PART") "C17709")
        (field (name "MANUFACTURER") "Panasonic")
      )
      (libsource (lib "eagle-import") (part "470K-1%0805"))
    )
    (comp (ref "R40")
      (value "1K 1%")
      (footprint "eagle-import:0805")
      (fields
        (field (name "HQ_PART") "RE0203459")
        (field (name "LCSC_PART") "C17513")
        (field (name "MANUFACTURER") "FH")
      )
      (libsource (lib "eagle-import") (part "1K-1%0805"))
    )
    (comp (ref "R49")
      (value "1K 1%")
      (footprint "eagle-import:0805")
      (fields
        (field (name "HQ_PART") "RE0203459")
        (field (name "LCSC_PART") "C17513")
        (field (name "MANUFACTURER") "FH")
      )
      (libsource (lib "eagle-import") (part "1K-1%0805"))
    )
    (comp (ref "R50")
      (value "1K 1%")
      (footprint "eagle-import:0805")
      (fields
        (field (name "HQ_PART") "RE0203459")
        (field (name "LCSC_PART") "C17513")
        (field (name "MANUFACTURER") "FH")
      )
      (libsource (lib "eagle-import") (part "1K-1%0805"))
    )
    (comp (ref "R51")
      (value "0.002R 1%")
      (footprint "eagle-import:2512")
      (fields
        (field (name "HQ_PART") "RE0716514")
        (field (name "LCSC_PART") "C728320")
        (field (name "MANUFACTURER") "Viking")
      )
      (libsource (lib "eagle-import") (part "0.002R-1%2512"))
    )
    (comp (ref "R52")
      (value "470K 1%")
      (footprint "eagle-import:0805")
      (fields
        (field (name "HQ_PART") "RE0205756")
        (field (name "LCSC_PART") "C17709")
        (field (name "MANUFACTURER") "Panasonic")
      )
      (libsource (lib "eagle-import") (part "470K-1%0805"))
    )
    (comp (ref "R53")
      (value "470K 1%")
      (footprint "eagle-import:0805")
      (fields
        (field (name "HQ_PART") "RE0205756")
        (field (name "LCSC_PART") "C17709")
        (field (name "MANUFACTURER") "Panasonic")
      )
      (libsource (lib "eagle-import") (part "470K-1%0805"))
    )
    (comp (ref "R54")
      (value "470K 1%")
      (footprint "eagle-import:0805")
      (fields
        (field (name "HQ_PART") "RE0205756")
        (field (name "LCSC_PART") "C17709")
        (field (name "MANUFACTURER") "Panasonic")
      )
      (libsource (lib "eagle-import") (part "470K-1%0805"))
    )
    (comp (ref "R55")
      (value "470K 1%")
      (footprint "eagle-import:0805")
      (fields
        (field (name "HQ_PART") "RE0205756")
        (field (name "LCSC_PART") "C17709")
        (field (name "MANUFACTURER") "Panasonic")
      )
      (libsource (lib "eagle-import") (part "470K-1%0805"))
    )
    (comp (ref "R56")
      (value "1K 1%")
      (footprint "eagle-import:0805")
      (fields
        (field (name "HQ_PART") "RE0203459")
        (field (name "LCSC_PART") "C17513")
        (field (name "MANUFACTURER") "FH")
      )
      (libsource (lib "eagle-import") (part "1K-1%0805"))
    )
    (comp (ref "R65")
      (value "1K 1%")
      (footprint "eagle-import:0805")
      (fields
        (field (name "HQ_PART") "RE0203459")
        (field (name "LCSC_PART") "C17513")
        (field (name "MANUFACTURER") "FH")
      )
      (libsource (lib "eagle-import") (part "1K-1%0805"))
    )
    (comp (ref "R66")
      (value "1K 1%")
      (footprint "eagle-import:0805")
      (fields
        (field (name "HQ_PART") "RE0203459")
        (field (name "LCSC_PART") "C17513")
        (field (name "MANUFACTURER") "FH")
      )
      (libsource (lib "eagle-import") (part "1K-1%0805"))
    )
    (comp (ref "R67")
      (value "0.002R 1%")
      (footprint "eagle-import:2512")
      (fields
        (field (name "HQ_PART") "RE0716514")
        (field (name "LCSC_PART") "C728320")
        (field (name "MANUFACTURER") "Viking")
      )
      (libsource (lib "eagle-import") (part "0.002R-1%2512"))
    )
    (comp (ref "R68")
      (value "470K 1%")
      (footprint "eagle-import:0805")
      (fields
        (field (name "HQ_PART") "RE0205756")
        (field (name "LCSC_PART") "C17709")
        (field (name "MANUFACTURER") "Panasonic")
      )
      (libsource (lib "eagle-import") (part "470K-1%0805"))
    )
    (comp (ref "R69")
      (value "470K 1%")
      (footprint "eagle-import:0805")
      (fields
        (field (name "HQ_PART") "RE0205756")
        (field (name "LCSC_PART") "C17709")
        (field (name "MANUFACTURER") "Panasonic")
      )
      (libsource (lib "eagle-import") (part "470K-1%0805"))
    )
    (comp (ref "R70")
      (value "470K 1%")
      (footprint "eagle-import:0805")
      (fields
        (field (name "HQ_PART") "RE0205756")
        (field (name "LCSC_PART") "C17709")
        (field (name "MANUFACTURER") "Panasonic")
      )
      (libsource (lib "eagle-import") (part "470K-1%0805"))
    )
    (comp (ref "R71")
      (value "470K 1%")
      (footprint "eagle-import:0805")
      (fields
        (field (name "HQ_PART") "RE0205756")
        (field (name "LCSC_PART") "C17709")
        (field (name "MANUFACTURER") "Panasonic")
      )
      (libsource (lib "eagle-import") (part "470K-1%0805"))
    )
    (comp (ref "R72")
      (value "1K 1%")
      (footprint "eagle-import:0805")
      (fields
        (field (name "HQ_PART") "RE0203459")
        (field (name "LCSC_PART") "C17513")
        (field (name "MANUFACTURER") "FH")
      )
      (libsource (lib "eagle-import") (part "1K-1%0805"))
    )
    (comp (ref "R81")
      (value "1K 1%")
      (footprint "eagle-import:0805")
      (fields
        (field (name "HQ_PART") "RE0203459")
        (field (name "LCSC_PART") "C17513")
        (field (name "MANUFACTURER") "FH")
      )
      (libsource (lib "eagle-import") (part "1K-1%0805"))
    )
    (comp (ref "R82")
      (value "1K 1%")
      (footprint "eagle-import:0805")
      (fields
        (field (name "HQ_PART") "RE0203459")
        (field (name "LCSC_PART") "C17513")
        (field (name "MANUFACTURER") "FH")
      )
      (libsource (lib "eagle-import") (part "1K-1%0805"))
    )
    (comp (ref "R83")
      (value "0.002R 1%")
      (footprint "eagle-import:2512")
      (fields
        (field (name "HQ_PART") "RE0716514")
        (field (name "LCSC_PART") "C728320")
        (field (name "MANUFACTURER") "Viking")
      )
      (libsource (lib "eagle-import") (part "0.002R-1%2512"))
    )
    (comp (ref "R84")
      (value "470K 1%")
      (footprint "eagle-import:0805")
      (fields
        (field (name "HQ_PART") "RE0205756")
        (field (name "LCSC_PART") "C17709")
        (field (name "MANUFACTURER") "Panasonic")
      )
      (libsource (lib "eagle-import") (part "470K-1%0805"))
    )
    (comp (ref "R85")
      (value "470K 1%")
      (footprint "eagle-import:0805")
      (fields
        (field (name "HQ_PART") "RE0205756")
        (field (name "LCSC_PART") "C17709")
        (field (name "MANUFACTURER") "Panasonic")
      )
      (libsource (lib "eagle-import") (part "470K-1%0805"))
    )
    (comp (ref "R86")
      (value "470K 1%")
      (footprint "eagle-import:0805")
      (fields
        (field (name "HQ_PART") "RE0205756")
        (field (name "LCSC_PART") "C17709")
        (field (name "MANUFACTURER") "Panasonic")
      )
      (libsource (lib "eagle-import") (part "470K-1%0805"))
    )
    (comp (ref "R87")
      (value "470K 1%")
      (footprint "eagle-import:0805")
      (fields
        (field (name "HQ_PART") "RE0205756")
        (field (name "LCSC_PART") "C17709")
        (field (name "MANUFACTURER") "Panasonic")
      )
      (libsource (lib "eagle-import") (part "470K-1%0805"))
    )
    (comp (ref "R88")
      (value "1K 1%")
      (footprint "eagle-import:0805")
      (fields
        (field (name "HQ_PART") "RE0203459")
        (field (name "LCSC_PART") "C17513")
        (field (name "MANUFACTURER") "FH")
      )
      (libsource (lib "eagle-import") (part "1K-1%0805"))
    )
    (comp (ref "3V3A")
      (value "DNI")
      (footprint "eagle-import:TP-ROUND")
      (libsource (lib "eagle-import") (part "TP-ROUND"))
    )
    (comp (ref "C79")
      (value "100nF 25V")
      (footprint "eagle-import:0402")
      (fields
        (field (name "HQ_PART") "CA0176807")
        (field (name "LCSC_PART") "C56392")
        (field (name "MANUFACTURER") "Walsin")
      )
      (libsource (lib "eagle-import") (part "100NF-25V-0402"))
    )
    (comp (ref "C80")
      (value "22nF 50V")
      (footprint "eagle-import:0402")
      (fields
        (field (name "HQ_PART") "CA0171190")
        (field (name "LCSC_PART") "C1532")
        (field (name "MANUFACTURER") "Samsung")
      )
      (libsource (lib "eagle-import") (part "22NF-50V0402"))
    )
    (comp (ref "C81")
      (value "6.8nF 50V")
      (footprint "eagle-import:0201")
      (fields
        (field (name "HQ_PART") "CA0363038")
        (field (name "LCSC_PART") "C285015")
        (field (name "MANUFACTURER") "FH")
      )
      (libsource (lib "eagle-import") (part "6.8NF-50V0201"))
    )
    (comp (ref "C82")
      (value "6.8nF 50V")
      (footprint "eagle-import:0201")
      (fields
        (field (name "HQ_PART") "CA0363038")
        (field (name "LCSC_PART") "C285015")
        (field (name "MANUFACTURER") "FH")
      )
      (libsource (lib "eagle-import") (part "6.8NF-50V0201"))
    )
    (comp (ref "C83")
      (value "1nF 2kV")
      (footprint "eagle-import:1206")
      (fields
        (field (name "HQ_PART") "CA0134884")
        (field (name "LCSC_PART") "C173242")
        (field (name "MANUFACTURER") "Johanson Dielectrics ")
      )
      (libsource (lib "eagle-import") (part "1NF-2KV"))
    )
    (comp (ref "C84")
      (value "100nF 25V")
      (footprint "eagle-import:0201")
      (fields
        (field (name "HQ_PART") "CA0183221")
        (field (name "LCSC_PART") "C76939")
        (field (name "MANUFACTURER") "Samsung")
      )
      (libsource (lib "eagle-import") (part "100NF-25V-0201"))
    )
    (comp (ref "C85")
      (value "4.7uF 25V")
      (footprint "eagle-import:0402")
      (fields
        (field (name "HQ_PART") "ZHLM0023346")
        (field (name "LCSC_PART") "C22367824")
        (field (name "MANUFACTURER") "Murata")
      )
      (libsource (lib "eagle-import") (part "4.7UF-25V0402"))
    )
    (comp (ref "C86")
      (value "18pF 50V")
      (footprint "eagle-import:0201")
      (fields
        (field (name "HQ_PART") "CA0486739")
        (field (name "LCSC_PART") "C62164")
        (field (name "MANUFACTURER") "Yageo")
      )
      (libsource (lib "eagle-import") (part "18PF-50V-0201"))
    )
    (comp (ref "C87")
      (value "18pF 50V")
      (footprint "eagle-import:0201")
      (fields
        (field (name "HQ_PART") "CA0486739")
        (field (name "LCSC_PART") "C62164")
        (field (name "MANUFACTURER") "Yageo")
      )
      (libsource (lib "eagle-import") (part "18PF-50V-0201"))
    )
    (comp (ref "C88")
      (value "100nF 25V")
      (footprint "eagle-import:0201")
      (fields
        (field (name "HQ_PART") "CA0183221")
        (field (name "LCSC_PART") "C76939")
        (field (name "MANUFACTURER") "Samsung")
      )
      (libsource (lib "eagle-import") (part "100NF-25V-0201"))
    )
    (comp (ref "C89")
      (value "100nF 25V")
      (footprint "eagle-import:0201")
      (fields
        (field (name "HQ_PART") "CA0183221")
        (field (name "LCSC_PART") "C76939")
        (field (name "MANUFACTURER") "Samsung")
      )
      (libsource (lib "eagle-import") (part "100NF-25V-0201"))
    )
    (comp (ref "C90")
      (value "100nF 25V")
      (footprint "eagle-import:0201")
      (fields
        (field (name "HQ_PART") "CA0183221")
        (field (name "LCSC_PART") "C76939")
        (field (name "MANUFACTURER") "Samsung")
      )
      (libsource (lib "eagle-import") (part "100NF-25V-0201"))
    )
    (comp (ref "C91")
      (value "100nF 25V")
      (footprint "eagle-import:0201")
      (fields
        (field (name "HQ_PART") "CA0183221")
        (field (name "LCSC_PART") "C76939")
        (field (name "MANUFACTURER") "Samsung")
      )
      (libsource (lib "eagle-import") (part "100NF-25V-0201"))
    )
    (comp (ref "C92")
      (value "100nF 25V")
      (footprint "eagle-import:0201")
      (fields
        (field (name "HQ_PART") "CA0183221")
        (field (name "LCSC_PART") "C76939")
        (field (name "MANUFACTURER") "Samsung")
      )
      (libsource (lib "eagle-import") (part "100NF-25V-0201"))
    )
    (comp (ref "C93")
      (value "100nF 25V")
      (footprint "eagle-import:0201")
      (fields
        (field (name "HQ_PART") "CA0183221")
        (field (name "LCSC_PART") "C76939")
        (field (name "MANUFACTURER") "Samsung")
      )
      (libsource (lib "eagle-import") (part "100NF-25V-0201"))
    )
    (comp (ref "C94")
      (value "100nF 25V")
      (footprint "eagle-import:0201")
      (fields
        (field (name "HQ_PART") "CA0183221")
        (field (name "LCSC_PART") "C76939")
        (field (name "MANUFACTURER") "Samsung")
      )
      (libsource (lib "eagle-import") (part "100NF-25V-0201"))
    )
    (comp (ref "C95")
      (value "100nF 25V")
      (footprint "eagle-import:0201")
      (fields
        (field (name "HQ_PART") "CA0183221")
        (field (name "LCSC_PART") "C76939")
        (field (name "MANUFACTURER") "Samsung")
      )
      (libsource (lib "eagle-import") (part "100NF-25V-0201"))
    )
    (comp (ref "C96")
      (value "100nF 25V")
      (footprint "eagle-import:0201")
      (fields
        (field (name "HQ_PART") "CA0183221")
        (field (name "LCSC_PART") "C76939")
        (field (name "MANUFACTURER") "Samsung")
      )
      (libsource (lib "eagle-import") (part "100NF-25V-0201"))
    )
    (comp (ref "ETH1")
      (value "J1B1211CCD")
      (footprint "eagle-import:J1B1211CCD")
      (fields
        (field (name "HQ_PART") "UN0002907")
        (field (name "LCSC_PART") "C910371")
        (field (name "MANUFACTURER") "WIZnet")
      )
      (libsource (lib "eagle-import") (part "J1B1211CCD"))
    )
    (comp (ref "IC20")
      (value "W5500")
      (footprint "eagle-import:LQFP48")
      (fields
        (field (name "HQ_PART") "IC0084426")
        (field (name "LCSC_PART") "C32843")
        (field (name "MANUFACTURER") "WIZNET")
      )
      (libsource (lib "eagle-import") (part "W5500"))
    )
    (comp (ref "L4")
      (value "BLM18EG221TN1D")
      (footprint "eagle-import:0603")
      (fields
        (field (name "HQ_PART") "WF0012312")
        (field (name "LCSC_PART") "C113025")
        (field (name "MANUFACTURER") "Murata")
      )
      (libsource (lib "eagle-import") (part "BLM18EG221TN1D"))
    )
    (comp (ref "R110")
      (value "1M 1%")
      (footprint "eagle-import:1206")
      (fields
        (field (name "HQ_PART") "RE0188103")
        (field (name "LCSC_PART") "C17927")
        (field (name "MANUFACTURER") "Uniohm")
      )
      (libsource (lib "eagle-import") (part "1M-1%1206"))
    )
    (comp (ref "R133")
      (value "3.3R 1%")
      (footprint "eagle-import:0201")
      (fields
        (field (name "HQ_PART") "RE0422979")
        (field (name "LCSC_PART") "C158547")
        (field (name "MANUFACTURER") "Uniohm")
      )
      (libsource (lib "eagle-import") (part "3.3R-1%0201"))
    )
    (comp (ref "R134")
      (value "3.3R 1%")
      (footprint "eagle-import:0201")
      (fields
        (field (name "HQ_PART") "RE0422979")
        (field (name "LCSC_PART") "C158547")
        (field (name "MANUFACTURER") "Uniohm")
      )
      (libsource (lib "eagle-import") (part "3.3R-1%0201"))
    )
    (comp (ref "R135")
      (value "3.3R 1%")
      (footprint "eagle-import:0201")
      (fields
        (field (name "HQ_PART") "RE0422979")
        (field (name "LCSC_PART") "C158547")
        (field (name "MANUFACTURER") "Uniohm")
      )
      (libsource (lib "eagle-import") (part "3.3R-1%0201"))
    )
    (comp (ref "R136")
      (value "3.3R 1%")
      (footprint "eagle-import:0201")
      (fields
        (field (name "HQ_PART") "RE0422979")
        (field (name "LCSC_PART") "C158547")
        (field (name "MANUFACTURER") "Uniohm")
      )
      (libsource (lib "eagle-import") (part "3.3R-1%0201"))
    )
    (comp (ref "R137")
      (value "49.9R 1%")
      (footprint "eagle-import:0201")
      (fields
        (field (name "HQ_PART") "RE0721921")
        (field (name "LCSC_PART") "C155744")
        (field (name "MANUFACTURER") "FH")
      )
      (libsource (lib "eagle-import") (part "49.9R-1%0201"))
    )
    (comp (ref "R138")
      (value "49.9R 1%")
      (footprint "eagle-import:0201")
      (fields
        (field (name "HQ_PART") "RE0721921")
        (field (name "LCSC_PART") "C155744")
        (field (name "MANUFACTURER") "FH")
      )
      (libsource (lib "eagle-import") (part "49.9R-1%0201"))
    )
    (comp (ref "R139")
      (value "49.9R 1%")
      (footprint "eagle-import:0201")
      (fields
        (field (name "HQ_PART") "RE0721921")
        (field (name "LCSC_PART") "C155744")
        (field (name "MANUFACTURER") "FH")
      )
      (libsource (lib "eagle-import") (part "49.9R-1%0201"))
    )
    (comp (ref "R140")
      (value "49.9R 1%")
      (footprint "eagle-import:0201")
      (fields
        (field (name "HQ_PART") "RE0721921")
        (field (name "LCSC_PART") "C155744")
        (field (name "MANUFACTURER") "FH")
      )
      (libsource (lib "eagle-import") (part "49.9R-1%0201"))
    )
    (comp (ref "R141")
      (value "470R 1%")
      (footprint "eagle-import:0402")
      (fields
        (field (name "HQ_PART") "RE0205922")
        (field (name "LCSC_PART") "C25117")
        (field (name "MANUFACTURER") "Panasonic")
      )
      (libsource (lib "eagle-import") (part "470R-1%0402"))
    )
    (comp (ref "R142")
      (value "470R 1%")
      (footprint "eagle-import:0402")
      (fields
        (field (name "HQ_PART") "RE0205922")
        (field (name "LCSC_PART") "C25117")
        (field (name "MANUFACTURER") "Panasonic")
      )
      (libsource (lib "eagle-import") (part "470R-1%0402"))
    )
    (comp (ref "R143")
      (value "12.4K 1%")
      (footprint "eagle-import:0201")
      (fields
        (field (name "HQ_PART") "RE0186667")
        (field (name "LCSC_PART") "C423760")
        (field (name "MANUFACTURER") "Yageo")
      )
      (libsource (lib "eagle-import") (part "12.4K-1%0201"))
    )
    (comp (ref "R144")
      (value "1M 1%")
      (footprint "eagle-import:0201")
      (fields
        (field (name "HQ_PART") "RE0422946")
        (field (name "LCSC_PART") "C295786")
        (field (name "MANUFACTURER") "Yageo")
      )
      (libsource (lib "eagle-import") (part "1M-1%0201"))
    )
    (comp (ref "R145")
      (value "4.7K 1%")
      (footprint "eagle-import:0201")
      (fields
        (field (name "HQ_PART") "RE0208670")
        (field (name "LCSC_PART") "C270346")
        (field (name "MANUFACTURER") "RALEC")
      )
      (libsource (lib "eagle-import") (part "4.7K-1%0201"))
    )
    (comp (ref "R146")
      (value "470R 1%")
      (footprint "eagle-import:0402")
      (fields
        (field (name "HQ_PART") "RE0205922")
        (field (name "LCSC_PART") "C25117")
        (field (name "MANUFACTURER") "Panasonic")
      )
      (libsource (lib "eagle-import") (part "470R-1%0402"))
    )
    (comp (ref "X2")
      (value "25MHz")
      (footprint "eagle-import:WE-XTAL_CFPX-180")
      (fields
        (field (name "HQ_PART") "CR0250343")
        (field (name "LCSC_PART") "C13740")
        (field (name "MANUFACTURER") "Epson")
      )
      (libsource (lib "eagle-import") (part "CRYSTAL-3225X322525MOB4SI"))
    )
    (comp (ref "C19")
      (value "100nF 25V")
      (footprint "eagle-import:0402")
      (fields
        (field (name "HQ_PART") "CA0176807")
        (field (name "LCSC_PART") "C56392")
        (field (name "MANUFACTURER") "Walsin")
      )
      (libsource (lib "eagle-import") (part "100NF-25V-0402"))
    )
    (comp (ref "C20")
      (value "100nF 25V")
      (footprint "eagle-import:0402")
      (fields
        (field (name "HQ_PART") "CA0176807")
        (field (name "LCSC_PART") "C56392")
        (field (name "MANUFACTURER") "Walsin")
      )
      (libsource (lib "eagle-import") (part "100NF-25V-0402"))
    )
    (comp (ref "C33")
      (value "100nF 25V")
      (footprint "eagle-import:0402")
      (fields
        (field (name "HQ_PART") "CA0176807")
        (field (name "LCSC_PART") "C56392")
        (field (name "MANUFACTURER") "Walsin")
      )
      (libsource (lib "eagle-import") (part "100NF-25V-0402"))
    )
    (comp (ref "C34")
      (value "100nF 25V")
      (footprint "eagle-import:0402")
      (fields
        (field (name "HQ_PART") "CA0176807")
        (field (name "LCSC_PART") "C56392")
        (field (name "MANUFACTURER") "Walsin")
      )
      (libsource (lib "eagle-import") (part "100NF-25V-0402"))
    )
    (comp (ref "C103")
      (value "100nF 25V")
      (footprint "eagle-import:0201")
      (fields
        (field (name "HQ_PART") "CA0183221")
        (field (name "LCSC_PART") "C76939")
        (field (name "MANUFACTURER") "Samsung")
      )
      (libsource (lib "eagle-import") (part "100NF-25V-0201"))
    )
    (comp (ref "DAT")
      (value "Blue")
      (footprint "eagle-import:LED-0603")
      (fields
        (field (name "HQ_PART") "PH0093698")
        (field (name "LCSC_PART") "C965807")
        (field (name "MANUFACTURER") "NATIONSTAR")
      )
      (libsource (lib "eagle-import") (part "LED-BLUELED-0603"))
    )
    (comp (ref "IC3")
      (value "ULN2803AFWG")
      (footprint "eagle-import:SO18")
      (fields
        (field (name "HQ_PART") "ZHLM0322921")
        (field (name "LCSC_PART") "C845537")
        (field (name "MANUFACTURER") "UMW")
      )
      (libsource (lib "eagle-import") (part "ULN2803"))
    )
    (comp (ref "IC4")
      (value "MCP23017T-E/ML")
      (footprint "eagle-import:QFN28[6X6]ML")
      (fields
        (field (name "HQ_PART") "IC0080215")
        (field (name "LCSC_PART") "C629439")
        (field (name "MANUFACTURER") "MICROCHIP")
      )
      (libsource (lib "eagle-import") (part "MCP23017-E/ML"))
    )
    (comp (ref "IC9")
      (value "SN74HC151PWR")
      (footprint "eagle-import:TSSOP16")
      (fields
        (field (name "HQ_PART") "IC0244620")
        (field (name "LCSC_PART") "C2653837")
        (field (name "MANUFACTURER") "Texas Instruments")
      )
      (libsource (lib "eagle-import") (part "74AC151"))
    )
    (comp (ref "IC22")
      (value "MCP6001RT-I/OT")
      (footprint "eagle-import:SOT23-5")
      (fields
        (field (name "HQ_PART") "IC0119727")
        (field (name "LCSC_PART") "C154973")
        (field (name "MANUFACTURER") "MICROCHIP")
      )
      (libsource (lib "eagle-import") (part "MCP6001RT"))
    )
    (comp (ref "R17")
      (value "0R 1%")
      (footprint "eagle-import:2512")
      (fields
        (field (name "HQ_PART") "RE0460225")
        (field (name "LCSC_PART") "C25469")
        (field (name "MANUFACTURER") "KOA")
      )
      (libsource (lib "eagle-import") (part "0R2512"))
    )
    (comp (ref "R18")
      (value "0R 1%")
      (footprint "eagle-import:2512")
      (fields
        (field (name "HQ_PART") "RE0460225")
        (field (name "LCSC_PART") "C25469")
        (field (name "MANUFACTURER") "KOA")
      )
      (libsource (lib "eagle-import") (part "0R2512"))
    )
    (comp (ref "R19")
      (value "0R 1%")
      (footprint "eagle-import:2512")
      (fields
        (field (name "HQ_PART") "RE0460225")
        (field (name "LCSC_PART") "C25469")
        (field (name "MANUFACTURER") "KOA")
      )
      (libsource (lib "eagle-import") (part "0R2512"))
    )
    (comp (ref "R20")
      (value "0R 1%")
      (footprint "eagle-import:2512")
      (fields
        (field (name "HQ_PART") "RE0460225")
        (field (name "LCSC_PART") "C25469")
        (field (name "MANUFACTURER") "KOA")
      )
      (libsource (lib "eagle-import") (part "0R2512"))
    )
    (comp (ref "R21")
      (value "0R 1%")
      (footprint "eagle-import:2512")
      (fields
        (field (name "HQ_PART") "RE0460225")
        (field (name "LCSC_PART") "C25469")
        (field (name "MANUFACTURER") "KOA")
      )
      (libsource (lib "eagle-import") (part "0R2512"))
    )
    (comp (ref "R22")
      (value "0R 1%")
      (footprint "eagle-import:2512")
      (fields
        (field (name "HQ_PART") "RE0460225")
        (field (name "LCSC_PART") "C25469")
        (field (name "MANUFACTURER") "KOA")
      )
      (libsource (lib "eagle-import") (part "0R2512"))
    )
    (comp (ref "R23")
      (value "0R 1%")
      (footprint "eagle-import:2512")
      (fields
        (field (name "HQ_PART") "RE0460225")
        (field (name "LCSC_PART") "C25469")
        (field (name "MANUFACTURER") "KOA")
      )
      (libsource (lib "eagle-import") (part "0R2512"))
    )
    (comp (ref "R24")
      (value "0R 1%")
      (footprint "eagle-import:2512")
      (fields
        (field (name "HQ_PART") "RE0460225")
        (field (name "LCSC_PART") "C25469")
        (field (name "MANUFACTURER") "KOA")
      )
      (libsource (lib "eagle-import") (part "0R2512"))
    )
    (comp (ref "R57")
      (value "0R 1%")
      (footprint "eagle-import:0402")
      (fields
        (field (name "HQ_PART") "RE0250181")
        (field (name "LCSC_PART") "C17168")
        (field (name "MANUFACTURER") "YAGEO")
      )
      (libsource (lib "eagle-import") (part "0R0402"))
    )
    (comp (ref "R58")
      (value "DNI")
      (footprint "eagle-import:0402")
      (libsource (lib "eagle-import") (part "R0402"))
    )
    (comp (ref "R91")
      (value "0R 1%")
      (footprint "eagle-import:0402")
      (fields
        (field (name "HQ_PART") "RE0250181")
        (field (name "LCSC_PART") "C17168")
        (field (name "MANUFACTURER") "YAGEO")
      )
      (libsource (lib "eagle-import") (part "0R0402"))
    )
    (comp (ref "R92")
      (value "DNI")
      (footprint "eagle-import:0402")
      (libsource (lib "eagle-import") (part "R0402"))
    )
    (comp (ref "R93")
      (value "10K 1%")
      (footprint "eagle-import:_0603X4-1206")
      (fields
        (field (name "HQ_PART") "RE0094682")
        (field (name "LCSC_PART") "C110924")
        (field (name "MANUFACTURER") "Yageo")
      )
      (libsource (lib "eagle-import") (part "10K-1%_ARRAY0603X4-1206"))
    )
    (comp (ref "R122")
      (value "1K 1%")
      (footprint "eagle-import:0402")
      (fields
        (field (name "HQ_PART") "RE0208724")
        (field (name "LCSC_PART") "C11702")
        (field (name "MANUFACTURER") "FH")
      )
      (libsource (lib "eagle-import") (part "1K-1%0402"))
    )
    (comp (ref "REL0")
      (value "DNI")
      (footprint "eagle-import:TP-ROUND")
      (libsource (lib "eagle-import") (part "TP-ROUND"))
    )
    (comp (ref "REL1")
      (value "DNI")
      (footprint "eagle-import:TP-ROUND")
      (libsource (lib "eagle-import") (part "TP-ROUND"))
    )
    (comp (ref "REL2")
      (value "DNI")
      (footprint "eagle-import:TP-ROUND")
      (libsource (lib "eagle-import") (part "TP-ROUND"))
    )
    (comp (ref "REL3")
      (value "DNI")
      (footprint "eagle-import:TP-ROUND")
      (libsource (lib "eagle-import") (part "TP-ROUND"))
    )
    (comp (ref "REL4")
      (value "DNI")
      (footprint "eagle-import:TP-ROUND")
      (libsource (lib "eagle-import") (part "TP-ROUND"))
    )
    (comp (ref "REL5")
      (value "DNI")
      (footprint "eagle-import:TP-ROUND")
      (libsource (lib "eagle-import") (part "TP-ROUND"))
    )
    (comp (ref "REL6")
      (value "DNI")
      (footprint "eagle-import:TP-ROUND")
      (libsource (lib "eagle-import") (part "TP-ROUND"))
    )
    (comp (ref "REL7")
      (value "DNI")
      (footprint "eagle-import:TP-ROUND")
      (libsource (lib "eagle-import") (part "TP-ROUND"))
    )
    (comp (ref "RN1")
      (value "100K 1%")
      (footprint "eagle-import:_0603X4-1206")
      (fields
        (field (name "HQ_PART") "RE0094681")
        (field (name "LCSC_PART") "C110374")
        (field (name "MANUFACTURER") "Yageo")
      )
      (libsource (lib "eagle-import") (part "100K-1%_ARRAY0603X4-1206"))
    )
    (comp (ref "RN2")
      (value "100K 1%")
      (footprint "eagle-import:_0603X4-1206")
      (fields
        (field (name "HQ_PART") "RE0094681")
        (field (name "LCSC_PART") "C110374")
        (field (name "MANUFACTURER") "Yageo")
      )
      (libsource (lib "eagle-import") (part "100K-1%_ARRAY0603X4-1206"))
    )
    (comp (ref "UTX")
      (value "DNI")
      (footprint "eagle-import:TP-ROUND")
      (libsource (lib "eagle-import") (part "TP-ROUND"))
    )
    (comp (ref "AVDD")
      (value "DNI")
      (footprint "eagle-import:TP-ROUND")
      (libsource (lib "eagle-import") (part "TP-ROUND"))
    )
    (comp (ref "BOOT")
      (value "DNI")
      (footprint "eagle-import:TP-ROUND")
      (libsource (lib "eagle-import") (part "TP-ROUND"))
    )
    (comp (ref "BT")
      (value "B3U-1000P")
      (footprint "eagle-import:B3U-1000P")
      (fields
        (field (name "HQ_PART") "SW0036094 ")
        (field (name "LCSC_PART") "C231329")
        (field (name "MANUFACTURER") "Omron")
      )
      (libsource (lib "eagle-import") (part "B3U-1000P"))
    )
    (comp (ref "C58")
      (value "15pF 50V")
      (footprint "eagle-import:0201")
      (fields
        (field (name "HQ_PART") "CA0136888")
        (field (name "LCSC_PART") "C22374851")
        (field (name "MANUFACTURER") "Yageo")
      )
      (libsource (lib "eagle-import") (part "15PF-50V0201"))
    )
    (comp (ref "C59")
      (value "15pF 50V")
      (footprint "eagle-import:0201")
      (fields
        (field (name "HQ_PART") "CA0136888")
        (field (name "LCSC_PART") "C22374851")
        (field (name "MANUFACTURER") "Yageo")
      )
      (libsource (lib "eagle-import") (part "15PF-50V0201"))
    )
    (comp (ref "C60")
      (value "1uF 25V")
      (footprint "eagle-import:0402")
      (fields
        (field (name "HQ_PART") "CA0175588")
        (field (name "LCSC_PART") "C52923")
        (field (name "MANUFACTURER") "TDK")
      )
      (libsource (lib "eagle-import") (part "1UF-25V0402"))
    )
    (comp (ref "C61")
      (value "100nF 25V")
      (footprint "eagle-import:0201")
      (fields
        (field (name "HQ_PART") "CA0183221")
        (field (name "LCSC_PART") "C76939")
        (field (name "MANUFACTURER") "Samsung")
      )
      (libsource (lib "eagle-import") (part "100NF-25V-0201"))
    )
    (comp (ref "C62")
      (value "100nF 25V")
      (footprint "eagle-import:0201")
      (fields
        (field (name "HQ_PART") "CA0183221")
        (field (name "LCSC_PART") "C76939")
        (field (name "MANUFACTURER") "Samsung")
      )
      (libsource (lib "eagle-import") (part "100NF-25V-0201"))
    )
    (comp (ref "C63")
      (value "100nF 25V")
      (footprint "eagle-import:0201")
      (fields
        (field (name "HQ_PART") "CA0183221")
        (field (name "LCSC_PART") "C76939")
        (field (name "MANUFACTURER") "Samsung")
      )
      (libsource (lib "eagle-import") (part "100NF-25V-0201"))
    )
    (comp (ref "C64")
      (value "100nF 25V")
      (footprint "eagle-import:0201")
      (fields
        (field (name "HQ_PART") "CA0183221")
        (field (name "LCSC_PART") "C76939")
        (field (name "MANUFACTURER") "Samsung")
      )
      (libsource (lib "eagle-import") (part "100NF-25V-0201"))
    )
    (comp (ref "C67")
      (value "100nF 25V")
      (footprint "eagle-import:0201")
      (fields
        (field (name "HQ_PART") "CA0183221")
        (field (name "LCSC_PART") "C76939")
        (field (name "MANUFACTURER") "Samsung")
      )
      (libsource (lib "eagle-import") (part "100NF-25V-0201"))
    )
    (comp (ref "C68")
      (value "100nF 25V")
      (footprint "eagle-import:0201")
      (fields
        (field (name "HQ_PART") "CA0183221")
        (field (name "LCSC_PART") "C76939")
        (field (name "MANUFACTURER") "Samsung")
      )
      (libsource (lib "eagle-import") (part "100NF-25V-0201"))
    )
    (comp (ref "C69")
      (value "100nF 25V")
      (footprint "eagle-import:0201")
      (fields
        (field (name "HQ_PART") "CA0183221")
        (field (name "LCSC_PART") "C76939")
        (field (name "MANUFACTURER") "Samsung")
      )
      (libsource (lib "eagle-import") (part "100NF-25V-0201"))
    )
    (comp (ref "C70")
      (value "100nF 25V")
      (footprint "eagle-import:0201")
      (fields
        (field (name "HQ_PART") "CA0183221")
        (field (name "LCSC_PART") "C76939")
        (field (name "MANUFACTURER") "Samsung")
      )
      (libsource (lib "eagle-import") (part "100NF-25V-0201"))
    )
    (comp (ref "C71")
      (value "100nF 25V")
      (footprint "eagle-import:0201")
      (fields
        (field (name "HQ_PART") "CA0183221")
        (field (name "LCSC_PART") "C76939")
        (field (name "MANUFACTURER") "Samsung")
      )
      (libsource (lib "eagle-import") (part "100NF-25V-0201"))
    )
    (comp (ref "C72")
      (value "100nF 25V")
      (footprint "eagle-import:0201")
      (fields
        (field (name "HQ_PART") "CA0183221")
        (field (name "LCSC_PART") "C76939")
        (field (name "MANUFACTURER") "Samsung")
      )
      (libsource (lib "eagle-import") (part "100NF-25V-0201"))
    )
    (comp (ref "C73")
      (value "100nF 25V")
      (footprint "eagle-import:0201")
      (fields
        (field (name "HQ_PART") "CA0183221")
        (field (name "LCSC_PART") "C76939")
        (field (name "MANUFACTURER") "Samsung")
      )
      (libsource (lib "eagle-import") (part "100NF-25V-0201"))
    )
    (comp (ref "C74")
      (value "100nF 25V")
      (footprint "eagle-import:0201")
      (fields
        (field (name "HQ_PART") "CA0183221")
        (field (name "LCSC_PART") "C76939")
        (field (name "MANUFACTURER") "Samsung")
      )
      (libsource (lib "eagle-import") (part "100NF-25V-0201"))
    )
    (comp (ref "C75")
      (value "100nF 25V")
      (footprint "eagle-import:0201")
      (fields
        (field (name "HQ_PART") "CA0183221")
        (field (name "LCSC_PART") "C76939")
        (field (name "MANUFACTURER") "Samsung")
      )
      (libsource (lib "eagle-import") (part "100NF-25V-0201"))
    )
    (comp (ref "C76")
      (value "100nF 25V")
      (footprint "eagle-import:0201")
      (fields
        (field (name "HQ_PART") "CA0183221")
        (field (name "LCSC_PART") "C76939")
        (field (name "MANUFACTURER") "Samsung")
      )
      (libsource (lib "eagle-import") (part "100NF-25V-0201"))
    )
    (comp (ref "C77")
      (value "100nF 25V")
      (footprint "eagle-import:0201")
      (fields
        (field (name "HQ_PART") "CA0183221")
        (field (name "LCSC_PART") "C76939")
        (field (name "MANUFACTURER") "Samsung")
      )
      (libsource (lib "eagle-import") (part "100NF-25V-0201"))
    )
    (comp (ref "C101")
      (value "100nF 25V")
      (footprint "eagle-import:0201")
      (fields
        (field (name "HQ_PART") "CA0183221")
        (field (name "LCSC_PART") "C76939")
        (field (name "MANUFACTURER") "Samsung")
      )
      (libsource (lib "eagle-import") (part "100NF-25V-0201"))
    )
    (comp (ref "C102")
      (value "1uF 16V")
      (footprint "eagle-import:0201")
      (fields
        (field (name "HQ_PART") "CA0176810")
        (field (name "LCSC_PART") "C307385")
        (field (name "MANUFACTURER") "WALSIN")
      )
      (libsource (lib "eagle-import") (part "1UF-16V0201"))
    )
    (comp (ref "C104")
      (value "1uF 25V")
      (footprint "eagle-import:0402")
      (fields
        (field (name "HQ_PART") "CA0175588")
        (field (name "LCSC_PART") "C52923")
        (field (name "MANUFACTURER") "TDK")
      )
      (libsource (lib "eagle-import") (part "1UF-25V0402"))
    )
    (comp (ref "CS")
      (value "DNI")
      (footprint "eagle-import:TP-ROUND")
      (libsource (lib "eagle-import") (part "TP-ROUND"))
    )
    (comp (ref "CS1")
      (value "DNI")
      (footprint "eagle-import:TP-ROUND")
      (libsource (lib "eagle-import") (part "TP-ROUND"))
    )
    (comp (ref "D17")
      (value "RCLAMP0582BQTCT")
      (footprint "eagle-import:SC75")
      (fields
        (field (name "HQ_PART") "PD0007296")
        (field (name "LCSC_PART") "C841193")
        (field (name "MANUFACTURER") "SEMTECH")
      )
      (libsource (lib "eagle-import") (part "RCLAMP0582BQTCT-"))
    )
    (comp (ref "D18")
      (value "RCLAMP0582BQTCT")
      (footprint "eagle-import:SC75")
      (fields
        (field (name "HQ_PART") "PD0007296")
        (field (name "LCSC_PART") "C841193")
        (field (name "MANUFACTURER") "SEMTECH")
      )
      (libsource (lib "eagle-import") (part "RCLAMP0582BQTCT-"))
    )
    (comp (ref "DNI")
      (value "0R 1%")
      (footprint "eagle-import:0402")
      (fields
        (field (name "PACKAGE") "0402")
        (field (name "HQ_PART") "RE0250181")
        (field (name "LCSC_PART") "C17168")
        (field (name "MANUFACTURER") "YAGEO")
      )
      (libsource (lib "eagle-import") (part "0R0402"))
    )
    (comp (ref "DVDD")
      (value "DNI")
      (footprint "eagle-import:TP-ROUND")
      (libsource (lib "eagle-import") (part "TP-ROUND"))
    )
    (comp (ref "IC15")
      (value "RP2040")
      (footprint "eagle-import:QFN56")
      (fields
        (field (name "HQ_PART") "ZHLM0164739")
        (field (name "LCSC_PART") "C2040")
        (field (name "MANUFACTURER") "Raspberry Pi ")
      )
      (libsource (lib "eagle-import") (part "RP2040"))
    )
    (comp (ref "IC17")
      (value "MCP6001RT-I/OT")
      (footprint "eagle-import:SOT23-5")
      (fields
        (field (name "HQ_PART") "IC0119727")
        (field (name "LCSC_PART") "C154973")
        (field (name "MANUFACTURER") "MICROCHIP")
      )
      (libsource (lib "eagle-import") (part "MCP6001RT"))
    )
    (comp (ref "IC18")
      (value "W25Q128JVPIQ")
      (footprint "eagle-import:SON127P600X500X75-8N")
      (fields
        (field (name "HQ_PART") "IC0150933")
        (field (name "LCSC_PART") "C190862")
        (field (name "MANUFACTURER") "Winbond")
      )
      (libsource (lib "eagle-import") (part "W25Q128JVP"))
    )
    (comp (ref "IOVDD")
      (value "DNI")
      (footprint "eagle-import:TP-ROUND")
      (libsource (lib "eagle-import") (part "TP-ROUND"))
    )
    (comp (ref "MCPVIN")
      (value "DNI")
      (footprint "eagle-import:TP-ROUND")
      (libsource (lib "eagle-import") (part "TP-ROUND"))
    )
    (comp (ref "MI")
      (value "DNI")
      (footprint "eagle-import:TP-ROUND")
      (libsource (lib "eagle-import") (part "TP-ROUND"))
    )
    (comp (ref "MISO1")
      (value "DNI")
      (footprint "eagle-import:TP-ROUND")
      (libsource (lib "eagle-import") (part "TP-ROUND"))
    )
    (comp (ref "MO")
      (value "DNI")
      (footprint "eagle-import:TP-ROUND")
      (libsource (lib "eagle-import") (part "TP-ROUND"))
    )
    (comp (ref "MOSI1")
      (value "DNI")
      (footprint "eagle-import:TP-ROUND")
      (libsource (lib "eagle-import") (part "TP-ROUND"))
    )
    (comp (ref "PROC")
      (value "Green")
      (footprint "eagle-import:LED-0603")
      (fields
        (field (name "HQ_PART") "PH0010430")
        (field (name "LCSC_PART") "C965804")
        (field (name "MANUFACTURER") "Wurth")
      )
      (libsource (lib "eagle-import") (part "LED-GREENLED-0603"))
    )
    (comp (ref "R15")
      (value "27R 1%")
      (footprint "eagle-import:0201")
      (fields
        (field (name "HQ_PART") "RE0209327 ")
        (field (name "LCSC_PART") "C473051")
        (field (name "MANUFACTURER") "FH")
      )
      (libsource (lib "eagle-import") (part "27R-1%0201"))
    )
    (comp (ref "R16")
      (value "1K 1%")
      (footprint "eagle-import:0201")
      (fields
        (field (name "HQ_PART") "RE0015967")
        (field (name "LCSC_PART") "C270365")
        (field (name "MANUFACTURER") "Yageo")
      )
      (libsource (lib "eagle-import") (part "1K-1%0201"))
    )
    (comp (ref "R109")
      (value "4.7K 1%")
      (footprint "eagle-import:0201")
      (fields
        (field (name "HQ_PART") "RE0208670")
        (field (name "LCSC_PART") "C270346")
        (field (name "MANUFACTURER") "RALEC")
      )
      (libsource (lib "eagle-import") (part "4.7K-1%0201"))
    )
    (comp (ref "R111")
      (value "DNI")
      (footprint "eagle-import:R0201")
      (libsource (lib "eagle-import") (part "R0201"))
    )
    (comp (ref "R112")
      (value "1K 1%")
      (footprint "eagle-import:0402")
      (fields
        (field (name "HQ_PART") "RE0208724")
        (field (name "LCSC_PART") "C11702")
        (field (name "MANUFACTURER") "FH")
      )
      (libsource (lib "eagle-import") (part "1K-1%0402"))
    )
    (comp (ref "R130")
      (value "1.2K 1%")
      (footprint "eagle-import:0402")
      (fields
        (field (name "HQ_PART") "RE0189064")
        (field (name "LCSC_PART") "C25890")
        (field (name "MANUFACTURER") "Uniohm")
      )
      (libsource (lib "eagle-import") (part "3.3K-1%0402"))
    )
    (comp (ref "R132")
      (value "10K 1%")
      (footprint "eagle-import:0402")
      (fields
        (field (name "HQ_PART") "RE0207399")
        (field (name "LCSC_PART") "C25744")
        (field (name "MANUFACTURER") "ROHM")
      )
      (libsource (lib "eagle-import") (part "10K-1%0402"))
    )
    (comp (ref "R152")
      (value "10R 1%")
      (footprint "eagle-import:0201")
      (fields
        (field (name "HQ_PART") "RE0210247")
        (field (name "LCSC_PART") "C270817")
        (field (name "MANUFACTURER") "Yageo")
      )
      (libsource (lib "eagle-import") (part "10R-1%0201"))
    )
    (comp (ref "R160")
      (value "27R 1%")
      (footprint "eagle-import:0201")
      (fields
        (field (name "HQ_PART") "RE0209327 ")
        (field (name "LCSC_PART") "C473051")
        (field (name "MANUFACTURER") "FH")
      )
      (libsource (lib "eagle-import") (part "27R-1%0201"))
    )
    (comp (ref "R163")
      (value "1K 1%")
      (footprint "eagle-import:0402")
      (fields
        (field (name "HQ_PART") "RE0208724")
        (field (name "LCSC_PART") "C11702")
        (field (name "MANUFACTURER") "FH")
      )
      (libsource (lib "eagle-import") (part "1K-1%0402"))
    )
    (comp (ref "R166")
      (value "1.2K 1%")
      (footprint "eagle-import:0402")
      (fields
        (field (name "HQ_PART") "RE0189064")
        (field (name "LCSC_PART") "C25890")
        (field (name "MANUFACTURER") "Uniohm")
      )
      (libsource (lib "eagle-import") (part "3.3K-1%0402"))
    )
    (comp (ref "R167")
      (value "1.2K 1%")
      (footprint "eagle-import:0402")
      (fields
        (field (name "HQ_PART") "RE0189064")
        (field (name "LCSC_PART") "C25890")
        (field (name "MANUFACTURER") "Uniohm")
      )
      (libsource (lib "eagle-import") (part "3.3K-1%0402"))
    )
    (comp (ref "R168")
      (value "1.2K 1%")
      (footprint "eagle-import:0402")
      (fields
        (field (name "HQ_PART") "RE0189064")
        (field (name "LCSC_PART") "C25890")
        (field (name "MANUFACTURER") "Uniohm")
      )
      (libsource (lib "eagle-import") (part "3.3K-1%0402"))
    )
    (comp (ref "REF1")
      (value "LM4040x30")
      (footprint "eagle-import:SOT23")
      (fields
        (field (name "HQ_PART") "IC0022950")
        (field (name "LCSC_PART") "C460604")
        (field (name "MANUFACTURER") "DIODES")
      )
      (libsource (lib "eagle-import") (part "LM4040C30FTA"))
    )
    (comp (ref "RES")
      (value "B3U-1000P")
      (footprint "eagle-import:B3U-1000P")
      (fields
        (field (name "HQ_PART") "SW0036094 ")
        (field (name "LCSC_PART") "C231329")
        (field (name "MANUFACTURER") "Omron")
      )
      (libsource (lib "eagle-import") (part "B3U-1000P"))
    )
    (comp (ref "RST")
      (value "DNI")
      (footprint "eagle-import:TP-ROUND")
      (libsource (lib "eagle-import") (part "TP-ROUND"))
    )
    (comp (ref "RX0")
      (value "DNI")
      (footprint "eagle-import:TP-ROUND")
      (libsource (lib "eagle-import") (part "TP-ROUND"))
    )
    (comp (ref "SC")
      (value "DNI")
      (footprint "eagle-import:TP-ROUND")
      (libsource (lib "eagle-import") (part "TP-ROUND"))
    )
    (comp (ref "SCL0")
      (value "DNI")
      (footprint "eagle-import:TP-ROUND")
      (libsource (lib "eagle-import") (part "TP-ROUND"))
    )
    (comp (ref "SCL1")
      (value "DNI")
      (footprint "eagle-import:TP-ROUND")
      (libsource (lib "eagle-import") (part "TP-ROUND"))
    )
    (comp (ref "SCLK1")
      (value "DNI")
      (footprint "eagle-import:TP-ROUND")
      (libsource (lib "eagle-import") (part "TP-ROUND"))
    )
    (comp (ref "SDA0")
      (value "DNI")
      (footprint "eagle-import:TP-ROUND")
      (libsource (lib "eagle-import") (part "TP-ROUND"))
    )
    (comp (ref "SDA1")
      (value "DNI")
      (footprint "eagle-import:TP-ROUND")
      (libsource (lib "eagle-import") (part "TP-ROUND"))
    )
    (comp (ref "TX0")
      (value "DNI")
      (footprint "eagle-import:TP-ROUND")
      (libsource (lib "eagle-import") (part "TP-ROUND"))
    )
    (comp (ref "VREF")
      (value "DNI")
      (footprint "eagle-import:TP-ROUND")
      (libsource (lib "eagle-import") (part "TP-ROUND"))
    )
    (comp (ref "X1")
      (value "12MHz")
      (footprint "eagle-import:WE-XTAL_CFPX-180")
      (fields
        (field (name "HQ_PART") "CR0250194")
        (field (name "LCSC_PART") "C20625731")
        (field (name "MANUFACTURER") "TKD")
      )
      (libsource (lib "eagle-import") (part "CRYSTAL-3225X322512MSB4SI"))
    )
  )
  (nets
    (net (code "1") (name "+1V1") (class "Default")
      (node (ref "C75") (pin "1") (pinfunction "1_1") (pintype "passive"))
      (node (ref "C76") (pin "1") (pinfunction "1_1") (pintype "passive"))
      (node (ref "C77") (pin "1") (pinfunction "1_1") (pintype "passive"))
      (node (ref "DVDD") (pin "TP") (pinfunction "P$1_TP") (pintype "bidirectional"))
      (node (ref "IC15") (pin "23") (pinfunction "DVDD_23") (pintype "bidirectional"))
      (node (ref "IC15") (pin "45") (pinfunction "VREG_VOUT_45") (pintype "bidirectional"))
      (node (ref "IC15") (pin "50") (pinfunction "DVDD_50") (pintype "bidirectional"))
    )
    (net (code "2") (name "+3V3") (class "Default")
      (node (ref "3VDC") (pin "TP") (pinfunction "P$1_TP") (pintype "bidirectional"))
      (node (ref "C103") (pin "1") (pinfunction "1_1") (pintype "passive"))
      (node (ref "C105") (pin "1") (pinfunction "1_1") (pintype "passive"))
      (node (ref "C12") (pin "1") (pinfunction "1_1") (pintype "passive"))
      (node (ref "C15") (pin "1") (pinfunction "1_1") (pintype "passive"))
      (node (ref "C18") (pin "1") (pinfunction "1_1") (pintype "passive"))
      (node (ref "C19") (pin "1") (pinfunction "1_1") (pintype "passive"))
      (node (ref "C20") (pin "1") (pinfunction "1_1") (pintype "passive"))
      (node (ref "C33") (pin "1") (pinfunction "1_1") (pintype "passive"))
      (node (ref "C34") (pin "1") (pinfunction "1_1") (pintype "passive"))
      (node (ref "C88") (pin "1") (pinfunction "1_1") (pintype "passive"))
      (node (ref "C89") (pin "1") (pinfunction "1_1") (pintype "passive"))
      (node (ref "C90") (pin "1") (pinfunction "1_1") (pintype "passive"))
      (node (ref "DSP") (pin "1") (pinfunction "1_1") (pintype "bidirectional"))
      (node (ref "DSP") (pin "2") (pinfunction "2_2") (pintype "bidirectional"))
      (node (ref "ETH1") (pin "10") (pinfunction "GREEN+_10") (pintype "passive"))
      (node (ref "ETH1") (pin "12") (pinfunction "YELLOW+_12") (pintype "passive"))
      (node (ref "IC20") (pin "28") (pinfunction "VDD_28") (pintype "power_in"))
      (node (ref "IC20") (pin "43") (pinfunction "PMODE2_43") (pintype "input"))
      (node (ref "IC20") (pin "44") (pinfunction "PMODE1_44") (pintype "input"))
      (node (ref "IC20") (pin "45") (pinfunction "PMODE0_45") (pintype "input"))
      (node (ref "IC22") (pin "2") (pinfunction "V+_2") (pintype "power_in"))
      (node (ref "IC23") (pin "4") (pinfunction "VDD_4") (pintype "power_in"))
      (node (ref "IC4") (pin "5") (pinfunction "VDD_5") (pintype "bidirectional"))
      (node (ref "IC9") (pin "16") (pinfunction "VCC_16") (pintype "power_in"))
      (node (ref "L2") (pin "2") (pinfunction "2_2") (pintype "passive"))
      (node (ref "L4") (pin "1") (pinfunction "1_1") (pintype "passive"))
      (node (ref "R123") (pin "1") (pinfunction "1_1") (pintype "passive"))
      (node (ref "R13") (pin "1") (pinfunction "1_1") (pintype "passive"))
      (node (ref "R145") (pin "2") (pinfunction "2_2") (pintype "passive"))
      (node (ref "R147") (pin "2") (pinfunction "2_2") (pintype "passive"))
      (node (ref "R149") (pin "A1") (pinfunction "1_A1") (pintype "passive"))
      (node (ref "R149") (pin "B1") (pinfunction "2_B1") (pintype "passive"))
      (node (ref "R149") (pin "C1") (pinfunction "3_C1") (pintype "passive"))
      (node (ref "R149") (pin "D1") (pinfunction "4_D1") (pintype "passive"))
      (node (ref "R169") (pin "1") (pinfunction "1_1") (pintype "passive"))
      (node (ref "R89") (pin "A2") (pinfunction "8_A2") (pintype "passive"))
      (node (ref "R89") (pin "B2") (pinfunction "7_B2") (pintype "passive"))
      (node (ref "R89") (pin "C2") (pinfunction "6_C2") (pintype "passive"))
      (node (ref "R89") (pin "D2") (pinfunction "5_D2") (pintype "passive"))
      (node (ref "R90") (pin "A2") (pinfunction "8_A2") (pintype "passive"))
      (node (ref "R90") (pin "B2") (pinfunction "7_B2") (pintype "passive"))
      (node (ref "R90") (pin "C2") (pinfunction "6_C2") (pintype "passive"))
      (node (ref "R90") (pin "D2") (pinfunction "5_D2") (pintype "passive"))
    )
    (net (code "3") (name "+3V3_A") (class "Default")
      (node (ref "3V3A") (pin "TP") (pinfunction "P$1_TP") (pintype "bidirectional"))
      (node (ref "C91") (pin "1") (pinfunction "1_1") (pintype "passive"))
      (node (ref "C92") (pin "1") (pinfunction "1_1") (pintype "passive"))
      (node (ref "C93") (pin "1") (pinfunction "1_1") (pintype "passive"))
      (node (ref "C94") (pin "1") (pinfunction "1_1") (pintype "passive"))
      (node (ref "C95") (pin "1") (pinfunction "1_1") (pintype "passive"))
      (node (ref "C96") (pin "1") (pinfunction "1_1") (pintype "passive"))
      (node (ref "IC20") (pin "11") (pinfunction "AVDD_11") (pintype "power_in"))
      (node (ref "IC20") (pin "15") (pinfunction "AVDD_15") (pintype "power_in"))
      (node (ref "IC20") (pin "17") (pinfunction "AVDD_17") (pintype "power_in"))
      (node (ref "IC20") (pin "21") (pinfunction "AVDD_21") (pintype "power_in"))
      (node (ref "IC20") (pin "4") (pinfunction "AVDD_4") (pintype "power_in"))
      (node (ref "IC20") (pin "8") (pinfunction "AVDD_8") (pintype "power_in"))
      (node (ref "L4") (pin "2") (pinfunction "2_2") (pintype "passive"))
      (node (ref "R139") (pin "2") (pinfunction "2_2") (pintype "passive"))
      (node (ref "R140") (pin "2") (pinfunction "2_2") (pintype "passive"))
      (node (ref "R146") (pin "2") (pinfunction "2_2") (pintype "passive"))
    )
    (net (code "4") (name "+3V3_MCU") (class "Default")
      (node (ref "C100") (pin "1") (pinfunction "1_1") (pintype "passive"))
      (node (ref "C101") (pin "1") (pinfunction "1_1") (pintype "passive"))
      (node (ref "C104") (pin "1") (pinfunction "1_1") (pintype "passive"))
      (node (ref "C64") (pin "1") (pinfunction "1_1") (pintype "passive"))
      (node (ref "C67") (pin "1") (pinfunction "1_1") (pintype "passive"))
      (node (ref "C68") (pin "1") (pinfunction "1_1") (pintype "passive"))
      (node (ref "C69") (pin "1") (pinfunction "1_1") (pintype "passive"))
      (node (ref "C70") (pin "1") (pinfunction "1_1") (pintype "passive"))
      (node (ref "C71") (pin "1") (pinfunction "1_1") (pintype "passive"))
      (node (ref "C72") (pin "1") (pinfunction "1_1") (pintype "passive"))
      (node (ref "C73") (pin "1") (pinfunction "1_1") (pintype "passive"))
      (node (ref "C99") (pin "1") (pinfunction "1_1") (pintype "passive"))
      (node (ref "IC15") (pin "1") (pinfunction "IOVDD_1") (pintype "bidirectional"))
      (node (ref "IC15") (pin "10") (pinfunction "IOVDD_10") (pintype "bidirectional"))
      (node (ref "IC15") (pin "22") (pinfunction "IOVDD_22") (pintype "bidirectional"))
      (node (ref "IC15") (pin "33") (pinfunction "IOVDD_33") (pintype "bidirectional"))
      (node (ref "IC15") (pin "42") (pinfunction "IOVDD_42") (pintype "bidirectional"))
      (node (ref "IC15") (pin "44") (pinfunction "VREG_VIN_44") (pintype "bidirectional"))
      (node (ref "IC15") (pin "48") (pinfunction "USB_VDD_48") (pintype "bidirectional"))
      (node (ref "IC15") (pin "49") (pinfunction "IOVDD_49") (pintype "bidirectional"))
      (node (ref "IC18") (pin "8") (pinfunction "VCC_8") (pintype "power_in"))
      (node (ref "IC19") (pin "8") (pinfunction "VCC_8") (pintype "power_in"))
      (node (ref "IC21") (pin "5") (pinfunction "VOUT_5") (pintype "bidirectional"))
      (node (ref "IOVDD") (pin "TP") (pinfunction "P$1_TP") (pintype "bidirectional"))
      (node (ref "PWR") (pin "A") (pinfunction "A_A") (pintype "passive"))
      (node (ref "R109") (pin "2") (pinfunction "2_2") (pintype "passive"))
      (node (ref "R111") (pin "2") (pinfunction "2_2") (pintype "passive"))
      (node (ref "R128") (pin "2") (pinfunction "2_2") (pintype "passive"))
      (node (ref "R130") (pin "1") (pinfunction "1_1") (pintype "passive"))
      (node (ref "R132") (pin "1") (pinfunction "1_1") (pintype "passive"))
      (node (ref "R152") (pin "1") (pinfunction "1_1") (pintype "passive"))
      (node (ref "R165") (pin "2") (pinfunction "2_2") (pintype "passive"))
      (node (ref "R166") (pin "1") (pinfunction "1_1") (pintype "passive"))
      (node (ref "R167") (pin "1") (pinfunction "1_1") (pintype "passive"))
      (node (ref "R168") (pin "1") (pinfunction "1_1") (pintype "passive"))
      (node (ref "R169") (pin "2") (pinfunction "2_2") (pintype "passive"))
    )
    (net (code "5") (name "+5V") (class "Default")
      (node (ref "5VDC") (pin "TP") (pinfunction "P$1_TP") (pintype "bidirectional"))
      (node (ref "C11") (pin "1") (pinfunction "1_1") (pintype "passive"))
      (node (ref "C14") (pin "1") (pinfunction "1_1") (pintype "passive"))
      (node (ref "C17") (pin "1") (pinfunction "1_1") (pintype "passive"))
      (node (ref "D15") (pin "A") (pinfunction "A_A") (pintype "passive"))
      (node (ref "DSP") (pin "3") (pinfunction "3_3") (pintype "bidirectional"))
      (node (ref "DSP") (pin "4") (pinfunction "4_4") (pintype "bidirectional"))
      (node (ref "L1") (pin "2") (pinfunction "2_2") (pintype "passive"))
      (node (ref "R11") (pin "1") (pinfunction "1_1") (pintype "passive"))
      (node (ref "R148") (pin "1") (pinfunction "1_1") (pintype "passive"))
    )
    (net (code "6") (name "+5V_MEA") (class "Default")
      (node (ref "IC10") (pin "1") (pinfunction "VDD_1") (pintype "power_in"))
      (node (ref "IC11") (pin "1") (pinfunction "VDD_1") (pintype "power_in"))
      (node (ref "IC12") (pin "1") (pinfunction "VDD_1") (pintype "power_in"))
      (node (ref "IC14") (pin "1") (pinfunction "VDD_1") (pintype "power_in"))
      (node (ref "IC16") (pin "1") (pinfunction "VDD_1") (pintype "power_in"))
      (node (ref "IC6") (pin "1") (pinfunction "VDD_1") (pintype "power_in"))
      (node (ref "IC7") (pin "1") (pinfunction "VDD_1") (pintype "power_in"))
      (node (ref "IC8") (pin "1") (pinfunction "VDD_1") (pintype "power_in"))
      (node (ref "J2") (pin "2") (pinfunction "2_2") (pintype "passive"))
      (node (ref "J7") (pin "2") (pinfunction "2_2") (pintype "passive"))
      (node (ref "R63") (pin "A1") (pinfunction "1_A1") (pintype "passive"))
      (node (ref "R63") (pin "B1") (pinfunction "2_B1") (pintype "passive"))
      (node (ref "R63") (pin "C1") (pinfunction "3_C1") (pintype "passive"))
      (node (ref "R63") (pin "D1") (pinfunction "4_D1") (pintype "passive"))
      (node (ref "R64") (pin "A1") (pinfunction "1_A1") (pintype "passive"))
      (node (ref "R64") (pin "B1") (pinfunction "2_B1") (pintype "passive"))
      (node (ref "R64") (pin "C1") (pinfunction "3_C1") (pintype "passive"))
      (node (ref "R64") (pin "D1") (pinfunction "4_D1") (pintype "passive"))
    )
    (net (code "7") (name "+5V_MEA1") (class "Default")
      (node (ref "5V-NI1") (pin "TP") (pinfunction "P$1_TP") (pintype "bidirectional"))
      (node (ref "C23") (pin "1") (pinfunction "+_1") (pintype "passive"))
      (node (ref "C45") (pin "2") (pinfunction "2_2") (pintype "passive"))
      (node (ref "D9") (pin "A") (pinfunction "A_A") (pintype "passive"))
      (node (ref "J2") (pin "1") (pinfunction "1_1") (pintype "passive"))
      (node (ref "L3") (pin "2") (pinfunction "2_2") (pintype "passive"))
      (node (ref "R96") (pin "1") (pinfunction "1_1") (pintype "passive"))
    )
    (net (code "8") (name "+5V_MEA2") (class "Default")
      (node (ref "5V-NI2") (pin "TP") (pinfunction "P$1_TP") (pintype "bidirectional"))
      (node (ref "C53") (pin "1") (pinfunction "+_1") (pintype "passive"))
      (node (ref "C57") (pin "2") (pinfunction "2_2") (pintype "passive"))
      (node (ref "D13") (pin "A") (pinfunction "A_A") (pintype "passive"))
      (node (ref "J7") (pin "1") (pinfunction "1_1") (pintype "passive"))
      (node (ref "L5") (pin "2") (pinfunction "2_2") (pintype "passive"))
      (node (ref "R108") (pin "1") (pinfunction "1_1") (pintype "passive"))
    )
    (net (code "9") (name "+12V") (class "Default")
      (node (ref "C1") (pin "1") (pinfunction "1_1") (pintype "passive"))
      (node (ref "C2") (pin "1") (pinfunction "1_1") (pintype "passive"))
      (node (ref "C3") (pin "1") (pinfunction "1_1") (pintype "passive"))
      (node (ref "C4") (pin "1") (pinfunction "1_1") (pintype "passive"))
      (node (ref "D1") (pin "C") (pinfunction "C_C") (pintype "passive"))
      (node (ref "D2") (pin "C") (pinfunction "C_C") (pintype "passive"))
      (node (ref "D3") (pin "C") (pinfunction "C_C") (pintype "passive"))
      (node (ref "D4") (pin "C") (pinfunction "C_C") (pintype "passive"))
      (node (ref "D5") (pin "C") (pinfunction "C_C") (pintype "passive"))
      (node (ref "D6") (pin "C") (pinfunction "C_C") (pintype "passive"))
      (node (ref "D7") (pin "C") (pinfunction "C_C") (pintype "passive"))
      (node (ref "D8") (pin "C") (pinfunction "C_C") (pintype "passive"))
      (node (ref "FAN") (pin "2") (pinfunction "2_2") (pintype "passive"))
      (node (ref "IC1") (pin "2") (pinfunction "IN_2") (pintype "bidirectional"))
      (node (ref "IC2") (pin "2") (pinfunction "IN_2") (pintype "bidirectional"))
      (node (ref "IC3") (pin "10") (pinfunction "COM_10") (pintype "bidirectional"))
      (node (ref "J10") (pin "1") (pinfunction "1_1") (pintype "passive"))
      (node (ref "J8") (pin "1") (pinfunction "1_1") (pintype "passive"))
      (node (ref "J9") (pin "1") (pinfunction "1_1") (pintype "passive"))
      (node (ref "K1") (pin "8") (pinfunction "8_8") (pintype "passive"))
      (node (ref "K2") (pin "8") (pinfunction "8_8") (pintype "passive"))
      (node (ref "K3") (pin "8") (pinfunction "8_8") (pintype "passive"))
      (node (ref "K4") (pin "8") (pinfunction "8_8") (pintype "passive"))
      (node (ref "K5") (pin "8") (pinfunction "8_8") (pintype "passive"))
      (node (ref "K6") (pin "8") (pinfunction "8_8") (pintype "passive"))
      (node (ref "K7") (pin "8") (pinfunction "8_8") (pintype "passive"))
      (node (ref "K8") (pin "8") (pinfunction "8_8") (pintype "passive"))
      (node (ref "R150") (pin "1") (pinfunction "1_1") (pintype "passive"))
      (node (ref "R162") (pin "2") (pinfunction "2_2") (pintype "passive"))
      (node (ref "R171") (pin "2") (pinfunction "2_2") (pintype "passive"))
      (node (ref "R94") (pin "2") (pinfunction "2_2") (pintype "passive"))
    )
    (net (code "10") (name "+12V_MEA") (class "Default")
      (node (ref "ADC12") (pin "TP") (pinfunction "P$1_TP") (pintype "bidirectional"))
      (node (ref "IC15") (pin "41") (pinfunction "GPIO29/ADC3_41") (pintype "bidirectional"))
      (node (ref "R94") (pin "1") (pinfunction "1_1") (pintype "passive"))
      (node (ref "R95") (pin "2") (pinfunction "2_2") (pintype "passive"))
    )
    (net (code "11") (name "5V_EN") (class "Default")
      (node (ref "IC1") (pin "6") (pinfunction "EN_6") (pintype "bidirectional"))
      (node (ref "R1") (pin "1") (pinfunction "1_1") (pintype "passive"))
      (node (ref "R161") (pin "2") (pinfunction "2_2") (pintype "passive"))
      (node (ref "R162") (pin "1") (pinfunction "1_1") (pintype "passive"))
    )
    (net (code "12") (name "AC_L") (class "Default")
      (node (ref "AC/DC1") (pin "AC_L") (pinfunction "AC/L_AC_L") (pintype "input"))
      (node (ref "AC/DC2") (pin "AC/L") (pinfunction "AC/L_AC/L") (pintype "input"))
      (node (ref "AC_L") (pin "1") (pinfunction "MOUNT_1") (pintype "passive"))
      (node (ref "AC_L") (pin "2") (pinfunction "MOUNT_2") (pintype "passive"))
      (node (ref "K1") (pin "3") (pinfunction "3_3") (pintype "passive"))
      (node (ref "K1") (pin "6") (pinfunction "6_6") (pintype "passive"))
      (node (ref "K2") (pin "3") (pinfunction "3_3") (pintype "passive"))
      (node (ref "K2") (pin "6") (pinfunction "6_6") (pintype "passive"))
      (node (ref "K3") (pin "3") (pinfunction "3_3") (pintype "passive"))
      (node (ref "K3") (pin "6") (pinfunction "6_6") (pintype "passive"))
      (node (ref "K4") (pin "3") (pinfunction "3_3") (pintype "passive"))
      (node (ref "K4") (pin "6") (pinfunction "6_6") (pintype "passive"))
      (node (ref "K5") (pin "3") (pinfunction "3_3") (pintype "passive"))
      (node (ref "K5") (pin "6") (pinfunction "6_6") (pintype "passive"))
      (node (ref "K6") (pin "3") (pinfunction "3_3") (pintype "passive"))
      (node (ref "K6") (pin "6") (pinfunction "6_6") (pintype "passive"))
      (node (ref "K7") (pin "3") (pinfunction "3_3") (pintype "passive"))
      (node (ref "K7") (pin "6") (pinfunction "6_6") (pintype "passive"))
      (node (ref "K8") (pin "3") (pinfunction "3_3") (pintype "passive"))
      (node (ref "K8") (pin "6") (pinfunction "6_6") (pintype "passive"))
      (node (ref "R106") (pin "1") (pinfunction "1_1") (pintype "passive"))
      (node (ref "R62") (pin "1") (pinfunction "1_1") (pintype "passive"))
    )
    (net (code "13") (name "ADC_TEMP") (class "Default")
      (node (ref "ADC_TEMP") (pin "TP") (pinfunction "P$1_TP") (pintype "bidirectional"))
      (node (ref "IC15") (pin "39") (pinfunction "GPIO27/ADC1_39") (pintype "bidirectional"))
      (node (ref "IC23") (pin "3") (pinfunction "VOUT_3") (pintype "output"))
    )
    (net (code "14") (name "ADC_V_USB") (class "Default")
      (node (ref "ADCUSB") (pin "TP") (pinfunction "P$1_TP") (pintype "bidirectional"))
      (node (ref "IC15") (pin "38") (pinfunction "GPIO26/ADC0_38") (pintype "bidirectional"))
      (node (ref "R126") (pin "2") (pinfunction "2_2") (pintype "passive"))
      (node (ref "R127") (pin "1") (pinfunction "1_1") (pintype "passive"))
    )
    (net (code "15") (name "AGND") (class "Default")
      (node (ref "AC/DC1") (pin "AC_N") (pinfunction "AC/N_AC_N") (pintype "input"))
      (node (ref "AC/DC2") (pin "AC/N") (pinfunction "AC/N_AC/N") (pintype "input"))
      (node (ref "AC_N") (pin "1") (pinfunction "MOUNT_1") (pintype "passive"))
      (node (ref "AC_N") (pin "2") (pinfunction "MOUNT_2") (pintype "passive"))
      (node (ref "C106") (pin "2") (pinfunction "2_2") (pintype "passive"))
      (node (ref "C107") (pin "2") (pinfunction "2_2") (pintype "passive"))
      (node (ref "C108") (pin "2") (pinfunction "2_2") (pintype "passive"))
      (node (ref "C109") (pin "2") (pinfunction "2_2") (pintype "passive"))
      (node (ref "C110") (pin "2") (pinfunction "2_2") (pintype "passive"))
      (node (ref "C111") (pin "2") (pinfunction "2_2") (pintype "passive"))
      (node (ref "C112") (pin "2") (pinfunction "2_2") (pintype "passive"))
      (node (ref "C113") (pin "2") (pinfunction "2_2") (pintype "passive"))
      (node (ref "C23") (pin "2") (pinfunction "-_2") (pintype "passive"))
      (node (ref "C24") (pin "2") (pinfunction "2_2") (pintype "passive"))
      (node (ref "C25") (pin "2") (pinfunction "2_2") (pintype "passive"))
      (node (ref "C26") (pin "2") (pinfunction "2_2") (pintype "passive"))
      (node (ref "C27") (pin "2") (pinfunction "2_2") (pintype "passive"))
      (node (ref "C28") (pin "2") (pinfunction "2_2") (pintype "passive"))
      (node (ref "C29") (pin "2") (pinfunction "2_2") (pintype "passive"))
      (node (ref "C30") (pin "2") (pinfunction "2_2") (pintype "passive"))
      (node (ref "C31") (pin "2") (pinfunction "2_2") (pintype "passive"))
      (node (ref "C32") (pin "2") (pinfunction "2_2") (pintype "passive"))
      (node (ref "C35") (pin "2") (pinfunction "-_2") (pintype "passive"))
      (node (ref "C36") (pin "2") (pinfunction "2_2") (pintype "passive"))
      (node (ref "C37") (pin "2") (pinfunction "2_2") (pintype "passive"))
      (node (ref "C38") (pin "2") (pinfunction "2_2") (pintype "passive"))
      (node (ref "C39") (pin "2") (pinfunction "2_2") (pintype "passive"))
      (node (ref "C40") (pin "2") (pinfunction "2_2") (pintype "passive"))
      (node (ref "C41") (pin "2") (pinfunction "2_2") (pintype "passive"))
      (node (ref "C42") (pin "2") (pinfunction "2_2") (pintype "passive"))
      (node (ref "C43") (pin "2") (pinfunction "2_2") (pintype "passive"))
      (node (ref "C44") (pin "2") (pinfunction "2_2") (pintype "passive"))
      (node (ref "C45") (pin "1") (pinfunction "1_1") (pintype "passive"))
      (node (ref "C47") (pin "2") (pinfunction "-_2") (pintype "passive"))
      (node (ref "C48") (pin "2") (pinfunction "2_2") (pintype "passive"))
      (node (ref "C49") (pin "2") (pinfunction "2_2") (pintype "passive"))
      (node (ref "C50") (pin "2") (pinfunction "2_2") (pintype "passive"))
      (node (ref "C53") (pin "2") (pinfunction "-_2") (pintype "passive"))
      (node (ref "C54") (pin "2") (pinfunction "2_2") (pintype "passive"))
      (node (ref "C55") (pin "2") (pinfunction "2_2") (pintype "passive"))
      (node (ref "C56") (pin "2") (pinfunction "2_2") (pintype "passive"))
      (node (ref "C57") (pin "1") (pinfunction "1_1") (pintype "passive"))
      (node (ref "D11") (pin "A") (pinfunction "A_A") (pintype "passive"))
      (node (ref "D14") (pin "A") (pinfunction "A_A") (pintype "passive"))
      (node (ref "IC10") (pin "5") (pinfunction "GND_5") (pintype "power_in"))
      (node (ref "IC11") (pin "5") (pinfunction "GND_5") (pintype "power_in"))
      (node (ref "IC12") (pin "5") (pinfunction "GND_5") (pintype "power_in"))
      (node (ref "IC14") (pin "5") (pinfunction "GND_5") (pintype "power_in"))
      (node (ref "IC16") (pin "5") (pinfunction "GND_5") (pintype "power_in"))
      (node (ref "IC6") (pin "5") (pinfunction "GND_5") (pintype "power_in"))
      (node (ref "IC7") (pin "5") (pinfunction "GND_5") (pintype "power_in"))
      (node (ref "IC8") (pin "5") (pinfunction "GND_5") (pintype "power_in"))
      (node (ref "R104") (pin "2") (pinfunction "2_2") (pintype "passive"))
      (node (ref "R108") (pin "2") (pinfunction "2_2") (pintype "passive"))
      (node (ref "R113") (pin "1") (pinfunction "1_1") (pintype "passive"))
      (node (ref "R115") (pin "2") (pinfunction "2_2") (pintype "passive"))
      (node (ref "R120") (pin "2") (pinfunction "2_2") (pintype "passive"))
      (node (ref "R25") (pin "2") (pinfunction "2_2") (pintype "passive"))
      (node (ref "R26") (pin "2") (pinfunction "2_2") (pintype "passive"))
      (node (ref "R27") (pin "2") (pinfunction "2_2") (pintype "passive"))
      (node (ref "R28") (pin "2") (pinfunction "2_2") (pintype "passive"))
      (node (ref "R29") (pin "2") (pinfunction "2_2") (pintype "passive"))
      (node (ref "R30") (pin "2") (pinfunction "2_2") (pintype "passive"))
      (node (ref "R31") (pin "2") (pinfunction "2_2") (pintype "passive"))
      (node (ref "R32") (pin "2") (pinfunction "2_2") (pintype "passive"))
      (node (ref "R33") (pin "1") (pinfunction "1_1") (pintype "passive"))
      (node (ref "R35") (pin "2") (pinfunction "2_2") (pintype "passive"))
      (node (ref "R40") (pin "2") (pinfunction "2_2") (pintype "passive"))
      (node (ref "R41") (pin "1") (pinfunction "1_1") (pintype "passive"))
      (node (ref "R43") (pin "2") (pinfunction "2_2") (pintype "passive"))
      (node (ref "R48") (pin "2") (pinfunction "2_2") (pintype "passive"))
      (node (ref "R49") (pin "1") (pinfunction "1_1") (pintype "passive"))
      (node (ref "R51") (pin "2") (pinfunction "2_2") (pintype "passive"))
      (node (ref "R56") (pin "2") (pinfunction "2_2") (pintype "passive"))
      (node (ref "R65") (pin "1") (pinfunction "1_1") (pintype "passive"))
      (node (ref "R67") (pin "2") (pinfunction "2_2") (pintype "passive"))
      (node (ref "R72") (pin "2") (pinfunction "2_2") (pintype "passive"))
      (node (ref "R73") (pin "1") (pinfunction "1_1") (pintype "passive"))
      (node (ref "R75") (pin "2") (pinfunction "2_2") (pintype "passive"))
      (node (ref "R80") (pin "2") (pinfunction "2_2") (pintype "passive"))
      (node (ref "R81") (pin "1") (pinfunction "1_1") (pintype "passive"))
      (node (ref "R83") (pin "2") (pinfunction "2_2") (pintype "passive"))
      (node (ref "R88") (pin "2") (pinfunction "2_2") (pintype "passive"))
      (node (ref "R96") (pin "2") (pinfunction "2_2") (pintype "passive"))
      (node (ref "R97") (pin "1") (pinfunction "1_1") (pintype "passive"))
      (node (ref "R99") (pin "2") (pinfunction "2_2") (pintype "passive"))
    )
    (net (code "16") (name "AVDD") (class "Default")
      (node (ref "AVDD") (pin "TP") (pinfunction "P$1_TP") (pintype "bidirectional"))
      (node (ref "C62") (pin "1") (pinfunction "1_1") (pintype "passive"))
      (node (ref "C74") (pin "1") (pinfunction "1_1") (pintype "passive"))
      (node (ref "DNI") (pin "1") (pinfunction "1_1") (pintype "passive"))
      (node (ref "IC15") (pin "43") (pinfunction "ADC_AVDD_43") (pintype "bidirectional"))
      (node (ref "IC17") (pin "1") (pinfunction "OUT_1") (pintype "output"))
      (node (ref "IC17") (pin "4") (pinfunction "-IN_4") (pintype "input"))
    )
    (net (code "17") (name "BUCK_EN") (class "Default")
      (node (ref "IC15") (pin "37") (pinfunction "GPIO25_37") (pintype "bidirectional"))
      (node (ref "R1") (pin "2") (pinfunction "2_2") (pintype "passive"))
      (node (ref "R172") (pin "2") (pinfunction "2_2") (pintype "passive"))
    )
    (net (code "18") (name "CC1") (class "Default")
      (node (ref "R125") (pin "1") (pinfunction "1_1") (pintype "passive"))
      (node (ref "USB1") (pin "A5") (pinfunction "CC1_A5") (pintype "bidirectional"))
    )
    (net (code "19") (name "CC2") (class "Default")
      (node (ref "R124") (pin "1") (pinfunction "1_1") (pintype "passive"))
      (node (ref "USB1") (pin "B5") (pinfunction "CC2_B5") (pintype "bidirectional"))
    )
    (net (code "20") (name "FAN_CTRL") (class "Default")
      (node (ref "FCTL") (pin "TP") (pinfunction "P$1_TP") (pintype "bidirectional"))
      (node (ref "IC15") (pin "34") (pinfunction "GPIO22_34") (pintype "bidirectional"))
      (node (ref "R164") (pin "1") (pinfunction "1_1") (pintype "passive"))
      (node (ref "R165") (pin "1") (pinfunction "1_1") (pintype "passive"))
      (node (ref "T1") (pin "1") (pinfunction "G_1") (pintype "passive"))
    )
    (net (code "21") (name "FB1") (class "Default")
      (node (ref "C5") (pin "2") (pinfunction "2_2") (pintype "passive"))
      (node (ref "FB1") (pin "TP") (pinfunction "P$1_TP") (pintype "bidirectional"))
      (node (ref "IC13") (pin "2") (pinfunction "FB_2") (pintype "input"))
      (node (ref "R60") (pin "1") (pinfunction "1_1") (pintype "passive"))
      (node (ref "R61") (pin "2") (pinfunction "2_2") (pintype "passive"))
    )
    (net (code "22") (name "FB2") (class "Default")
      (node (ref "C51") (pin "2") (pinfunction "2_2") (pintype "passive"))
      (node (ref "FB2") (pin "TP") (pinfunction "P$1_TP") (pintype "bidirectional"))
      (node (ref "IC5") (pin "2") (pinfunction "FB_2") (pintype "input"))
      (node (ref "R105") (pin "2") (pinfunction "2_2") (pintype "passive"))
      (node (ref "R107") (pin "1") (pinfunction "1_1") (pintype "passive"))
    )
    (net (code "23") (name "FBIN1") (class "Default")
      (node (ref "C22") (pin "2") (pinfunction "2_2") (pintype "passive"))
      (node (ref "D9") (pin "C") (pinfunction "C_C") (pintype "passive"))
      (node (ref "R61") (pin "1") (pinfunction "1_1") (pintype "passive"))
    )
    (net (code "24") (name "FBIN2") (class "Default")
      (node (ref "C52") (pin "2") (pinfunction "2_2") (pintype "passive"))
      (node (ref "D13") (pin "C") (pinfunction "C_C") (pintype "passive"))
      (node (ref "R105") (pin "1") (pinfunction "1_1") (pintype "passive"))
    )
    (net (code "25") (name "GND") (class "Default")
      (node (ref "AC/DC1") (pin "-V") (pinfunction "-V_-V") (pintype "output"))
      (node (ref "AC/DC2") (pin "-V") (pinfunction "-V_-V") (pintype "output"))
      (node (ref "BT") (pin "2") (pinfunction "P$2_2") (pintype "bidirectional"))
      (node (ref "C1") (pin "2") (pinfunction "2_2") (pintype "passive"))
      (node (ref "C10") (pin "2") (pinfunction "-_2") (pintype "passive"))
      (node (ref "C100") (pin "2") (pinfunction "2_2") (pintype "passive"))
      (node (ref "C101") (pin "2") (pinfunction "2_2") (pintype "passive"))
      (node (ref "C102") (pin "2") (pinfunction "2_2") (pintype "passive"))
      (node (ref "C103") (pin "2") (pinfunction "2_2") (pintype "passive"))
      (node (ref "C104") (pin "2") (pinfunction "2_2") (pintype "passive"))
      (node (ref "C105") (pin "2") (pinfunction "2_2") (pintype "passive"))
      (node (ref "C13") (pin "2") (pinfunction "-_2") (pintype "passive"))
      (node (ref "C14") (pin "2") (pinfunction "2_2") (pintype "passive"))
      (node (ref "C15") (pin "2") (pinfunction "2_2") (pintype "passive"))
      (node (ref "C16") (pin "2") (pinfunction "-_2") (pintype "passive"))
      (node (ref "C17") (pin "2") (pinfunction "2_2") (pintype "passive"))
      (node (ref "C18") (pin "2") (pinfunction "2_2") (pintype "passive"))
      (node (ref "C19") (pin "2") (pinfunction "2_2") (pintype "passive"))
      (node (ref "C2") (pin "2") (pinfunction "2_2") (pintype "passive"))
      (node (ref "C20") (pin "2") (pinfunction "2_2") (pintype "passive"))
      (node (ref "C3") (pin "2") (pinfunction "2_2") (pintype "passive"))
      (node (ref "C33") (pin "2") (pinfunction "2_2") (pintype "passive"))
      (node (ref "C34") (pin "2") (pinfunction "2_2") (pintype "passive"))
      (node (ref "C4") (pin "2") (pinfunction "2_2") (pintype "passive"))
      (node (ref "C58") (pin "2") (pinfunction "2_2") (pintype "passive"))
      (node (ref "C59") (pin "2") (pinfunction "2_2") (pintype "passive"))
      (node (ref "C6") (pin "2") (pinfunction "2_2") (pintype "passive"))
      (node (ref "C60") (pin "2") (pinfunction "2_2") (pintype "passive"))
      (node (ref "C61") (pin "2") (pinfunction "2_2") (pintype "passive"))
      (node (ref "C62") (pin "2") (pinfunction "2_2") (pintype "passive"))
      (node (ref "C63") (pin "2") (pinfunction "2_2") (pintype "passive"))
      (node (ref "C64") (pin "2") (pinfunction "2_2") (pintype "passive"))
      (node (ref "C65") (pin "2") (pinfunction "2_2") (pintype "passive"))
      (node (ref "C66") (pin "2") (pinfunction "2_2") (pintype "passive"))
      (node (ref "C67") (pin "2") (pinfunction "2_2") (pintype "passive"))
      (node (ref "C68") (pin "2") (pinfunction "2_2") (pintype "passive"))
      (node (ref "C69") (pin "2") (pinfunction "2_2") (pintype "passive"))
      (node (ref "C7") (pin "2") (pinfunction "2_2") (pintype "passive"))
      (node (ref "C70") (pin "2") (pinfunction "2_2") (pintype "passive"))
      (node (ref "C71") (pin "2") (pinfunction "2_2") (pintype "passive"))
      (node (ref "C72") (pin "2") (pinfunction "2_2") (pintype "passive"))
      (node (ref "C73") (pin "2") (pinfunction "2_2") (pintype "passive"))
      (node (ref "C74") (pin "2") (pinfunction "2_2") (pintype "passive"))
      (node (ref "C75") (pin "2") (pinfunction "2_2") (pintype "passive"))
      (node (ref "C76") (pin "2") (pinfunction "2_2") (pintype "passive"))
      (node (ref "C77") (pin "2") (pinfunction "2_2") (pintype "passive"))
      (node (ref "C78") (pin "2") (pinfunction "2_2") (pintype "passive"))
      (node (ref "C79") (pin "2") (pinfunction "2_2") (pintype "passive"))
      (node (ref "C80") (pin "2") (pinfunction "2_2") (pintype "passive"))
      (node (ref "C83") (pin "1") (pinfunction "1_1") (pintype "passive"))
      (node (ref "C84") (pin "2") (pinfunction "2_2") (pintype "passive"))
      (node (ref "C85") (pin "2") (pinfunction "2_2") (pintype "passive"))
      (node (ref "C86") (pin "2") (pinfunction "2_2") (pintype "passive"))
      (node (ref "C87") (pin "2") (pinfunction "2_2") (pintype "passive"))
      (node (ref "C88") (pin "2") (pinfunction "2_2") (pintype "passive"))
      (node (ref "C89") (pin "2") (pinfunction "2_2") (pintype "passive"))
      (node (ref "C90") (pin "2") (pinfunction "2_2") (pintype "passive"))
      (node (ref "C91") (pin "2") (pinfunction "2_2") (pintype "passive"))
      (node (ref "C92") (pin "2") (pinfunction "2_2") (pintype "passive"))
      (node (ref "C93") (pin "2") (pinfunction "2_2") (pintype "passive"))
      (node (ref "C94") (pin "2") (pinfunction "2_2") (pintype "passive"))
      (node (ref "C95") (pin "2") (pinfunction "2_2") (pintype "passive"))
      (node (ref "C96") (pin "2") (pinfunction "2_2") (pintype "passive"))
      (node (ref "C97") (pin "2") (pinfunction "2_2") (pintype "passive"))
      (node (ref "C98") (pin "2") (pinfunction "2_2") (pintype "passive"))
      (node (ref "C99") (pin "2") (pinfunction "2_2") (pintype "passive"))
      (node (ref "D16") (pin "A") (pinfunction "A_A") (pintype "passive"))
      (node (ref "D17") (pin "3") (pinfunction "3_3") (pintype "bidirectional"))
      (node (ref "D18") (pin "3") (pinfunction "3_3") (pintype "bidirectional"))
      (node (ref "DAT") (pin "C") (pinfunction "C_C") (pintype "passive"))
      (node (ref "DSP") (pin "5") (pinfunction "5_5") (pintype "bidirectional"))
      (node (ref "DSP") (pin "8") (pinfunction "8_8") (pintype "bidirectional"))
      (node (ref "DSP") (pin "Z0") (pinfunction "Z1_Z0") (pintype "bidirectional"))
      (node (ref "DSP") (pin "Z1") (pinfunction "Z1_Z1") (pintype "bidirectional"))
      (node (ref "DSP") (pin "Z2") (pinfunction "Z2_Z2") (pintype "bidirectional"))
      (node (ref "DSP") (pin "Z3") (pinfunction "Z3_Z3") (pintype "bidirectional"))
      (node (ref "DSP") (pin "Z4") (pinfunction "Z3_Z4") (pintype "bidirectional"))
      (node (ref "DSP") (pin "Z5") (pinfunction "Z4_Z5") (pintype "bidirectional"))
      (node (ref "ESD1") (pin "1") (pinfunction "A_1") (pintype "bidirectional"))
      (node (ref "ETH1") (pin "8") (pinfunction "GND_8") (pintype "power_in"))
      (node (ref "GDRC") (pin "4") (pinfunction "P$4_4") (pintype "bidirectional"))
      (node (ref "GND") (pin "TP") (pinfunction "P$1_TP") (pintype "bidirectional"))
      (node (ref "GND-3") (pin "TP") (pinfunction "P$1_TP") (pintype "bidirectional"))
      (node (ref "GND-5") (pin "TP") (pinfunction "P$1_TP") (pintype "bidirectional"))
      (node (ref "IC1") (pin "4") (pinfunction "GND_4") (pintype "bidirectional"))
      (node (ref "IC15") (pin "19") (pinfunction "TESTEN_19") (pintype "bidirectional"))
      (node (ref "IC15") (pin "PAD") (pinfunction "GND_PAD") (pintype "bidirectional"))
      (node (ref "IC17") (pin "5") (pinfunction "V-_5") (pintype "power_in"))
      (node (ref "IC18") (pin "4") (pinfunction "GND_4") (pintype "power_in"))
      (node (ref "IC18") (pin "PAD") (pinfunction "GND_PAD") (pintype "power_in"))
      (node (ref "IC19") (pin "2") (pinfunction "A1_2") (pintype "bidirectional"))
      (node (ref "IC19") (pin "3") (pinfunction "A2_3") (pintype "bidirectional"))
      (node (ref "IC19") (pin "4") (pinfunction "GND_4") (pintype "power_in"))
      (node (ref "IC19") (pin "7") (pinfunction "WP_7") (pintype "bidirectional"))
      (node (ref "IC19") (pin "9") (pinfunction "GND_9") (pintype "power_in"))
      (node (ref "IC2") (pin "4") (pinfunction "GND_4") (pintype "bidirectional"))
      (node (ref "IC20") (pin "14") (pinfunction "AGND_14") (pintype "power_in"))
      (node (ref "IC20") (pin "16") (pinfunction "AGND_16") (pintype "power_in"))
      (node (ref "IC20") (pin "19") (pinfunction "AGND_19") (pintype "power_in"))
      (node (ref "IC20") (pin "29") (pinfunction "GND_29") (pintype "passive"))
      (node (ref "IC20") (pin "3") (pinfunction "AGND_3") (pintype "power_in"))
      (node (ref "IC20") (pin "48") (pinfunction "AGND_48") (pintype "power_in"))
      (node (ref "IC20") (pin "9") (pinfunction "AGND_9") (pintype "power_in"))
      (node (ref "IC21") (pin "2") (pinfunction "GND_2") (pintype "bidirectional"))
      (node (ref "IC22") (pin "5") (pinfunction "V-_5") (pintype "power_in"))
      (node (ref "IC23") (pin "2") (pinfunction "GND_2") (pintype "power_in"))
      (node (ref "IC3") (pin "9") (pinfunction "GND_9") (pintype "bidirectional"))
      (node (ref "IC4") (pin "11") (pinfunction "A0_11") (pintype "bidirectional"))
      (node (ref "IC4") (pin "12") (pinfunction "A1_12") (pintype "bidirectional"))
      (node (ref "IC4") (pin "13") (pinfunction "A2_13") (pintype "bidirectional"))
      (node (ref "IC4") (pin "6") (pinfunction "VSS_6") (pintype "bidirectional"))
      (node (ref "IC4") (pin "PAD") (pinfunction "VSS_PAD") (pintype "bidirectional"))
      (node (ref "IC9") (pin "8") (pinfunction "GND_8") (pintype "power_in"))
      (node (ref "OPT1") (pin "11") (pinfunction "11_11") (pintype "passive"))
      (node (ref "OPT1") (pin "13") (pinfunction "13_13") (pintype "passive"))
      (node (ref "OPT1") (pin "15") (pinfunction "15_15") (pintype "passive"))
      (node (ref "OPT1") (pin "9") (pinfunction "9_9") (pintype "passive"))
      (node (ref "OPT2") (pin "11") (pinfunction "11_11") (pintype "passive"))
      (node (ref "OPT2") (pin "13") (pinfunction "13_13") (pintype "passive"))
      (node (ref "OPT2") (pin "15") (pinfunction "15_15") (pintype "passive"))
      (node (ref "OPT2") (pin "9") (pinfunction "9_9") (pintype "passive"))
      (node (ref "P12ON") (pin "C") (pinfunction "C_C") (pintype "passive"))
      (node (ref "P3ON") (pin "C") (pinfunction "C_C") (pintype "passive"))
      (node (ref "P5ON") (pin "C") (pinfunction "C_C") (pintype "passive"))
      (node (ref "PROC") (pin "C") (pinfunction "C_C") (pintype "passive"))
      (node (ref "R110") (pin "1") (pinfunction "1_1") (pintype "passive"))
      (node (ref "R12") (pin "2") (pinfunction "2_2") (pintype "passive"))
      (node (ref "R121") (pin "2") (pinfunction "2_2") (pintype "passive"))
      (node (ref "R124") (pin "2") (pinfunction "2_2") (pintype "passive"))
      (node (ref "R125") (pin "2") (pinfunction "2_2") (pintype "passive"))
      (node (ref "R127") (pin "2") (pinfunction "2_2") (pintype "passive"))
      (node (ref "R129") (pin "1") (pinfunction "1_1") (pintype "passive"))
      (node (ref "R131") (pin "2") (pinfunction "2_2") (pintype "passive"))
      (node (ref "R14") (pin "2") (pinfunction "2_2") (pintype "passive"))
      (node (ref "R143") (pin "1") (pinfunction "1_1") (pintype "passive"))
      (node (ref "R151") (pin "1") (pinfunction "1_1") (pintype "passive"))
      (node (ref "R161") (pin "1") (pinfunction "1_1") (pintype "passive"))
      (node (ref "R164") (pin "2") (pinfunction "2_2") (pintype "passive"))
      (node (ref "R2") (pin "1") (pinfunction "1_1") (pintype "passive"))
      (node (ref "R4") (pin "2") (pinfunction "2_2") (pintype "passive"))
      (node (ref "R6") (pin "2") (pinfunction "2_2") (pintype "passive"))
      (node (ref "R93") (pin "A2") (pinfunction "8_A2") (pintype "passive"))
      (node (ref "R93") (pin "B2") (pinfunction "7_B2") (pintype "passive"))
      (node (ref "R93") (pin "C2") (pinfunction "6_C2") (pintype "passive"))
      (node (ref "R93") (pin "D2") (pinfunction "5_D2") (pintype "passive"))
      (node (ref "R95") (pin "1") (pinfunction "1_1") (pintype "passive"))
      (node (ref "REF1") (pin "2") (pinfunction "A_2") (pintype "passive"))
      (node (ref "REF1") (pin "3") (pinfunction "A_3") (pintype "passive"))
      (node (ref "RES") (pin "1") (pinfunction "P$1_1") (pintype "bidirectional"))
      (node (ref "RGTG") (pin "2") (pinfunction "P$2_2") (pintype "bidirectional"))
      (node (ref "RGTG") (pin "4") (pinfunction "P$4_4") (pintype "bidirectional"))
      (node (ref "RN1") (pin "A1") (pinfunction "1_A1") (pintype "passive"))
      (node (ref "RN1") (pin "B1") (pinfunction "1_B1") (pintype "passive"))
      (node (ref "RN1") (pin "C1") (pinfunction "1_C1") (pintype "passive"))
      (node (ref "RN1") (pin "D1") (pinfunction "1_D1") (pintype "passive"))
      (node (ref "RN2") (pin "A1") (pinfunction "1_A1") (pintype "passive"))
      (node (ref "RN2") (pin "B1") (pinfunction "1_B1") (pintype "passive"))
      (node (ref "RN2") (pin "C1") (pinfunction "1_C1") (pintype "passive"))
      (node (ref "RN2") (pin "D1") (pinfunction "1_D1") (pintype "passive"))
      (node (ref "T1") (pin "2") (pinfunction "S_2") (pintype "passive"))
      (node (ref "USB1") (pin "GND") (pinfunction "GND_GND") (pintype "power_in"))
      (node (ref "USB1") (pin "GND2") (pinfunction "GND_GND2") (pintype "power_in"))
      (node (ref "X1") (pin "2") (pinfunction "GND_2") (pintype "passive"))
      (node (ref "X1") (pin "4") (pinfunction "GND_4") (pintype "passive"))
      (node (ref "X2") (pin "2") (pinfunction "GND_2") (pintype "passive"))
      (node (ref "X2") (pin "4") (pinfunction "GND_4") (pintype "passive"))
    )
    (net (code "26") (name "I2C0_SCL") (class "Default")
      (node (ref "D17") (pin "1") (pinfunction "1_1") (pintype "bidirectional"))
      (node (ref "DSP") (pin "7") (pinfunction "7_7") (pintype "bidirectional"))
      (node (ref "IC15") (pin "7") (pinfunction "GPIO5_7") (pintype "bidirectional"))
      (node (ref "R130") (pin "2") (pinfunction "2_2") (pintype "passive"))
      (node (ref "SCL0") (pin "TP") (pinfunction "P$1_TP") (pintype "bidirectional"))
    )
    (net (code "27") (name "I2C0_SDA") (class "Default")
      (node (ref "D17") (pin "2") (pinfunction "2_2") (pintype "bidirectional"))
      (node (ref "DSP") (pin "6") (pinfunction "6_6") (pintype "bidirectional"))
      (node (ref "IC15") (pin "6") (pinfunction "GPIO4_6") (pintype "bidirectional"))
      (node (ref "R166") (pin "2") (pinfunction "2_2") (pintype "passive"))
      (node (ref "SDA0") (pin "TP") (pinfunction "P$1_TP") (pintype "bidirectional"))
    )
    (net (code "28") (name "I2C1_SCL") (class "Default")
      (node (ref "D18") (pin "2") (pinfunction "2_2") (pintype "bidirectional"))
      (node (ref "IC15") (pin "5") (pinfunction "GPIO3_5") (pintype "bidirectional"))
      (node (ref "IC19") (pin "6") (pinfunction "SCL_6") (pintype "bidirectional"))
      (node (ref "IC4") (pin "8") (pinfunction "SCL_8") (pintype "bidirectional"))
      (node (ref "R167") (pin "2") (pinfunction "2_2") (pintype "passive"))
      (node (ref "SCL1") (pin "TP") (pinfunction "P$1_TP") (pintype "bidirectional"))
    )
    (net (code "29") (name "I2C1_SDA") (class "Default")
      (node (ref "D18") (pin "1") (pinfunction "1_1") (pintype "bidirectional"))
      (node (ref "IC15") (pin "4") (pinfunction "GPIO2_4") (pintype "bidirectional"))
      (node (ref "IC19") (pin "5") (pinfunction "SDA_5") (pintype "bidirectional"))
      (node (ref "IC4") (pin "9") (pinfunction "SDA_9") (pintype "bidirectional"))
      (node (ref "R168") (pin "2") (pinfunction "2_2") (pintype "passive"))
      (node (ref "SDA1") (pin "TP") (pinfunction "P$1_TP") (pintype "bidirectional"))
    )
    (net (code "30") (name "KEY_0") (class "Default")
      (node (ref "DSP") (pin "12") (pinfunction "12_12") (pintype "bidirectional"))
      (node (ref "IC15") (pin "15") (pinfunction "GPIO12_15") (pintype "bidirectional"))
    )
    (net (code "31") (name "KEY_1") (class "Default")
      (node (ref "DSP") (pin "11") (pinfunction "11_11") (pintype "bidirectional"))
      (node (ref "IC15") (pin "16") (pinfunction "GPIO13_16") (pintype "bidirectional"))
    )
    (net (code "32") (name "KEY_2") (class "Default")
      (node (ref "DSP") (pin "10") (pinfunction "10_10") (pintype "bidirectional"))
      (node (ref "IC15") (pin "17") (pinfunction "GPIO14_17") (pintype "bidirectional"))
    )
    (net (code "33") (name "KEY_3") (class "Default")
      (node (ref "DSP") (pin "9") (pinfunction "9_9") (pintype "bidirectional"))
      (node (ref "IC15") (pin "18") (pinfunction "GPIO15_18") (pintype "bidirectional"))
    )
    (net (code "34") (name "LCD_BL") (class "Default")
      (node (ref "DSP") (pin "13") (pinfunction "13_13") (pintype "bidirectional"))
      (node (ref "IC15") (pin "9") (pinfunction "GPIO7_9") (pintype "bidirectional"))
    )
    (net (code "35") (name "LCD_CS") (class "Default")
      (node (ref "CS") (pin "TP") (pinfunction "P$1_TP") (pintype "bidirectional"))
      (node (ref "DSP") (pin "19") (pinfunction "19_19") (pintype "bidirectional"))
      (node (ref "IC15") (pin "12") (pinfunction "GPIO9_12") (pintype "bidirectional"))
      (node (ref "R149") (pin "C2") (pinfunction "6_C2") (pintype "passive"))
    )
    (net (code "36") (name "LCD_DC") (class "Default")
      (node (ref "DSP") (pin "18") (pinfunction "18_18") (pintype "bidirectional"))
      (node (ref "IC15") (pin "8") (pinfunction "GPIO6_8") (pintype "bidirectional"))
    )
    (net (code "37") (name "LCD_MISO") (class "Default")
      (node (ref "DSP") (pin "15") (pinfunction "15_15") (pintype "bidirectional"))
      (node (ref "IC15") (pin "11") (pinfunction "GPIO8_11") (pintype "bidirectional"))
      (node (ref "MI") (pin "TP") (pinfunction "P$1_TP") (pintype "bidirectional"))
      (node (ref "R149") (pin "B2") (pinfunction "7_B2") (pintype "passive"))
    )
    (net (code "38") (name "LCD_MOSI") (class "Default")
      (node (ref "DSP") (pin "16") (pinfunction "16_16") (pintype "bidirectional"))
      (node (ref "IC15") (pin "14") (pinfunction "GPIO11_14") (pintype "bidirectional"))
      (node (ref "MO") (pin "TP") (pinfunction "P$1_TP") (pintype "bidirectional"))
    )
    (net (code "39") (name "LCD_RES") (class "Default")
      (node (ref "DSP") (pin "14") (pinfunction "14_14") (pintype "bidirectional"))
      (node (ref "R149") (pin "A2") (pinfunction "8_A2") (pintype "passive"))
    )
    (net (code "40") (name "LCD_SCLK") (class "Default")
      (node (ref "DSP") (pin "17") (pinfunction "17_17") (pintype "bidirectional"))
      (node (ref "IC15") (pin "13") (pinfunction "GPIO10_13") (pintype "bidirectional"))
      (node (ref "SC") (pin "TP") (pinfunction "P$1_TP") (pintype "bidirectional"))
    )
    (net (code "41") (name "LREC1") (class "Default")
      (node (ref "C35") (pin "1") (pinfunction "+_1") (pintype "passive"))
      (node (ref "D10") (pin "C") (pinfunction "C_C") (pintype "passive"))
      (node (ref "IC13") (pin "5") (pinfunction "DRAIN_5") (pintype "input"))
      (node (ref "L-REC1") (pin "TP") (pinfunction "P$1_TP") (pintype "bidirectional"))
    )
    (net (code "42") (name "LREC2") (class "Default")
      (node (ref "C47") (pin "1") (pinfunction "+_1") (pintype "passive"))
      (node (ref "D12") (pin "C") (pinfunction "C_C") (pintype "passive"))
      (node (ref "IC5") (pin "5") (pinfunction "DRAIN_5") (pintype "input"))
      (node (ref "L-REC2") (pin "TP") (pinfunction "P$1_TP") (pintype "bidirectional"))
    )
    (net (code "43") (name "MCP_DSP_RST") (class "Default")
      (node (ref "DSP") (pin "20") (pinfunction "20_20") (pintype "bidirectional"))
      (node (ref "IC15") (pin "36") (pinfunction "GPIO24_36") (pintype "bidirectional"))
      (node (ref "R147") (pin "1") (pinfunction "1_1") (pintype "passive"))
    )
    (net (code "44") (name "MCP_REL_RST") (class "Default")
      (node (ref "IC15") (pin "35") (pinfunction "GPIO23_35") (pintype "bidirectional"))
      (node (ref "IC4") (pin "14") (pinfunction "~{RESET}_14") (pintype "bidirectional"))
    )
    (net (code "45") (name "MCP_VIN") (class "Default")
      (node (ref "C102") (pin "1") (pinfunction "1_1") (pintype "passive"))
      (node (ref "C63") (pin "1") (pinfunction "1_1") (pintype "passive"))
      (node (ref "DNI") (pin "2") (pinfunction "2_2") (pintype "passive"))
      (node (ref "IC17") (pin "2") (pinfunction "V+_2") (pintype "power_in"))
      (node (ref "MCPVIN") (pin "TP") (pinfunction "P$1_TP") (pintype "bidirectional"))
      (node (ref "R152") (pin "2") (pinfunction "2_2") (pintype "passive"))
    )
    (net (code "46") (name "MUX_A") (class "Default")
      (node (ref "IC4") (pin "25") (pinfunction "IO2.0_25") (pintype "bidirectional"))
      (node (ref "IC9") (pin "11") (pinfunction "A_11") (pintype "input"))
      (node (ref "R93") (pin "D1") (pinfunction "4_D1") (pintype "passive"))
    )
    (net (code "47") (name "MUX_B") (class "Default")
      (node (ref "IC4") (pin "26") (pinfunction "IO2.1_26") (pintype "bidirectional"))
      (node (ref "IC9") (pin "10") (pinfunction "B_10") (pintype "input"))
      (node (ref "R93") (pin "C1") (pinfunction "3_C1") (pintype "passive"))
    )
    (net (code "48") (name "MUX_C") (class "Default")
      (node (ref "IC4") (pin "27") (pinfunction "IO2.2_27") (pintype "bidirectional"))
      (node (ref "IC9") (pin "9") (pinfunction "C_9") (pintype "input"))
      (node (ref "R93") (pin "B1") (pinfunction "2_B1") (pintype "passive"))
    )
    (net (code "49") (name "MUX_EN") (class "Default")
      (node (ref "IC4") (pin "28") (pinfunction "IO2.3_28") (pintype "bidirectional"))
      (node (ref "IC9") (pin "7") (pinfunction "~{EN}_7") (pintype "input"))
      (node (ref "R93") (pin "A1") (pinfunction "1_A1") (pintype "passive"))
    )
    (net (code "50") (name "N_OUT1") (class "Default")
      (node (ref "N_OUT1") (pin "1") (pinfunction "MOUNT_1") (pintype "passive"))
      (node (ref "N_OUT1") (pin "2") (pinfunction "MOUNT_2") (pintype "passive"))
      (node (ref "R25") (pin "1") (pinfunction "1_1") (pintype "passive"))
      (node (ref "R34") (pin "1") (pinfunction "1_1") (pintype "passive"))
      (node (ref "R35") (pin "1") (pinfunction "1_1") (pintype "passive"))
    )
    (net (code "51") (name "N_OUT2") (class "Default")
      (node (ref "N_OUT2") (pin "1") (pinfunction "MOUNT_1") (pintype "passive"))
      (node (ref "N_OUT2") (pin "2") (pinfunction "MOUNT_2") (pintype "passive"))
      (node (ref "R32") (pin "1") (pinfunction "1_1") (pintype "passive"))
      (node (ref "R50") (pin "1") (pinfunction "1_1") (pintype "passive"))
      (node (ref "R51") (pin "1") (pinfunction "1_1") (pintype "passive"))
    )
    (net (code "52") (name "N_OUT3") (class "Default")
      (node (ref "N_OUT3") (pin "1") (pinfunction "MOUNT_1") (pintype "passive"))
      (node (ref "N_OUT3") (pin "2") (pinfunction "MOUNT_2") (pintype "passive"))
      (node (ref "R31") (pin "1") (pinfunction "1_1") (pintype "passive"))
      (node (ref "R66") (pin "1") (pinfunction "1_1") (pintype "passive"))
      (node (ref "R67") (pin "1") (pinfunction "1_1") (pintype "passive"))
    )
    (net (code "53") (name "N_OUT4") (class "Default")
      (node (ref "N_OUT4") (pin "1") (pinfunction "MOUNT_1") (pintype "passive"))
      (node (ref "N_OUT4") (pin "2") (pinfunction "MOUNT_2") (pintype "passive"))
      (node (ref "R30") (pin "1") (pinfunction "1_1") (pintype "passive"))
      (node (ref "R82") (pin "1") (pinfunction "1_1") (pintype "passive"))
      (node (ref "R83") (pin "1") (pinfunction "1_1") (pintype "passive"))
    )
    (net (code "54") (name "N_OUT5") (class "Default")
      (node (ref "N_OUT5") (pin "1") (pinfunction "MOUNT_1") (pintype "passive"))
      (node (ref "N_OUT5") (pin "2") (pinfunction "MOUNT_2") (pintype "passive"))
      (node (ref "R26") (pin "1") (pinfunction "1_1") (pintype "passive"))
      (node (ref "R42") (pin "1") (pinfunction "1_1") (pintype "passive"))
      (node (ref "R43") (pin "1") (pinfunction "1_1") (pintype "passive"))
    )
    (net (code "55") (name "N_OUT6") (class "Default")
      (node (ref "N_OUT6") (pin "1") (pinfunction "MOUNT_1") (pintype "passive"))
      (node (ref "N_OUT6") (pin "2") (pinfunction "MOUNT_2") (pintype "passive"))
      (node (ref "R27") (pin "1") (pinfunction "1_1") (pintype "passive"))
      (node (ref "R74") (pin "1") (pinfunction "1_1") (pintype "passive"))
      (node (ref "R75") (pin "1") (pinfunction "1_1") (pintype "passive"))
    )
    (net (code "56") (name "N_OUT7") (class "Default")
      (node (ref "N_OUT7") (pin "1") (pinfunction "MOUNT_1") (pintype "passive"))
      (node (ref "N_OUT7") (pin "2") (pinfunction "MOUNT_2") (pintype "passive"))
      (node (ref "R28") (pin "1") (pinfunction "1_1") (pintype "passive"))
      (node (ref "R98") (pin "1") (pinfunction "1_1") (pintype "passive"))
      (node (ref "R99") (pin "1") (pinfunction "1_1") (pintype "passive"))
    )
    (net (code "57") (name "N_OUT8") (class "Default")
      (node (ref "N_OUT8") (pin "1") (pinfunction "MOUNT_1") (pintype "passive"))
      (node (ref "N_OUT8") (pin "2") (pinfunction "MOUNT_2") (pintype "passive"))
      (node (ref "R114") (pin "1") (pinfunction "1_1") (pintype "passive"))
      (node (ref "R115") (pin "1") (pinfunction "1_1") (pintype "passive"))
      (node (ref "R29") (pin "1") (pinfunction "1_1") (pintype "passive"))
    )
    (net (code "58") (name "Net-(3VFB-P$1)") (class "Default")
      (node (ref "3VFB") (pin "TP") (pinfunction "P$1_TP") (pintype "bidirectional"))
      (node (ref "C12") (pin "2") (pinfunction "2_2") (pintype "passive"))
      (node (ref "R10") (pin "2") (pinfunction "2_2") (pintype "passive"))
      (node (ref "R13") (pin "2") (pinfunction "2_2") (pintype "passive"))
      (node (ref "R14") (pin "1") (pinfunction "1_1") (pintype "passive"))
    )
    (net (code "59") (name "Net-(5VFB-P$1)") (class "Default")
      (node (ref "5VFB") (pin "TP") (pinfunction "P$1_TP") (pintype "bidirectional"))
      (node (ref "C11") (pin "2") (pinfunction "2_2") (pintype "passive"))
      (node (ref "R11") (pin "2") (pinfunction "2_2") (pintype "passive"))
      (node (ref "R12") (pin "1") (pinfunction "1_1") (pintype "passive"))
      (node (ref "R8") (pin "2") (pinfunction "2_2") (pintype "passive"))
    )
    (net (code "60") (name "Net-(12VDC-P$1)") (class "Default")
      (node (ref "12VDC") (pin "TP") (pinfunction "P$1_TP") (pintype "bidirectional"))
      (node (ref "AC/DC1") (pin "+V") (pinfunction "+V_+V") (pintype "output"))
      (node (ref "AC/DC2") (pin "+V") (pinfunction "+V_+V") (pintype "output"))
      (node (ref "C10") (pin "1") (pinfunction "+_1") (pintype "passive"))
      (node (ref "C13") (pin "1") (pinfunction "+_1") (pintype "passive"))
      (node (ref "C16") (pin "1") (pinfunction "+_1") (pintype "passive"))
      (node (ref "D16") (pin "C") (pinfunction "C_C") (pintype "passive"))
      (node (ref "J10") (pin "2") (pinfunction "2_2") (pintype "passive"))
      (node (ref "J8") (pin "2") (pinfunction "2_2") (pintype "passive"))
      (node (ref "J9") (pin "2") (pinfunction "2_2") (pintype "passive"))
    )
    (net (code "61") (name "Net-(C8-Pad1)") (class "Default")
      (node (ref "C8") (pin "1") (pinfunction "1_1") (pintype "passive"))
      (node (ref "R7") (pin "1") (pinfunction "1_1") (pintype "passive"))
    )
    (net (code "62") (name "Net-(C9-Pad1)") (class "Default")
      (node (ref "C9") (pin "1") (pinfunction "1_1") (pintype "passive"))
      (node (ref "R9") (pin "1") (pinfunction "1_1") (pintype "passive"))
    )
    (net (code "63") (name "Net-(C106-Pad1)") (class "Default")
      (node (ref "C106") (pin "1") (pinfunction "1_1") (pintype "passive"))
      (node (ref "OPT1") (pin "2") (pinfunction "2_2") (pintype "passive"))
      (node (ref "R59") (pin "2") (pinfunction "2_2") (pintype "passive"))
    )
    (net (code "64") (name "Net-(C107-Pad1)") (class "Default")
      (node (ref "C107") (pin "1") (pinfunction "1_1") (pintype "passive"))
      (node (ref "OPT1") (pin "4") (pinfunction "4_4") (pintype "passive"))
      (node (ref "R153") (pin "2") (pinfunction "2_2") (pintype "passive"))
    )
    (net (code "65") (name "Net-(C108-Pad1)") (class "Default")
      (node (ref "C108") (pin "1") (pinfunction "1_1") (pintype "passive"))
      (node (ref "OPT1") (pin "6") (pinfunction "6_6") (pintype "passive"))
      (node (ref "R154") (pin "2") (pinfunction "2_2") (pintype "passive"))
    )
    (net (code "66") (name "Net-(C109-Pad1)") (class "Default")
      (node (ref "C109") (pin "1") (pinfunction "1_1") (pintype "passive"))
      (node (ref "OPT1") (pin "8") (pinfunction "8_8") (pintype "passive"))
      (node (ref "R155") (pin "2") (pinfunction "2_2") (pintype "passive"))
    )
    (net (code "67") (name "Net-(C110-Pad1)") (class "Default")
      (node (ref "C110") (pin "1") (pinfunction "1_1") (pintype "passive"))
      (node (ref "OPT2") (pin "2") (pinfunction "2_2") (pintype "passive"))
      (node (ref "R156") (pin "2") (pinfunction "2_2") (pintype "passive"))
    )
    (net (code "68") (name "Net-(C111-Pad1)") (class "Default")
      (node (ref "C111") (pin "1") (pinfunction "1_1") (pintype "passive"))
      (node (ref "OPT2") (pin "4") (pinfunction "4_4") (pintype "passive"))
      (node (ref "R157") (pin "2") (pinfunction "2_2") (pintype "passive"))
    )
    (net (code "69") (name "Net-(C112-Pad1)") (class "Default")
      (node (ref "C112") (pin "1") (pinfunction "1_1") (pintype "passive"))
      (node (ref "OPT2") (pin "6") (pinfunction "6_6") (pintype "passive"))
      (node (ref "R158") (pin "2") (pinfunction "2_2") (pintype "passive"))
    )
    (net (code "70") (name "Net-(C113-Pad1)") (class "Default")
      (node (ref "C113") (pin "1") (pinfunction "1_1") (pintype "passive"))
      (node (ref "OPT2") (pin "8") (pinfunction "8_8") (pintype "passive"))
      (node (ref "R159") (pin "2") (pinfunction "2_2") (pintype "passive"))
    )
    (net (code "71") (name "Net-(D10-PadA)") (class "Default")
      (node (ref "D10") (pin "A") (pinfunction "A_A") (pintype "passive"))
      (node (ref "R62") (pin "2") (pinfunction "2_2") (pintype "passive"))
    )
    (net (code "72") (name "Net-(D12-PadA)") (class "Default")
      (node (ref "D12") (pin "A") (pinfunction "A_A") (pintype "passive"))
      (node (ref "R106") (pin "2") (pinfunction "2_2") (pintype "passive"))
    )
    (net (code "73") (name "Net-(DAT-PadA)") (class "Default")
      (node (ref "DAT") (pin "A") (pinfunction "A_A") (pintype "passive"))
      (node (ref "R122") (pin "2") (pinfunction "2_2") (pintype "passive"))
    )
    (net (code "74") (name "Net-(ETH1-GREEN-)") (class "Default")
      (node (ref "ETH1") (pin "9") (pinfunction "GREEN-_9") (pintype "passive"))
      (node (ref "R142") (pin "2") (pinfunction "2_2") (pintype "passive"))
    )
    (net (code "75") (name "Net-(ETH1-YELLOW-)") (class "Default")
      (node (ref "ETH1") (pin "11") (pinfunction "YELLOW-_11") (pintype "passive"))
      (node (ref "R141") (pin "2") (pinfunction "2_2") (pintype "passive"))
    )
    (net (code "76") (name "Net-(IC1-AAM)") (class "Default")
      (node (ref "IC1") (pin "1") (pinfunction "AAM_1") (pintype "bidirectional"))
      (node (ref "R3") (pin "2") (pinfunction "2_2") (pintype "passive"))
      (node (ref "R4") (pin "1") (pinfunction "1_1") (pintype "passive"))
    )
    (net (code "77") (name "Net-(IC1-BST)") (class "Default")
      (node (ref "IC1") (pin "5") (pinfunction "BST_5") (pintype "bidirectional"))
      (node (ref "R7") (pin "2") (pinfunction "2_2") (pintype "passive"))
    )
    (net (code "78") (name "Net-(IC1-FB)") (class "Default")
      (node (ref "IC1") (pin "8") (pinfunction "FB_8") (pintype "bidirectional"))
      (node (ref "R8") (pin "1") (pinfunction "1_1") (pintype "passive"))
    )
    (net (code "79") (name "Net-(IC1-SW)") (class "Default")
      (node (ref "C8") (pin "2") (pinfunction "2_2") (pintype "passive"))
      (node (ref "IC1") (pin "3") (pinfunction "SW_3") (pintype "bidirectional"))
      (node (ref "L1") (pin "1") (pinfunction "1_1") (pintype "passive"))
      (node (ref "SW") (pin "TP") (pinfunction "P$1_TP") (pintype "bidirectional"))
    )
    (net (code "80") (name "Net-(IC1-VCC)") (class "Default")
      (node (ref "C6") (pin "1") (pinfunction "1_1") (pintype "passive"))
      (node (ref "IC1") (pin "7") (pinfunction "VCC_7") (pintype "bidirectional"))
      (node (ref "R3") (pin "1") (pinfunction "1_1") (pintype "passive"))
    )
    (net (code "81") (name "Net-(IC2-AAM)") (class "Default")
      (node (ref "IC2") (pin "1") (pinfunction "AAM_1") (pintype "bidirectional"))
      (node (ref "R5") (pin "2") (pinfunction "2_2") (pintype "passive"))
      (node (ref "R6") (pin "1") (pinfunction "1_1") (pintype "passive"))
    )
    (net (code "82") (name "Net-(IC2-BST)") (class "Default")
      (node (ref "IC2") (pin "5") (pinfunction "BST_5") (pintype "bidirectional"))
      (node (ref "R9") (pin "2") (pinfunction "2_2") (pintype "passive"))
    )
    (net (code "83") (name "Net-(IC2-EN)") (class "Default")
      (node (ref "IC2") (pin "6") (pinfunction "EN_6") (pintype "bidirectional"))
      (node (ref "R171") (pin "1") (pinfunction "1_1") (pintype "passive"))
      (node (ref "R172") (pin "1") (pinfunction "1_1") (pintype "passive"))
      (node (ref "R2") (pin "2") (pinfunction "2_2") (pintype "passive"))
    )
    (net (code "84") (name "Net-(IC2-FB)") (class "Default")
      (node (ref "IC2") (pin "8") (pinfunction "FB_8") (pintype "bidirectional"))
      (node (ref "R10") (pin "1") (pinfunction "1_1") (pintype "passive"))
    )
    (net (code "85") (name "Net-(IC2-SW)") (class "Default")
      (node (ref "C9") (pin "2") (pinfunction "2_2") (pintype "passive"))
      (node (ref "IC2") (pin "3") (pinfunction "SW_3") (pintype "bidirectional"))
      (node (ref "L2") (pin "1") (pinfunction "1_1") (pintype "passive"))
      (node (ref "SW3") (pin "TP") (pinfunction "P$1_TP") (pintype "bidirectional"))
    )
    (net (code "86") (name "Net-(IC2-VCC)") (class "Default")
      (node (ref "C7") (pin "1") (pinfunction "1_1") (pintype "passive"))
      (node (ref "IC2") (pin "7") (pinfunction "VCC_7") (pintype "bidirectional"))
      (node (ref "R5") (pin "1") (pinfunction "1_1") (pintype "passive"))
    )
    (net (code "87") (name "Net-(IC3-1C)") (class "Default")
      (node (ref "IC3") (pin "18") (pinfunction "1C_18") (pintype "bidirectional"))
      (node (ref "R17") (pin "1") (pinfunction "1_1") (pintype "passive"))
    )
    (net (code "88") (name "Net-(IC3-2C)") (class "Default")
      (node (ref "IC3") (pin "17") (pinfunction "2C_17") (pintype "bidirectional"))
      (node (ref "R18") (pin "1") (pinfunction "1_1") (pintype "passive"))
    )
    (net (code "89") (name "Net-(IC3-3C)") (class "Default")
      (node (ref "IC3") (pin "16") (pinfunction "3C_16") (pintype "bidirectional"))
      (node (ref "R19") (pin "1") (pinfunction "1_1") (pintype "passive"))
    )
    (net (code "90") (name "Net-(IC3-4C)") (class "Default")
      (node (ref "IC3") (pin "15") (pinfunction "4C_15") (pintype "bidirectional"))
      (node (ref "R20") (pin "1") (pinfunction "1_1") (pintype "passive"))
    )
    (net (code "91") (name "Net-(IC3-5C)") (class "Default")
      (node (ref "IC3") (pin "14") (pinfunction "5C_14") (pintype "bidirectional"))
      (node (ref "R21") (pin "1") (pinfunction "1_1") (pintype "passive"))
    )
    (net (code "92") (name "Net-(IC3-6C)") (class "Default")
      (node (ref "IC3") (pin "13") (pinfunction "6C_13") (pintype "bidirectional"))
      (node (ref "R22") (pin "1") (pinfunction "1_1") (pintype "passive"))
    )
    (net (code "93") (name "Net-(IC3-7C)") (class "Default")
      (node (ref "IC3") (pin "12") (pinfunction "7C_12") (pintype "bidirectional"))
      (node (ref "R23") (pin "1") (pinfunction "1_1") (pintype "passive"))
    )
    (net (code "94") (name "Net-(IC3-8C)") (class "Default")
      (node (ref "IC3") (pin "11") (pinfunction "8C_11") (pintype "bidirectional"))
      (node (ref "R24") (pin "1") (pinfunction "1_1") (pintype "passive"))
    )
    (net (code "95") (name "Net-(IC6-INN)") (class "Default")
      (node (ref "C25") (pin "1") (pinfunction "1_1") (pintype "passive"))
      (node (ref "IC6") (pin "3") (pinfunction "INN_3") (pintype "input"))
      (node (ref "R34") (pin "2") (pinfunction "2_2") (pintype "passive"))
    )
    (net (code "96") (name "Net-(IC6-INP)") (class "Default")
      (node (ref "C24") (pin "1") (pinfunction "1_1") (pintype "passive"))
      (node (ref "IC6") (pin "2") (pinfunction "INP_2") (pintype "input"))
      (node (ref "R33") (pin "2") (pinfunction "2_2") (pintype "passive"))
    )
    (net (code "97") (name "Net-(IC6-VP)") (class "Default")
      (node (ref "C26") (pin "1") (pinfunction "1_1") (pintype "passive"))
      (node (ref "IC6") (pin "4") (pinfunction "VP_4") (pintype "input"))
      (node (ref "R39") (pin "2") (pinfunction "2_2") (pintype "passive"))
      (node (ref "R40") (pin "1") (pinfunction "1_1") (pintype "passive"))
    )
    (net (code "98") (name "Net-(IC7-INN)") (class "Default")
      (node (ref "C28") (pin "1") (pinfunction "1_1") (pintype "passive"))
      (node (ref "IC7") (pin "3") (pinfunction "INN_3") (pintype "input"))
      (node (ref "R42") (pin "2") (pinfunction "2_2") (pintype "passive"))
    )
    (net (code "99") (name "Net-(IC7-INP)") (class "Default")
      (node (ref "C27") (pin "1") (pinfunction "1_1") (pintype "passive"))
      (node (ref "IC7") (pin "2") (pinfunction "INP_2") (pintype "input"))
      (node (ref "R41") (pin "2") (pinfunction "2_2") (pintype "passive"))
    )
    (net (code "100") (name "Net-(IC7-VP)") (class "Default")
      (node (ref "C29") (pin "1") (pinfunction "1_1") (pintype "passive"))
      (node (ref "IC7") (pin "4") (pinfunction "VP_4") (pintype "input"))
      (node (ref "R47") (pin "2") (pinfunction "2_2") (pintype "passive"))
      (node (ref "R48") (pin "1") (pinfunction "1_1") (pintype "passive"))
    )
    (net (code "101") (name "Net-(IC8-INN)") (class "Default")
      (node (ref "C31") (pin "1") (pinfunction "1_1") (pintype "passive"))
      (node (ref "IC8") (pin "3") (pinfunction "INN_3") (pintype "input"))
      (node (ref "R50") (pin "2") (pinfunction "2_2") (pintype "passive"))
    )
    (net (code "102") (name "Net-(IC8-INP)") (class "Default")
      (node (ref "C30") (pin "1") (pinfunction "1_1") (pintype "passive"))
      (node (ref "IC8") (pin "2") (pinfunction "INP_2") (pintype "input"))
      (node (ref "R49") (pin "2") (pinfunction "2_2") (pintype "passive"))
    )
    (net (code "103") (name "Net-(IC8-VP)") (class "Default")
      (node (ref "C32") (pin "1") (pinfunction "1_1") (pintype "passive"))
      (node (ref "IC8") (pin "4") (pinfunction "VP_4") (pintype "input"))
      (node (ref "R55") (pin "2") (pinfunction "2_2") (pintype "passive"))
      (node (ref "R56") (pin "1") (pinfunction "1_1") (pintype "passive"))
    )
    (net (code "104") (name "Net-(IC10-INN)") (class "Default")
      (node (ref "C37") (pin "1") (pinfunction "1_1") (pintype "passive"))
      (node (ref "IC10") (pin "3") (pinfunction "INN_3") (pintype "input"))
      (node (ref "R66") (pin "2") (pinfunction "2_2") (pintype "passive"))
    )
    (net (code "105") (name "Net-(IC10-INP)") (class "Default")
      (node (ref "C36") (pin "1") (pinfunction "1_1") (pintype "passive"))
      (node (ref "IC10") (pin "2") (pinfunction "INP_2") (pintype "input"))
      (node (ref "R65") (pin "2") (pinfunction "2_2") (pintype "passive"))
    )
    (net (code "106") (name "Net-(IC10-VP)") (class "Default")
      (node (ref "C38") (pin "1") (pinfunction "1_1") (pintype "passive"))
      (node (ref "IC10") (pin "4") (pinfunction "VP_4") (pintype "input"))
      (node (ref "R71") (pin "2") (pinfunction "2_2") (pintype "passive"))
      (node (ref "R72") (pin "1") (pinfunction "1_1") (pintype "passive"))
    )
    (net (code "107") (name "Net-(IC11-INN)") (class "Default")
      (node (ref "C40") (pin "1") (pinfunction "1_1") (pintype "passive"))
      (node (ref "IC11") (pin "3") (pinfunction "INN_3") (pintype "input"))
      (node (ref "R74") (pin "2") (pinfunction "2_2") (pintype "passive"))
    )
    (net (code "108") (name "Net-(IC11-INP)") (class "Default")
      (node (ref "C39") (pin "1") (pinfunction "1_1") (pintype "passive"))
      (node (ref "IC11") (pin "2") (pinfunction "INP_2") (pintype "input"))
      (node (ref "R73") (pin "2") (pinfunction "2_2") (pintype "passive"))
    )
    (net (code "109") (name "Net-(IC11-VP)") (class "Default")
      (node (ref "C41") (pin "1") (pinfunction "1_1") (pintype "passive"))
      (node (ref "IC11") (pin "4") (pinfunction "VP_4") (pintype "input"))
      (node (ref "R79") (pin "2") (pinfunction "2_2") (pintype "passive"))
      (node (ref "R80") (pin "1") (pinfunction "1_1") (pintype "passive"))
    )
    (net (code "110") (name "Net-(IC12-INN)") (class "Default")
      (node (ref "C43") (pin "1") (pinfunction "1_1") (pintype "passive"))
      (node (ref "IC12") (pin "3") (pinfunction "INN_3") (pintype "input"))
      (node (ref "R82") (pin "2") (pinfunction "2_2") (pintype "passive"))
    )
    (net (code "111") (name "Net-(IC12-INP)") (class "Default")
      (node (ref "C42") (pin "1") (pinfunction "1_1") (pintype "passive"))
      (node (ref "IC12") (pin "2") (pinfunction "INP_2") (pintype "input"))
      (node (ref "R81") (pin "2") (pinfunction "2_2") (pintype "passive"))
    )
    (net (code "112") (name "Net-(IC12-VP)") (class "Default")
      (node (ref "C44") (pin "1") (pinfunction "1_1") (pintype "passive"))
      (node (ref "IC12") (pin "4") (pinfunction "VP_4") (pintype "input"))
      (node (ref "R87") (pin "2") (pinfunction "2_2") (pintype "passive"))
      (node (ref "R88") (pin "1") (pinfunction "1_1") (pintype "passive"))
    )
    (net (code "113") (name "Net-(IC14-INN)") (class "Default")
      (node (ref "C49") (pin "1") (pinfunction "1_1") (pintype "passive"))
      (node (ref "IC14") (pin "3") (pinfunction "INN_3") (pintype "input"))
      (node (ref "R98") (pin "2") (pinfunction "2_2") (pintype "passive"))
    )
    (net (code "114") (name "Net-(IC14-INP)") (class "Default")
      (node (ref "C48") (pin "1") (pinfunction "1_1") (pintype "passive"))
      (node (ref "IC14") (pin "2") (pinfunction "INP_2") (pintype "input"))
      (node (ref "R97") (pin "2") (pinfunction "2_2") (pintype "passive"))
    )
    (net (code "115") (name "Net-(IC14-VP)") (class "Default")
      (node (ref "C50") (pin "1") (pinfunction "1_1") (pintype "passive"))
      (node (ref "IC14") (pin "4") (pinfunction "VP_4") (pintype "input"))
      (node (ref "R103") (pin "2") (pinfunction "2_2") (pintype "passive"))
      (node (ref "R104") (pin "1") (pinfunction "1_1") (pintype "passive"))
    )
    (net (code "116") (name "Net-(IC15-GPIO28{slash}ADC2)") (class "Default")
      (node (ref "IC15") (pin "40") (pinfunction "GPIO28/ADC2_40") (pintype "bidirectional"))
      (node (ref "R163") (pin "2") (pinfunction "2_2") (pintype "passive"))
    )
    (net (code "117") (name "Net-(IC15-USB_DM)") (class "Default")
      (node (ref "IC15") (pin "46") (pinfunction "USB_DM_46") (pintype "bidirectional"))
      (node (ref "R15") (pin "2") (pinfunction "2_2") (pintype "passive"))
    )
    (net (code "118") (name "Net-(IC15-USB_DP)") (class "Default")
      (node (ref "IC15") (pin "47") (pinfunction "USB_DP_47") (pintype "bidirectional"))
      (node (ref "R160") (pin "2") (pinfunction "2_2") (pintype "passive"))
    )
    (net (code "119") (name "Net-(IC16-INN)") (class "Default")
      (node (ref "C55") (pin "1") (pinfunction "1_1") (pintype "passive"))
      (node (ref "IC16") (pin "3") (pinfunction "INN_3") (pintype "input"))
      (node (ref "R114") (pin "2") (pinfunction "2_2") (pintype "passive"))
    )
    (net (code "120") (name "Net-(IC16-INP)") (class "Default")
      (node (ref "C54") (pin "1") (pinfunction "1_1") (pintype "passive"))
      (node (ref "IC16") (pin "2") (pinfunction "INP_2") (pintype "input"))
      (node (ref "R113") (pin "2") (pinfunction "2_2") (pintype "passive"))
    )
    (net (code "121") (name "Net-(IC16-VP)") (class "Default")
      (node (ref "C56") (pin "1") (pinfunction "1_1") (pintype "passive"))
      (node (ref "IC16") (pin "4") (pinfunction "VP_4") (pintype "input"))
      (node (ref "R119") (pin "2") (pinfunction "2_2") (pintype "passive"))
      (node (ref "R120") (pin "1") (pinfunction "1_1") (pintype "passive"))
    )
    (net (code "122") (name "Net-(IC17-+IN)") (class "Default")
      (node (ref "C60") (pin "1") (pinfunction "1_1") (pintype "passive"))
      (node (ref "C61") (pin "1") (pinfunction "1_1") (pintype "passive"))
      (node (ref "IC17") (pin "3") (pinfunction "+IN_3") (pintype "input"))
      (node (ref "R109") (pin "1") (pinfunction "1_1") (pintype "passive"))
      (node (ref "REF1") (pin "1") (pinfunction "C_1") (pintype "passive"))
      (node (ref "VREF") (pin "TP") (pinfunction "P$1_TP") (pintype "bidirectional"))
    )
    (net (code "123") (name "Net-(IC19-A0)") (class "Default")
      (node (ref "IC19") (pin "1") (pinfunction "A0_1") (pintype "bidirectional"))
      (node (ref "R128") (pin "1") (pinfunction "1_1") (pintype "passive"))
      (node (ref "R129") (pin "2") (pinfunction "2_2") (pintype "passive"))
    )
    (net (code "124") (name "Net-(IC20-1V2O)") (class "Default")
      (node (ref "C84") (pin "1") (pinfunction "1_1") (pintype "passive"))
      (node (ref "IC20") (pin "22") (pinfunction "1V2O_22") (pintype "output"))
    )
    (net (code "125") (name "Net-(IC20-EXRES1)") (class "Default")
      (node (ref "IC20") (pin "10") (pinfunction "EXRES1_10") (pintype "bidirectional"))
      (node (ref "R143") (pin "2") (pinfunction "2_2") (pintype "passive"))
    )
    (net (code "126") (name "Net-(IC20-TOCAP)") (class "Default")
      (node (ref "C85") (pin "1") (pinfunction "1_1") (pintype "passive"))
      (node (ref "IC20") (pin "20") (pinfunction "TOCAP_20") (pintype "output"))
    )
    (net (code "127") (name "Net-(IC20-XI)") (class "Default")
      (node (ref "C87") (pin "1") (pinfunction "1_1") (pintype "passive"))
      (node (ref "IC20") (pin "30") (pinfunction "XI_30") (pintype "input"))
      (node (ref "R144") (pin "1") (pinfunction "1_1") (pintype "passive"))
      (node (ref "X2") (pin "3") (pinfunction "2_3") (pintype "passive"))
    )
    (net (code "128") (name "Net-(IC20-XO)") (class "Default")
      (node (ref "C86") (pin "1") (pinfunction "1_1") (pintype "passive"))
      (node (ref "IC20") (pin "31") (pinfunction "XO_31") (pintype "output"))
      (node (ref "R144") (pin "2") (pinfunction "2_2") (pintype "passive"))
      (node (ref "X2") (pin "1") (pinfunction "1_1") (pintype "passive"))
    )
    (net (code "129") (name "Net-(IC22--IN)") (class "Default")
      (node (ref "IC22") (pin "1") (pinfunction "OUT_1") (pintype "output"))
      (node (ref "IC22") (pin "4") (pinfunction "-IN_4") (pintype "input"))
      (node (ref "R122") (pin "1") (pinfunction "1_1") (pintype "passive"))
    )
    (net (code "130") (name "Net-(P3ON-PadA)") (class "Default")
      (node (ref "P3ON") (pin "A") (pinfunction "A_A") (pintype "passive"))
      (node (ref "R123") (pin "2") (pinfunction "2_2") (pintype "passive"))
    )
    (net (code "131") (name "Net-(P5ON-PadA)") (class "Default")
      (node (ref "P5ON") (pin "A") (pinfunction "A_A") (pintype "passive"))
      (node (ref "R148") (pin "2") (pinfunction "2_2") (pintype "passive"))
    )
    (net (code "132") (name "Net-(P12ON-PadA)") (class "Default")
      (node (ref "P12ON") (pin "A") (pinfunction "A_A") (pintype "passive"))
      (node (ref "R150") (pin "2") (pinfunction "2_2") (pintype "passive"))
    )
    (net (code "133") (name "Net-(PROC-PadA)") (class "Default")
      (node (ref "PROC") (pin "A") (pinfunction "A_A") (pintype "passive"))
      (node (ref "R163") (pin "1") (pinfunction "1_1") (pintype "passive"))
    )
    (net (code "134") (name "Net-(PWR-PadC)") (class "Default")
      (node (ref "PWR") (pin "C") (pinfunction "C_C") (pintype "passive"))
      (node (ref "R151") (pin "2") (pinfunction "2_2") (pintype "passive"))
    )
    (net (code "135") (name "Net-(R36-Pad1)") (class "Default")
      (node (ref "R36") (pin "1") (pinfunction "1_1") (pintype "passive"))
      (node (ref "R37") (pin "2") (pinfunction "2_2") (pintype "passive"))
    )
    (net (code "136") (name "Net-(R37-Pad1)") (class "Default")
      (node (ref "R37") (pin "1") (pinfunction "1_1") (pintype "passive"))
      (node (ref "R38") (pin "1") (pinfunction "1_1") (pintype "passive"))
    )
    (net (code "137") (name "Net-(R38-Pad2)") (class "Default")
      (node (ref "R38") (pin "2") (pinfunction "2_2") (pintype "passive"))
      (node (ref "R39") (pin "1") (pinfunction "1_1") (pintype "passive"))
    )
    (net (code "138") (name "Net-(R44-Pad2)") (class "Default")
      (node (ref "R44") (pin "2") (pinfunction "2_2") (pintype "passive"))
      (node (ref "R45") (pin "2") (pinfunction "2_2") (pintype "passive"))
    )
    (net (code "139") (name "Net-(R45-Pad1)") (class "Default")
      (node (ref "R45") (pin "1") (pinfunction "1_1") (pintype "passive"))
      (node (ref "R46") (pin "1") (pinfunction "1_1") (pintype "passive"))
    )
    (net (code "140") (name "Net-(R46-Pad2)") (class "Default")
      (node (ref "R46") (pin "2") (pinfunction "2_2") (pintype "passive"))
      (node (ref "R47") (pin "1") (pinfunction "1_1") (pintype "passive"))
    )
    (net (code "141") (name "Net-(R52-Pad2)") (class "Default")
      (node (ref "R52") (pin "2") (pinfunction "2_2") (pintype "passive"))
      (node (ref "R53") (pin "2") (pinfunction "2_2") (pintype "passive"))
    )
    (net (code "142") (name "Net-(R53-Pad1)") (class "Default")
      (node (ref "R53") (pin "1") (pinfunction "1_1") (pintype "passive"))
      (node (ref "R54") (pin "1") (pinfunction "1_1") (pintype "passive"))
    )
    (net (code "143") (name "Net-(R54-Pad2)") (class "Default")
      (node (ref "R54") (pin "2") (pinfunction "2_2") (pintype "passive"))
      (node (ref "R55") (pin "1") (pinfunction "1_1") (pintype "passive"))
    )
    (net (code "144") (name "Net-(R63-5)") (class "Default")
      (node (ref "OPT1") (pin "7") (pinfunction "7_7") (pintype "passive"))
      (node (ref "R63") (pin "D2") (pinfunction "5_D2") (pintype "passive"))
    )
    (net (code "145") (name "Net-(R63-6)") (class "Default")
      (node (ref "OPT1") (pin "5") (pinfunction "5_5") (pintype "passive"))
      (node (ref "R63") (pin "C2") (pinfunction "6_C2") (pintype "passive"))
    )
    (net (code "146") (name "Net-(R63-7)") (class "Default")
      (node (ref "OPT1") (pin "3") (pinfunction "3_3") (pintype "passive"))
      (node (ref "R63") (pin "B2") (pinfunction "7_B2") (pintype "passive"))
    )
    (net (code "147") (name "Net-(R63-8)") (class "Default")
      (node (ref "OPT1") (pin "1") (pinfunction "1_1") (pintype "passive"))
      (node (ref "R63") (pin "A2") (pinfunction "8_A2") (pintype "passive"))
    )
    (net (code "148") (name "Net-(R64-5)") (class "Default")
      (node (ref "OPT2") (pin "7") (pinfunction "7_7") (pintype "passive"))
      (node (ref "R64") (pin "D2") (pinfunction "5_D2") (pintype "passive"))
    )
    (net (code "149") (name "Net-(R64-6)") (class "Default")
      (node (ref "OPT2") (pin "5") (pinfunction "5_5") (pintype "passive"))
      (node (ref "R64") (pin "C2") (pinfunction "6_C2") (pintype "passive"))
    )
    (net (code "150") (name "Net-(R64-7)") (class "Default")
      (node (ref "OPT2") (pin "3") (pinfunction "3_3") (pintype "passive"))
      (node (ref "R64") (pin "B2") (pinfunction "7_B2") (pintype "passive"))
    )
    (net (code "151") (name "Net-(R64-8)") (class "Default")
      (node (ref "OPT2") (pin "1") (pinfunction "1_1") (pintype "passive"))
      (node (ref "R64") (pin "A2") (pinfunction "8_A2") (pintype "passive"))
    )
    (net (code "152") (name "Net-(R68-Pad2)") (class "Default")
      (node (ref "R68") (pin "2") (pinfunction "2_2") (pintype "passive"))
      (node (ref "R69") (pin "2") (pinfunction "2_2") (pintype "passive"))
    )
    (net (code "153") (name "Net-(R69-Pad1)") (class "Default")
      (node (ref "R69") (pin "1") (pinfunction "1_1") (pintype "passive"))
      (node (ref "R70") (pin "1") (pinfunction "1_1") (pintype "passive"))
    )
    (net (code "154") (name "Net-(R70-Pad2)") (class "Default")
      (node (ref "R70") (pin "2") (pinfunction "2_2") (pintype "passive"))
      (node (ref "R71") (pin "1") (pinfunction "1_1") (pintype "passive"))
    )
    (net (code "155") (name "Net-(R76-Pad2)") (class "Default")
      (node (ref "R76") (pin "2") (pinfunction "2_2") (pintype "passive"))
      (node (ref "R77") (pin "2") (pinfunction "2_2") (pintype "passive"))
    )
    (net (code "156") (name "Net-(R77-Pad1)") (class "Default")
      (node (ref "R77") (pin "1") (pinfunction "1_1") (pintype "passive"))
      (node (ref "R78") (pin "1") (pinfunction "1_1") (pintype "passive"))
    )
    (net (code "157") (name "Net-(R78-Pad2)") (class "Default")
      (node (ref "R78") (pin "2") (pinfunction "2_2") (pintype "passive"))
      (node (ref "R79") (pin "1") (pinfunction "1_1") (pintype "passive"))
    )
    (net (code "158") (name "Net-(R84-Pad2)") (class "Default")
      (node (ref "R84") (pin "2") (pinfunction "2_2") (pintype "passive"))
      (node (ref "R85") (pin "2") (pinfunction "2_2") (pintype "passive"))
    )
    (net (code "159") (name "Net-(R85-Pad1)") (class "Default")
      (node (ref "R85") (pin "1") (pinfunction "1_1") (pintype "passive"))
      (node (ref "R86") (pin "1") (pinfunction "1_1") (pintype "passive"))
    )
    (net (code "160") (name "Net-(R86-Pad2)") (class "Default")
      (node (ref "R86") (pin "2") (pinfunction "2_2") (pintype "passive"))
      (node (ref "R87") (pin "1") (pinfunction "1_1") (pintype "passive"))
    )
    (net (code "161") (name "Net-(R100-Pad2)") (class "Default")
      (node (ref "R100") (pin "2") (pinfunction "2_2") (pintype "passive"))
      (node (ref "R101") (pin "2") (pinfunction "2_2") (pintype "passive"))
    )
    (net (code "162") (name "Net-(R101-Pad1)") (class "Default")
      (node (ref "R101") (pin "1") (pinfunction "1_1") (pintype "passive"))
      (node (ref "R102") (pin "1") (pinfunction "1_1") (pintype "passive"))
    )
    (net (code "163") (name "Net-(R102-Pad2)") (class "Default")
      (node (ref "R102") (pin "2") (pinfunction "2_2") (pintype "passive"))
      (node (ref "R103") (pin "1") (pinfunction "1_1") (pintype "passive"))
    )
    (net (code "164") (name "Net-(R116-Pad2)") (class "Default")
      (node (ref "R116") (pin "2") (pinfunction "2_2") (pintype "passive"))
      (node (ref "R117") (pin "2") (pinfunction "2_2") (pintype "passive"))
    )
    (net (code "165") (name "Net-(R117-Pad1)") (class "Default")
      (node (ref "R117") (pin "1") (pinfunction "1_1") (pintype "passive"))
      (node (ref "R118") (pin "1") (pinfunction "1_1") (pintype "passive"))
    )
    (net (code "166") (name "Net-(R118-Pad2)") (class "Default")
      (node (ref "R118") (pin "2") (pinfunction "2_2") (pintype "passive"))
      (node (ref "R119") (pin "1") (pinfunction "1_1") (pintype "passive"))
    )
    (net (code "167") (name "Net-(T1-D)") (class "Default")
      (node (ref "FAN") (pin "1") (pinfunction "1_1") (pintype "passive"))
      (node (ref "T1") (pin "3") (pinfunction "D_3") (pintype "passive"))
    )
    (net (code "168") (name "Net-(UTX-P$1)") (class "Default")
      (node (ref "R57") (pin "1") (pinfunction "1_1") (pintype "passive"))
      (node (ref "R58") (pin "1") (pinfunction "1_1") (pintype "passive"))
      (node (ref "R91") (pin "2") (pinfunction "2_2") (pintype "passive"))
      (node (ref "R92") (pin "2") (pinfunction "2_2") (pintype "passive"))
      (node (ref "UTX") (pin "TP") (pinfunction "P$1_TP") (pintype "bidirectional"))
    )
    (net (code "169") (name "Net-(X1-2)") (class "Default")
      (node (ref "C59") (pin "1") (pinfunction "1_1") (pintype "passive"))
      (node (ref "R16") (pin "1") (pinfunction "1_1") (pintype "passive"))
      (node (ref "X1") (pin "3") (pinfunction "2_3") (pintype "passive"))
    )
    (net (code "170") (name "OUT_1") (class "Default")
      (node (ref "K1") (pin "4") (pinfunction "4_4") (pintype "passive"))
      (node (ref "K1") (pin "5") (pinfunction "5_5") (pintype "passive"))
      (node (ref "L_OUT1") (pin "1") (pinfunction "MOUNT_1") (pintype "passive"))
      (node (ref "L_OUT1") (pin "2") (pinfunction "MOUNT_2") (pintype "passive"))
      (node (ref "R36") (pin "2") (pinfunction "2_2") (pintype "passive"))
    )
    (net (code "171") (name "OUT_2") (class "Default")
      (node (ref "K2") (pin "4") (pinfunction "4_4") (pintype "passive"))
      (node (ref "K2") (pin "5") (pinfunction "5_5") (pintype "passive"))
      (node (ref "L_OUT2") (pin "1") (pinfunction "MOUNT_1") (pintype "passive"))
      (node (ref "L_OUT2") (pin "2") (pinfunction "MOUNT_2") (pintype "passive"))
      (node (ref "R52") (pin "1") (pinfunction "1_1") (pintype "passive"))
    )
    (net (code "172") (name "OUT_3") (class "Default")
      (node (ref "K3") (pin "4") (pinfunction "4_4") (pintype "passive"))
      (node (ref "K3") (pin "5") (pinfunction "5_5") (pintype "passive"))
      (node (ref "L_OUT3") (pin "1") (pinfunction "MOUNT_1") (pintype "passive"))
      (node (ref "L_OUT3") (pin "2") (pinfunction "MOUNT_2") (pintype "passive"))
      (node (ref "R68") (pin "1") (pinfunction "1_1") (pintype "passive"))
    )
    (net (code "173") (name "OUT_4") (class "Default")
      (node (ref "K4") (pin "4") (pinfunction "4_4") (pintype "passive"))
      (node (ref "K4") (pin "5") (pinfunction "5_5") (pintype "passive"))
      (node (ref "L_OUT4") (pin "1") (pinfunction "MOUNT_1") (pintype "passive"))
      (node (ref "L_OUT4") (pin "2") (pinfunction "MOUNT_2") (pintype "passive"))
      (node (ref "R84") (pin "1") (pinfunction "1_1") (pintype "passive"))
    )
    (net (code "174") (name "OUT_5") (class "Default")
      (node (ref "K5") (pin "4") (pinfunction "4_4") (pintype "passive"))
      (node (ref "K5") (pin "5") (pinfunction "5_5") (pintype "passive"))
      (node (ref "L_OUT5") (pin "1") (pinfunction "MOUNT_1") (pintype "passive"))
      (node (ref "L_OUT5") (pin "2") (pinfunction "MOUNT_2") (pintype "passive"))
      (node (ref "R44") (pin "1") (pinfunction "1_1") (pintype "passive"))
    )
    (net (code "175") (name "OUT_6") (class "Default")
      (node (ref "K6") (pin "4") (pinfunction "4_4") (pintype "passive"))
      (node (ref "K6") (pin "5") (pinfunction "5_5") (pintype "passive"))
      (node (ref "L_OUT6") (pin "1") (pinfunction "MOUNT_1") (pintype "passive"))
      (node (ref "L_OUT6") (pin "2") (pinfunction "MOUNT_2") (pintype "passive"))
      (node (ref "R76") (pin "1") (pinfunction "1_1") (pintype "passive"))
    )
    (net (code "176") (name "OUT_7") (class "Default")
      (node (ref "K7") (pin "4") (pinfunction "4_4") (pintype "passive"))
      (node (ref "K7") (pin "5") (pinfunction "5_5") (pintype "passive"))
      (node (ref "L_OUT7") (pin "1") (pinfunction "MOUNT_1") (pintype "passive"))
      (node (ref "L_OUT7") (pin "2") (pinfunction "MOUNT_2") (pintype "passive"))
      (node (ref "R100") (pin "1") (pinfunction "1_1") (pintype "passive"))
    )
    (net (code "177") (name "OUT_8") (class "Default")
      (node (ref "K8") (pin "4") (pinfunction "4_4") (pintype "passive"))
      (node (ref "K8") (pin "5") (pinfunction "5_5") (pintype "passive"))
      (node (ref "L_OUT8") (pin "1") (pinfunction "MOUNT_1") (pintype "passive"))
      (node (ref "L_OUT8") (pin "2") (pinfunction "MOUNT_2") (pintype "passive"))
      (node (ref "R116") (pin "1") (pinfunction "1_1") (pintype "passive"))
    )
    (net (code "178") (name "QSPI_SCLK") (class "Default")
      (node (ref "IC15") (pin "52") (pinfunction "QSPI_SCLK_52") (pintype "bidirectional"))
      (node (ref "IC18") (pin "6") (pinfunction "CLK_6") (pintype "bidirectional"))
    )
    (net (code "179") (name "QSPI_SD0") (class "Default")
      (node (ref "IC15") (pin "53") (pinfunction "QSPI_SD0_53") (pintype "bidirectional"))
      (node (ref "IC18") (pin "5") (pinfunction "DI/IO0_5") (pintype "bidirectional"))
    )
    (net (code "180") (name "QSPI_SD1") (class "Default")
      (node (ref "IC15") (pin "55") (pinfunction "QSPI_SD1_55") (pintype "bidirectional"))
      (node (ref "IC18") (pin "2") (pinfunction "DO/IO1_2") (pintype "bidirectional"))
    )
    (net (code "181") (name "QSPI_SD2") (class "Default")
      (node (ref "IC15") (pin "54") (pinfunction "QSPI_SD2_54") (pintype "bidirectional"))
      (node (ref "IC18") (pin "3") (pinfunction "~{WP}/IO2_3") (pintype "bidirectional"))
    )
    (net (code "182") (name "QSPI_SD3") (class "Default")
      (node (ref "IC15") (pin "51") (pinfunction "QSPI_SD3_51") (pintype "bidirectional"))
      (node (ref "IC18") (pin "7") (pinfunction "~{HOLD}/IO3_7") (pintype "bidirectional"))
    )
    (net (code "183") (name "RCT") (class "Default")
      (node (ref "C79") (pin "1") (pinfunction "1_1") (pintype "passive"))
      (node (ref "ETH1") (pin "5") (pinfunction "P5/RCT_5") (pintype "passive"))
      (node (ref "R137") (pin "1") (pinfunction "1_1") (pintype "passive"))
      (node (ref "R138") (pin "1") (pinfunction "1_1") (pintype "passive"))
    )
    (net (code "184") (name "RDC_RD_N") (class "Default")
      (node (ref "C81") (pin "1") (pinfunction "1_1") (pintype "passive"))
      (node (ref "R136") (pin "2") (pinfunction "2_2") (pintype "passive"))
      (node (ref "R137") (pin "2") (pinfunction "2_2") (pintype "passive"))
    )
    (net (code "185") (name "RDC_RD_P") (class "Default")
      (node (ref "C82") (pin "1") (pinfunction "1_1") (pintype "passive"))
      (node (ref "R135") (pin "2") (pinfunction "2_2") (pintype "passive"))
      (node (ref "R138") (pin "2") (pinfunction "2_2") (pintype "passive"))
    )
    (net (code "186") (name "RD_N") (class "Default")
      (node (ref "C81") (pin "2") (pinfunction "2_2") (pintype "passive"))
      (node (ref "ETH1") (pin "6") (pinfunction "RD-_6") (pintype "passive"))
    )
    (net (code "187") (name "RD_P") (class "Default")
      (node (ref "C82") (pin "2") (pinfunction "2_2") (pintype "passive"))
      (node (ref "ETH1") (pin "4") (pinfunction "RD+_4") (pintype "passive"))
    )
    (net (code "188") (name "RELAY_1") (class "Default")
      (node (ref "D1") (pin "A") (pinfunction "A_A") (pintype "passive"))
      (node (ref "K1") (pin "1") (pinfunction "1_1") (pintype "passive"))
      (node (ref "R24") (pin "2") (pinfunction "2_2") (pintype "passive"))
    )
    (net (code "189") (name "RELAY_2") (class "Default")
      (node (ref "D2") (pin "A") (pinfunction "A_A") (pintype "passive"))
      (node (ref "K2") (pin "1") (pinfunction "1_1") (pintype "passive"))
      (node (ref "R23") (pin "2") (pinfunction "2_2") (pintype "passive"))
    )
    (net (code "190") (name "RELAY_3") (class "Default")
      (node (ref "D3") (pin "A") (pinfunction "A_A") (pintype "passive"))
      (node (ref "K3") (pin "1") (pinfunction "1_1") (pintype "passive"))
      (node (ref "R22") (pin "2") (pinfunction "2_2") (pintype "passive"))
    )
    (net (code "191") (name "RELAY_4") (class "Default")
      (node (ref "D4") (pin "A") (pinfunction "A_A") (pintype "passive"))
      (node (ref "K4") (pin "1") (pinfunction "1_1") (pintype "passive"))
      (node (ref "R21") (pin "2") (pinfunction "2_2") (pintype "passive"))
    )
    (net (code "192") (name "RELAY_5") (class "Default")
      (node (ref "D5") (pin "A") (pinfunction "A_A") (pintype "passive"))
      (node (ref "K5") (pin "1") (pinfunction "1_1") (pintype "passive"))
      (node (ref "R20") (pin "2") (pinfunction "2_2") (pintype "passive"))
    )
    (net (code "193") (name "RELAY_6") (class "Default")
      (node (ref "D6") (pin "A") (pinfunction "A_A") (pintype "passive"))
      (node (ref "K6") (pin "1") (pinfunction "1_1") (pintype "passive"))
      (node (ref "R19") (pin "2") (pinfunction "2_2") (pintype "passive"))
    )
    (net (code "194") (name "RELAY_7") (class "Default")
      (node (ref "D7") (pin "A") (pinfunction "A_A") (pintype "passive"))
      (node (ref "K7") (pin "1") (pinfunction "1_1") (pintype "passive"))
      (node (ref "R18") (pin "2") (pinfunction "2_2") (pintype "passive"))
    )
    (net (code "195") (name "RELAY_8") (class "Default")
      (node (ref "D8") (pin "A") (pinfunction "A_A") (pintype "passive"))
      (node (ref "K8") (pin "1") (pinfunction "1_1") (pintype "passive"))
      (node (ref "R17") (pin "2") (pinfunction "2_2") (pintype "passive"))
    )
    (net (code "196") (name "REL_0") (class "Default")
      (node (ref "IC3") (pin "8") (pinfunction "8B_8") (pintype "bidirectional"))
      (node (ref "IC4") (pin "17") (pinfunction "IO1.0_17") (pintype "bidirectional"))
      (node (ref "REL0") (pin "TP") (pinfunction "P$1_TP") (pintype "bidirectional"))
      (node (ref "RN1") (pin "A2") (pinfunction "2_A2") (pintype "passive"))
    )
    (net (code "197") (name "REL_1") (class "Default")
      (node (ref "IC3") (pin "7") (pinfunction "7B_7") (pintype "bidirectional"))
      (node (ref "IC4") (pin "18") (pinfunction "IO1.1_18") (pintype "bidirectional"))
      (node (ref "REL1") (pin "TP") (pinfunction "P$1_TP") (pintype "bidirectional"))
      (node (ref "RN1") (pin "B2") (pinfunction "2_B2") (pintype "passive"))
    )
    (net (code "198") (name "REL_2") (class "Default")
      (node (ref "IC3") (pin "6") (pinfunction "6B_6") (pintype "bidirectional"))
      (node (ref "IC4") (pin "19") (pinfunction "IO1.2_19") (pintype "bidirectional"))
      (node (ref "REL2") (pin "TP") (pinfunction "P$1_TP") (pintype "bidirectional"))
      (node (ref "RN1") (pin "C2") (pinfunction "2_C2") (pintype "passive"))
    )
    (net (code "199") (name "REL_3") (class "Default")
      (node (ref "IC3") (pin "5") (pinfunction "5B_5") (pintype "bidirectional"))
      (node (ref "IC4") (pin "20") (pinfunction "IO1.3_20") (pintype "bidirectional"))
      (node (ref "REL3") (pin "TP") (pinfunction "P$1_TP") (pintype "bidirectional"))
      (node (ref "RN1") (pin "D2") (pinfunction "2_D2") (pintype "passive"))
    )
    (net (code "200") (name "REL_4") (class "Default")
      (node (ref "IC3") (pin "4") (pinfunction "4B_4") (pintype "bidirectional"))
      (node (ref "IC4") (pin "21") (pinfunction "IO1.4_21") (pintype "bidirectional"))
      (node (ref "REL4") (pin "TP") (pinfunction "P$1_TP") (pintype "bidirectional"))
      (node (ref "RN2") (pin "A2") (pinfunction "2_A2") (pintype "passive"))
    )
    (net (code "201") (name "REL_5") (class "Default")
      (node (ref "IC3") (pin "3") (pinfunction "3B_3") (pintype "bidirectional"))
      (node (ref "IC4") (pin "22") (pinfunction "IO1.5_22") (pintype "bidirectional"))
      (node (ref "REL5") (pin "TP") (pinfunction "P$1_TP") (pintype "bidirectional"))
      (node (ref "RN2") (pin "B2") (pinfunction "2_B2") (pintype "passive"))
    )
    (net (code "202") (name "REL_6") (class "Default")
      (node (ref "IC3") (pin "2") (pinfunction "2B_2") (pintype "bidirectional"))
      (node (ref "IC4") (pin "23") (pinfunction "IO1.6_23") (pintype "bidirectional"))
      (node (ref "REL6") (pin "TP") (pinfunction "P$1_TP") (pintype "bidirectional"))
      (node (ref "RN2") (pin "C2") (pinfunction "2_C2") (pintype "passive"))
    )
    (net (code "203") (name "REL_7") (class "Default")
      (node (ref "IC3") (pin "1") (pinfunction "1B_1") (pintype "bidirectional"))
      (node (ref "IC4") (pin "24") (pinfunction "IO1.7_24") (pintype "bidirectional"))
      (node (ref "REL7") (pin "TP") (pinfunction "P$1_TP") (pintype "bidirectional"))
      (node (ref "RN2") (pin "D2") (pinfunction "2_D2") (pintype "passive"))
    )
    (net (code "204") (name "RP_XI") (class "Default")
      (node (ref "C58") (pin "1") (pinfunction "1_1") (pintype "passive"))
      (node (ref "IC15") (pin "20") (pinfunction "XIN_20") (pintype "bidirectional"))
      (node (ref "X1") (pin "1") (pinfunction "1_1") (pintype "passive"))
    )
    (net (code "205") (name "RP_XO") (class "Default")
      (node (ref "IC15") (pin "21") (pinfunction "XOUT_21") (pintype "bidirectional"))
      (node (ref "R16") (pin "2") (pinfunction "2_2") (pintype "passive"))
    )
    (net (code "206") (name "RUN") (class "Default")
      (node (ref "GDRC") (pin "2") (pinfunction "P$2_2") (pintype "bidirectional"))
      (node (ref "IC15") (pin "26") (pinfunction "RUN_26") (pintype "bidirectional"))
      (node (ref "R132") (pin "2") (pinfunction "2_2") (pintype "passive"))
      (node (ref "RES") (pin "2") (pinfunction "P$2_2") (pintype "bidirectional"))
      (node (ref "RST") (pin "TP") (pinfunction "P$1_TP") (pintype "bidirectional"))
    )
    (net (code "207") (name "RX_RD_N") (class "Default")
      (node (ref "IC20") (pin "5") (pinfunction "RXN_5") (pintype "input"))
      (node (ref "R136") (pin "1") (pinfunction "1_1") (pintype "passive"))
    )
    (net (code "208") (name "RX_RD_P") (class "Default")
      (node (ref "IC20") (pin "6") (pinfunction "RXP_6") (pintype "input"))
      (node (ref "R135") (pin "1") (pinfunction "1_1") (pintype "passive"))
    )
    (net (code "209") (name "SH") (class "Default")
      (node (ref "C78") (pin "1") (pinfunction "1_1") (pintype "passive"))
      (node (ref "C83") (pin "2") (pinfunction "2_2") (pintype "passive"))
      (node (ref "ETH1") (pin "13") (pinfunction "SHIELD_13") (pintype "passive"))
      (node (ref "ETH1") (pin "14") (pinfunction "SHIELD_14") (pintype "passive"))
      (node (ref "R110") (pin "2") (pinfunction "2_2") (pintype "passive"))
      (node (ref "R131") (pin "1") (pinfunction "1_1") (pintype "passive"))
      (node (ref "USB1") (pin "SHLD1") (pinfunction "SHILED_SHLD1") (pintype "power_in"))
      (node (ref "USB1") (pin "SHLD2") (pinfunction "SHILED_SHLD2") (pintype "power_in"))
      (node (ref "USB1") (pin "SHLD3") (pinfunction "SHILED_SHLD3") (pintype "power_in"))
      (node (ref "USB1") (pin "SHLD4") (pinfunction "SHILED_SHLD4") (pintype "power_in"))
    )
    (net (code "210") (name "SRC1") (class "Default")
      (node (ref "C21") (pin "1") (pinfunction "1_1") (pintype "passive"))
      (node (ref "C22") (pin "1") (pinfunction "1_1") (pintype "passive"))
      (node (ref "C5") (pin "1") (pinfunction "1_1") (pintype "passive"))
      (node (ref "D11") (pin "C") (pinfunction "C_C") (pintype "passive"))
      (node (ref "IC13") (pin "3") (pinfunction "SRC2_3") (pintype "output"))
      (node (ref "IC13") (pin "4") (pinfunction "SRC_4") (pintype "output"))
      (node (ref "L3") (pin "1") (pinfunction "1_1") (pintype "passive"))
      (node (ref "R60") (pin "2") (pinfunction "2_2") (pintype "passive"))
    )
    (net (code "211") (name "SRC2") (class "Default")
      (node (ref "C46") (pin "1") (pinfunction "1_1") (pintype "passive"))
      (node (ref "C51") (pin "1") (pinfunction "1_1") (pintype "passive"))
      (node (ref "C52") (pin "1") (pinfunction "1_1") (pintype "passive"))
      (node (ref "D14") (pin "C") (pinfunction "C_C") (pintype "passive"))
      (node (ref "IC5") (pin "3") (pinfunction "SRC2_3") (pintype "output"))
      (node (ref "IC5") (pin "4") (pinfunction "SRC_4") (pintype "output"))
      (node (ref "L5") (pin "1") (pinfunction "1_1") (pintype "passive"))
      (node (ref "R107") (pin "2") (pinfunction "2_2") (pintype "passive"))
    )
    (net (code "212") (name "SWCLK") (class "Default")
      (node (ref "GDRC") (pin "1") (pinfunction "P$1_1") (pintype "bidirectional"))
      (node (ref "IC15") (pin "24") (pinfunction "SWCLK_24") (pintype "bidirectional"))
    )
    (net (code "213") (name "SWDIO") (class "Default")
      (node (ref "GDRC") (pin "3") (pinfunction "P$3_3") (pintype "bidirectional"))
      (node (ref "IC15") (pin "25") (pinfunction "SWDIO_25") (pintype "bidirectional"))
    )
    (net (code "214") (name "TCT") (class "Default")
      (node (ref "C80") (pin "1") (pinfunction "1_1") (pintype "passive"))
      (node (ref "ETH1") (pin "2") (pinfunction "P4/TCT_2") (pintype "passive"))
      (node (ref "R146") (pin "1") (pinfunction "1_1") (pintype "passive"))
    )
    (net (code "215") (name "TD_N") (class "Default")
      (node (ref "ETH1") (pin "3") (pinfunction "TD-_3") (pintype "passive"))
      (node (ref "R134") (pin "2") (pinfunction "2_2") (pintype "passive"))
      (node (ref "R140") (pin "1") (pinfunction "1_1") (pintype "passive"))
    )
    (net (code "216") (name "TD_P") (class "Default")
      (node (ref "ETH1") (pin "1") (pinfunction "TD+_1") (pintype "passive"))
      (node (ref "R133") (pin "2") (pinfunction "2_2") (pintype "passive"))
      (node (ref "R139") (pin "1") (pinfunction "1_1") (pintype "passive"))
    )
    (net (code "217") (name "TX_CH1") (class "Default")
      (node (ref "IC6") (pin "6") (pinfunction "TX_6") (pintype "bidirectional"))
      (node (ref "R155") (pin "1") (pinfunction "1_1") (pintype "passive"))
    )
    (net (code "218") (name "TX_CH2") (class "Default")
      (node (ref "IC8") (pin "6") (pinfunction "TX_6") (pintype "bidirectional"))
      (node (ref "R154") (pin "1") (pinfunction "1_1") (pintype "passive"))
    )
    (net (code "219") (name "TX_CH3") (class "Default")
      (node (ref "IC10") (pin "6") (pinfunction "TX_6") (pintype "bidirectional"))
      (node (ref "R153") (pin "1") (pinfunction "1_1") (pintype "passive"))
    )
    (net (code "220") (name "TX_CH4") (class "Default")
      (node (ref "IC12") (pin "6") (pinfunction "TX_6") (pintype "bidirectional"))
      (node (ref "R59") (pin "1") (pinfunction "1_1") (pintype "passive"))
    )
    (net (code "221") (name "TX_CH5") (class "Default")
      (node (ref "IC7") (pin "6") (pinfunction "TX_6") (pintype "bidirectional"))
      (node (ref "R159") (pin "1") (pinfunction "1_1") (pintype "passive"))
    )
    (net (code "222") (name "TX_CH6") (class "Default")
      (node (ref "IC11") (pin "6") (pinfunction "TX_6") (pintype "bidirectional"))
      (node (ref "R158") (pin "1") (pinfunction "1_1") (pintype "passive"))
    )
    (net (code "223") (name "TX_CH7") (class "Default")
      (node (ref "IC14") (pin "6") (pinfunction "TX_6") (pintype "bidirectional"))
      (node (ref "R157") (pin "1") (pinfunction "1_1") (pintype "passive"))
    )
    (net (code "224") (name "TX_CH8") (class "Default")
      (node (ref "IC16") (pin "6") (pinfunction "TX_6") (pintype "bidirectional"))
      (node (ref "R156") (pin "1") (pinfunction "1_1") (pintype "passive"))
    )
    (net (code "225") (name "TX_MUX1") (class "Default")
      (node (ref "IC9") (pin "4") (pinfunction "D0_4") (pintype "bidirectional"))
      (node (ref "OPT1") (pin "10") (pinfunction "10_10") (pintype "passive"))
      (node (ref "R89") (pin "D1") (pinfunction "4_D1") (pintype "passive"))
    )
    (net (code "226") (name "TX_MUX2") (class "Default")
      (node (ref "IC9") (pin "3") (pinfunction "D1_3") (pintype "bidirectional"))
      (node (ref "OPT1") (pin "12") (pinfunction "12_12") (pintype "passive"))
      (node (ref "R89") (pin "C1") (pinfunction "3_C1") (pintype "passive"))
    )
    (net (code "227") (name "TX_MUX3") (class "Default")
      (node (ref "IC9") (pin "2") (pinfunction "D2_2") (pintype "bidirectional"))
      (node (ref "OPT1") (pin "14") (pinfunction "14_14") (pintype "passive"))
      (node (ref "R89") (pin "B1") (pinfunction "2_B1") (pintype "passive"))
    )
    (net (code "228") (name "TX_MUX4") (class "Default")
      (node (ref "IC9") (pin "1") (pinfunction "D3_1") (pintype "bidirectional"))
      (node (ref "OPT1") (pin "16") (pinfunction "16_16") (pintype "passive"))
      (node (ref "R89") (pin "A1") (pinfunction "1_A1") (pintype "passive"))
    )
    (net (code "229") (name "TX_MUX5") (class "Default")
      (node (ref "IC9") (pin "15") (pinfunction "D4_15") (pintype "bidirectional"))
      (node (ref "OPT2") (pin "10") (pinfunction "10_10") (pintype "passive"))
      (node (ref "R90") (pin "A1") (pinfunction "1_A1") (pintype "passive"))
    )
    (net (code "230") (name "TX_MUX6") (class "Default")
      (node (ref "IC9") (pin "14") (pinfunction "D5_14") (pintype "bidirectional"))
      (node (ref "OPT2") (pin "12") (pinfunction "12_12") (pintype "passive"))
      (node (ref "R90") (pin "B1") (pinfunction "2_B1") (pintype "passive"))
    )
    (net (code "231") (name "TX_MUX7") (class "Default")
      (node (ref "IC9") (pin "13") (pinfunction "D6_13") (pintype "bidirectional"))
      (node (ref "OPT2") (pin "14") (pinfunction "14_14") (pintype "passive"))
      (node (ref "R90") (pin "C1") (pinfunction "3_C1") (pintype "passive"))
    )
    (net (code "232") (name "TX_MUX8") (class "Default")
      (node (ref "IC9") (pin "12") (pinfunction "D7_12") (pintype "bidirectional"))
      (node (ref "OPT2") (pin "16") (pinfunction "16_16") (pintype "passive"))
      (node (ref "R90") (pin "D1") (pinfunction "4_D1") (pintype "passive"))
    )
    (net (code "233") (name "TX_OUT") (class "Default")
      (node (ref "IC9") (pin "5") (pinfunction "Y_5") (pintype "bidirectional"))
      (node (ref "R91") (pin "1") (pinfunction "1_1") (pintype "passive"))
    )
    (net (code "234") (name "TX_TD_N") (class "Default")
      (node (ref "IC20") (pin "1") (pinfunction "TXN_1") (pintype "output"))
      (node (ref "R134") (pin "1") (pinfunction "1_1") (pintype "passive"))
    )
    (net (code "235") (name "TX_TD_P") (class "Default")
      (node (ref "IC20") (pin "2") (pinfunction "TXP_2") (pintype "output"))
      (node (ref "R133") (pin "1") (pinfunction "1_1") (pintype "passive"))
    )
    (net (code "236") (name "UART0_RX") (class "Default")
      (node (ref "IC15") (pin "2") (pinfunction "GPIO0_2") (pintype "bidirectional"))
      (node (ref "R58") (pin "2") (pinfunction "2_2") (pintype "passive"))
      (node (ref "RGTG") (pin "1") (pinfunction "P$1_1") (pintype "bidirectional"))
      (node (ref "RX0") (pin "TP") (pinfunction "P$1_TP") (pintype "bidirectional"))
    )
    (net (code "237") (name "UART0_TX") (class "Default")
      (node (ref "IC15") (pin "3") (pinfunction "GPIO1_3") (pintype "bidirectional"))
      (node (ref "R57") (pin "2") (pinfunction "2_2") (pintype "passive"))
      (node (ref "RGTG") (pin "3") (pinfunction "P$3_3") (pintype "bidirectional"))
      (node (ref "TX0") (pin "TP") (pinfunction "P$1_TP") (pintype "bidirectional"))
    )
    (net (code "238") (name "USB2_DP_N") (class "Default")
      (node (ref "ESD1") (pin "3") (pinfunction "C2_3") (pintype "bidirectional"))
      (node (ref "R15") (pin "1") (pinfunction "1_1") (pintype "passive"))
      (node (ref "USB1") (pin "A7") (pinfunction "D-_A7") (pintype "bidirectional"))
      (node (ref "USB1") (pin "B7") (pinfunction "D-_B7") (pintype "bidirectional"))
    )
    (net (code "239") (name "USB2_DP_P") (class "Default")
      (node (ref "ESD1") (pin "2") (pinfunction "C1_2") (pintype "bidirectional"))
      (node (ref "R160") (pin "1") (pinfunction "1_1") (pintype "passive"))
      (node (ref "USB1") (pin "A6") (pinfunction "D+_A6") (pintype "bidirectional"))
      (node (ref "USB1") (pin "B6") (pinfunction "D+_B6") (pintype "bidirectional"))
    )
    (net (code "240") (name "USB_BOOT") (class "Default")
      (node (ref "BOOT") (pin "TP") (pinfunction "P$1_TP") (pintype "bidirectional"))
      (node (ref "BT") (pin "1") (pinfunction "P$1_1") (pintype "bidirectional"))
      (node (ref "R112") (pin "1") (pinfunction "1_1") (pintype "passive"))
    )
    (net (code "241") (name "USB_VBUS") (class "Default")
      (node (ref "R121") (pin "1") (pinfunction "1_1") (pintype "passive"))
      (node (ref "R126") (pin "1") (pinfunction "1_1") (pintype "passive"))
      (node (ref "R170") (pin "1") (pinfunction "1_1") (pintype "passive"))
      (node (ref "USB1") (pin "VBUS1") (pinfunction "VBUS_VBUS1") (pintype "power_in"))
      (node (ref "USB1") (pin "VBUS2") (pinfunction "VBUS_VBUS2") (pintype "power_in"))
    )
    (net (code "242") (name "VBUS") (class "Default")
      (node (ref "C65") (pin "1") (pinfunction "1_1") (pintype "passive"))
      (node (ref "C66") (pin "1") (pinfunction "1_1") (pintype "passive"))
      (node (ref "C97") (pin "1") (pinfunction "1_1") (pintype "passive"))
      (node (ref "C98") (pin "1") (pinfunction "1_1") (pintype "passive"))
      (node (ref "D15") (pin "C") (pinfunction "C_C") (pintype "passive"))
      (node (ref "ESD1") (pin "4") (pinfunction "C3_4") (pintype "bidirectional"))
      (node (ref "IC21") (pin "1") (pinfunction "VIN_1") (pintype "bidirectional"))
      (node (ref "IC21") (pin "3") (pinfunction "EN_3") (pintype "bidirectional"))
      (node (ref "R170") (pin "2") (pinfunction "2_2") (pintype "passive"))
      (node (ref "VBUS") (pin "TP") (pinfunction "P$1_TP") (pintype "bidirectional"))
    )
    (net (code "243") (name "VNI1") (class "Default")
      (node (ref "C21") (pin "2") (pinfunction "2_2") (pintype "passive"))
      (node (ref "IC13") (pin "1") (pinfunction "VCC_1") (pintype "output"))
      (node (ref "VCC") (pin "TP") (pinfunction "P$1_TP") (pintype "bidirectional"))
    )
    (net (code "244") (name "VNI2") (class "Default")
      (node (ref "C46") (pin "2") (pinfunction "2_2") (pintype "passive"))
      (node (ref "IC5") (pin "1") (pinfunction "VCC_1") (pintype "output"))
      (node (ref "VCC2") (pin "TP") (pinfunction "P$1_TP") (pintype "bidirectional"))
    )
    (net (code "245") (name "W5500_MISO") (class "Default")
      (node (ref "IC15") (pin "27") (pinfunction "GPIO16_27") (pintype "bidirectional"))
      (node (ref "IC20") (pin "34") (pinfunction "MISO_34") (pintype "output"))
      (node (ref "MISO1") (pin "TP") (pinfunction "P$1_TP") (pintype "bidirectional"))
    )
    (net (code "246") (name "W5500_MOSI") (class "Default")
      (node (ref "IC15") (pin "30") (pinfunction "GPIO19_30") (pintype "bidirectional"))
      (node (ref "IC20") (pin "35") (pinfunction "MOSI_35") (pintype "input"))
      (node (ref "MOSI1") (pin "TP") (pinfunction "P$1_TP") (pintype "bidirectional"))
    )
    (net (code "247") (name "W5500_SCK") (class "Default")
      (node (ref "IC15") (pin "29") (pinfunction "GPIO18_29") (pintype "bidirectional"))
      (node (ref "IC20") (pin "33") (pinfunction "SCLK_33") (pintype "input"))
      (node (ref "SCLK1") (pin "TP") (pinfunction "P$1_TP") (pintype "bidirectional"))
    )
    (net (code "248") (name "unconnected-(IC4-INTA-Pad16)") (class "Default")
      (node (ref "IC4") (pin "16") (pinfunction "INTA_16") (pintype "bidirectional"))
    )
    (net (code "249") (name "unconnected-(IC4-INTB-Pad15)") (class "Default")
      (node (ref "IC4") (pin "15") (pinfunction "INTB_15") (pintype "bidirectional"))
    )
    (net (code "250") (name "unconnected-(IC4-IO2.4-Pad1)") (class "Default")
      (node (ref "IC4") (pin "1") (pinfunction "IO2.4_1") (pintype "bidirectional"))
    )
    (net (code "251") (name "unconnected-(IC4-IO2.5-Pad2)") (class "Default")
      (node (ref "IC4") (pin "2") (pinfunction "IO2.5_2") (pintype "bidirectional"))
    )
    (net (code "252") (name "unconnected-(IC4-IO2.6-Pad3)") (class "Default")
      (node (ref "IC4") (pin "3") (pinfunction "IO2.6_3") (pintype "bidirectional"))
    )
    (net (code "253") (name "unconnected-(IC4-IO2.7-Pad4)") (class "Default")
      (node (ref "IC4") (pin "4") (pinfunction "IO2.7_4") (pintype "bidirectional"))
    )
    (net (code "254") (name "unconnected-(IC6-PF-Pad7)") (class "Default")
      (node (ref "IC6") (pin "7") (pinfunction "PF_7") (pintype "bidirectional"))
    )
    (net (code "255") (name "unconnected-(IC6-RX-Pad8)") (class "Default")
      (node (ref "IC6") (pin "8") (pinfunction "RX_8") (pintype "bidirectional"))
    )
    (net (code "256") (name "unconnected-(IC7-PF-Pad7)") (class "Default")
      (node (ref "IC7") (pin "7") (pinfunction "PF_7") (pintype "bidirectional"))
    )
    (net (code "257") (name "unconnected-(IC7-RX-Pad8)") (class "Default")
      (node (ref "IC7") (pin "8") (pinfunction "RX_8") (pintype "bidirectional"))
    )
    (net (code "258") (name "unconnected-(IC8-PF-Pad7)") (class "Default")
      (node (ref "IC8") (pin "7") (pinfunction "PF_7") (pintype "bidirectional"))
    )
    (net (code "259") (name "unconnected-(IC8-RX-Pad8)") (class "Default")
      (node (ref "IC8") (pin "8") (pinfunction "RX_8") (pintype "bidirectional"))
    )
    (net (code "260") (name "unconnected-(IC10-PF-Pad7)") (class "Default")
      (node (ref "IC10") (pin "7") (pinfunction "PF_7") (pintype "bidirectional"))
    )
    (net (code "261") (name "unconnected-(IC10-RX-Pad8)") (class "Default")
      (node (ref "IC10") (pin "8") (pinfunction "RX_8") (pintype "bidirectional"))
    )
    (net (code "262") (name "unconnected-(IC11-PF-Pad7)") (class "Default")
      (node (ref "IC11") (pin "7") (pinfunction "PF_7") (pintype "bidirectional"))
    )
    (net (code "263") (name "unconnected-(IC11-RX-Pad8)") (class "Default")
      (node (ref "IC11") (pin "8") (pinfunction "RX_8") (pintype "bidirectional"))
    )
    (net (code "264") (name "unconnected-(IC12-PF-Pad7)") (class "Default")
      (node (ref "IC12") (pin "7") (pinfunction "PF_7") (pintype "bidirectional"))
    )
    (net (code "265") (name "unconnected-(IC12-RX-Pad8)") (class "Default")
      (node (ref "IC12") (pin "8") (pinfunction "RX_8") (pintype "bidirectional"))
    )
    (net (code "266") (name "unconnected-(IC14-PF-Pad7)") (class "Default")
      (node (ref "IC14") (pin "7") (pinfunction "PF_7") (pintype "bidirectional"))
    )
    (net (code "267") (name "unconnected-(IC14-RX-Pad8)") (class "Default")
      (node (ref "IC14") (pin "8") (pinfunction "RX_8") (pintype "bidirectional"))
    )
    (net (code "268") (name "unconnected-(IC16-PF-Pad7)") (class "Default")
      (node (ref "IC16") (pin "7") (pinfunction "PF_7") (pintype "bidirectional"))
    )
    (net (code "269") (name "unconnected-(IC16-RX-Pad8)") (class "Default")
      (node (ref "IC16") (pin "8") (pinfunction "RX_8") (pintype "bidirectional"))
    )
    (net (code "270") (name "unconnected-(IC20-DNC-Pad7)") (class "Default")
      (node (ref "IC20") (pin "7") (pinfunction "DNC_7") (pintype "bidirectional"))
    )
    (net (code "271") (name "unconnected-(IC20-DUPLED-Pad26)") (class "Default")
      (node (ref "IC20") (pin "26") (pinfunction "DUPLED_26") (pintype "output"))
    )
    (net (code "272") (name "unconnected-(IC20-RSVD1-Pad23)") (class "Default")
      (node (ref "IC20") (pin "23") (pinfunction "RSVD1_23") (pintype "input"))
    )
    (net (code "273") (name "unconnected-(IC20-RSVD2-Pad38)") (class "Default")
      (node (ref "IC20") (pin "38") (pinfunction "RSVD2_38") (pintype "input"))
    )
    (net (code "274") (name "unconnected-(IC20-RSVD3-Pad39)") (class "Default")
      (node (ref "IC20") (pin "39") (pinfunction "RSVD3_39") (pintype "input"))
    )
    (net (code "275") (name "unconnected-(IC20-RSVD4-Pad40)") (class "Default")
      (node (ref "IC20") (pin "40") (pinfunction "RSVD4_40") (pintype "input"))
    )
    (net (code "276") (name "unconnected-(IC20-RSVD5-Pad41)") (class "Default")
      (node (ref "IC20") (pin "41") (pinfunction "RSVD5_41") (pintype "input"))
    )
    (net (code "277") (name "unconnected-(IC20-RSVD6-Pad42)") (class "Default")
      (node (ref "IC20") (pin "42") (pinfunction "RSVD6_42") (pintype "input"))
    )
    (net (code "278") (name "unconnected-(IC20-SPDLED-Pad24)") (class "Default")
      (node (ref "IC20") (pin "24") (pinfunction "SPDLED_24") (pintype "output"))
    )
    (net (code "279") (name "unconnected-(IC20-VBG-Pad18)") (class "Default")
      (node (ref "IC20") (pin "18") (pinfunction "VBG_18") (pintype "output"))
    )
    (net (code "280") (name "unconnected-(IC21-NC-Pad4)") (class "Default")
      (node (ref "IC21") (pin "4") (pinfunction "NC_4") (pintype "bidirectional"))
    )
    (net (code "281") (name "unconnected-(R149-5-PadD2)") (class "Default")
      (node (ref "R149") (pin "D2") (pinfunction "5_D2") (pintype "passive"))
    )
    (net (code "282") (name "unconnected-(USB1-SBU1-PadA8)") (class "Default")
      (node (ref "USB1") (pin "A8") (pinfunction "SBU1_A8") (pintype "bidirectional"))
    )
    (net (code "283") (name "unconnected-(USB1-SBU2-PadB8)") (class "Default")
      (node (ref "USB1") (pin "B8") (pinfunction "SBU2_B8") (pintype "bidirectional"))
    )
    (net (code "284") (name "~{ACT}") (class "Default")
      (node (ref "IC20") (pin "27") (pinfunction "ACTLED_27") (pintype "output"))
      (node (ref "R142") (pin "1") (pinfunction "1_1") (pintype "passive"))
    )
    (net (code "285") (name "~{LINK}") (class "Default")
      (node (ref "IC20") (pin "25") (pinfunction "LINKLED_25") (pintype "output"))
      (node (ref "R141") (pin "1") (pinfunction "1_1") (pintype "passive"))
    )
    (net (code "286") (name "~{QSPI_SS}") (class "Default")
      (node (ref "IC15") (pin "56") (pinfunction "QSPI_SS_N_56") (pintype "bidirectional"))
      (node (ref "IC18") (pin "1") (pinfunction "~{CS}_1") (pintype "bidirectional"))
      (node (ref "R111") (pin "1") (pinfunction "1_1") (pintype "passive"))
      (node (ref "R112") (pin "2") (pinfunction "2_2") (pintype "passive"))
    )
    (net (code "287") (name "~{TX_OUT}") (class "Default")
      (node (ref "IC22") (pin "3") (pinfunction "+IN_3") (pintype "input"))
      (node (ref "IC9") (pin "6") (pinfunction "~{Y}_6") (pintype "bidirectional"))
      (node (ref "R92") (pin "1") (pinfunction "1_1") (pintype "passive"))
    )
    (net (code "288") (name "~{W5500_CS}") (class "Default")
      (node (ref "CS1") (pin "TP") (pinfunction "P$1_TP") (pintype "bidirectional"))
      (node (ref "IC15") (pin "28") (pinfunction "GPIO17_28") (pintype "bidirectional"))
      (node (ref "IC20") (pin "32") (pinfunction "~{SCSN}_32") (pintype "input"))
    )
    (net (code "289") (name "~{W5500_INT}") (class "Default")
      (node (ref "IC15") (pin "32") (pinfunction "GPIO21_32") (pintype "bidirectional"))
      (node (ref "IC20") (pin "36") (pinfunction "~{INTN}_36") (pintype "input"))
    )
    (net (code "290") (name "~{W5500_RST}") (class "Default")
      (node (ref "IC15") (pin "31") (pinfunction "GPIO20_31") (pintype "bidirectional"))
      (node (ref "IC20") (pin "37") (pinfunction "~{RSTN}_37") (pintype "input"))
      (node (ref "R145") (pin "1") (pinfunction "1_1") (pintype "passive"))
    )
  )
)
